# FootPlate_v1.net
KiCad netlist of a schematic drawn in EAGLE
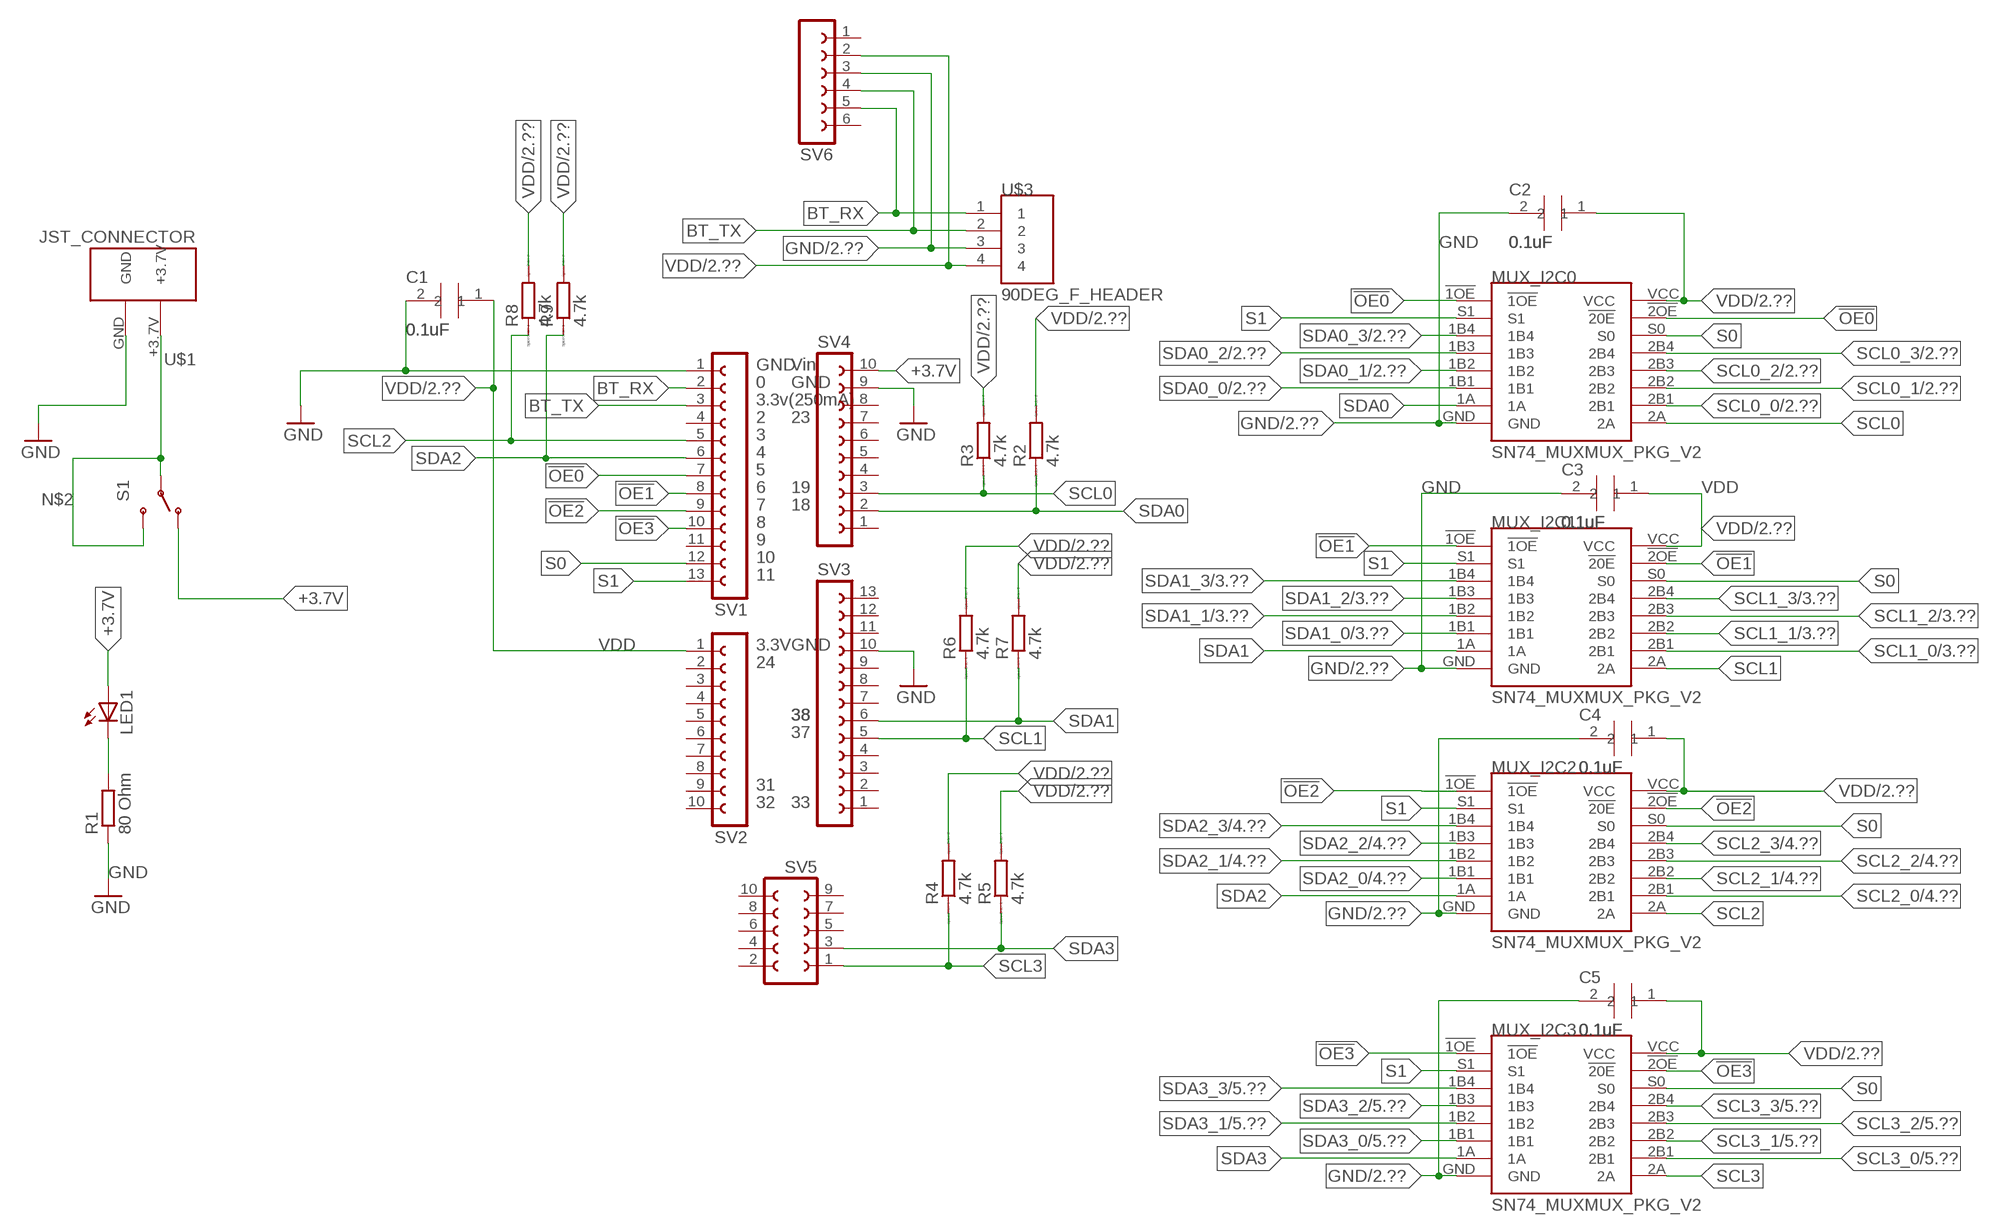
[diagram p0: schematic, sheet 1]
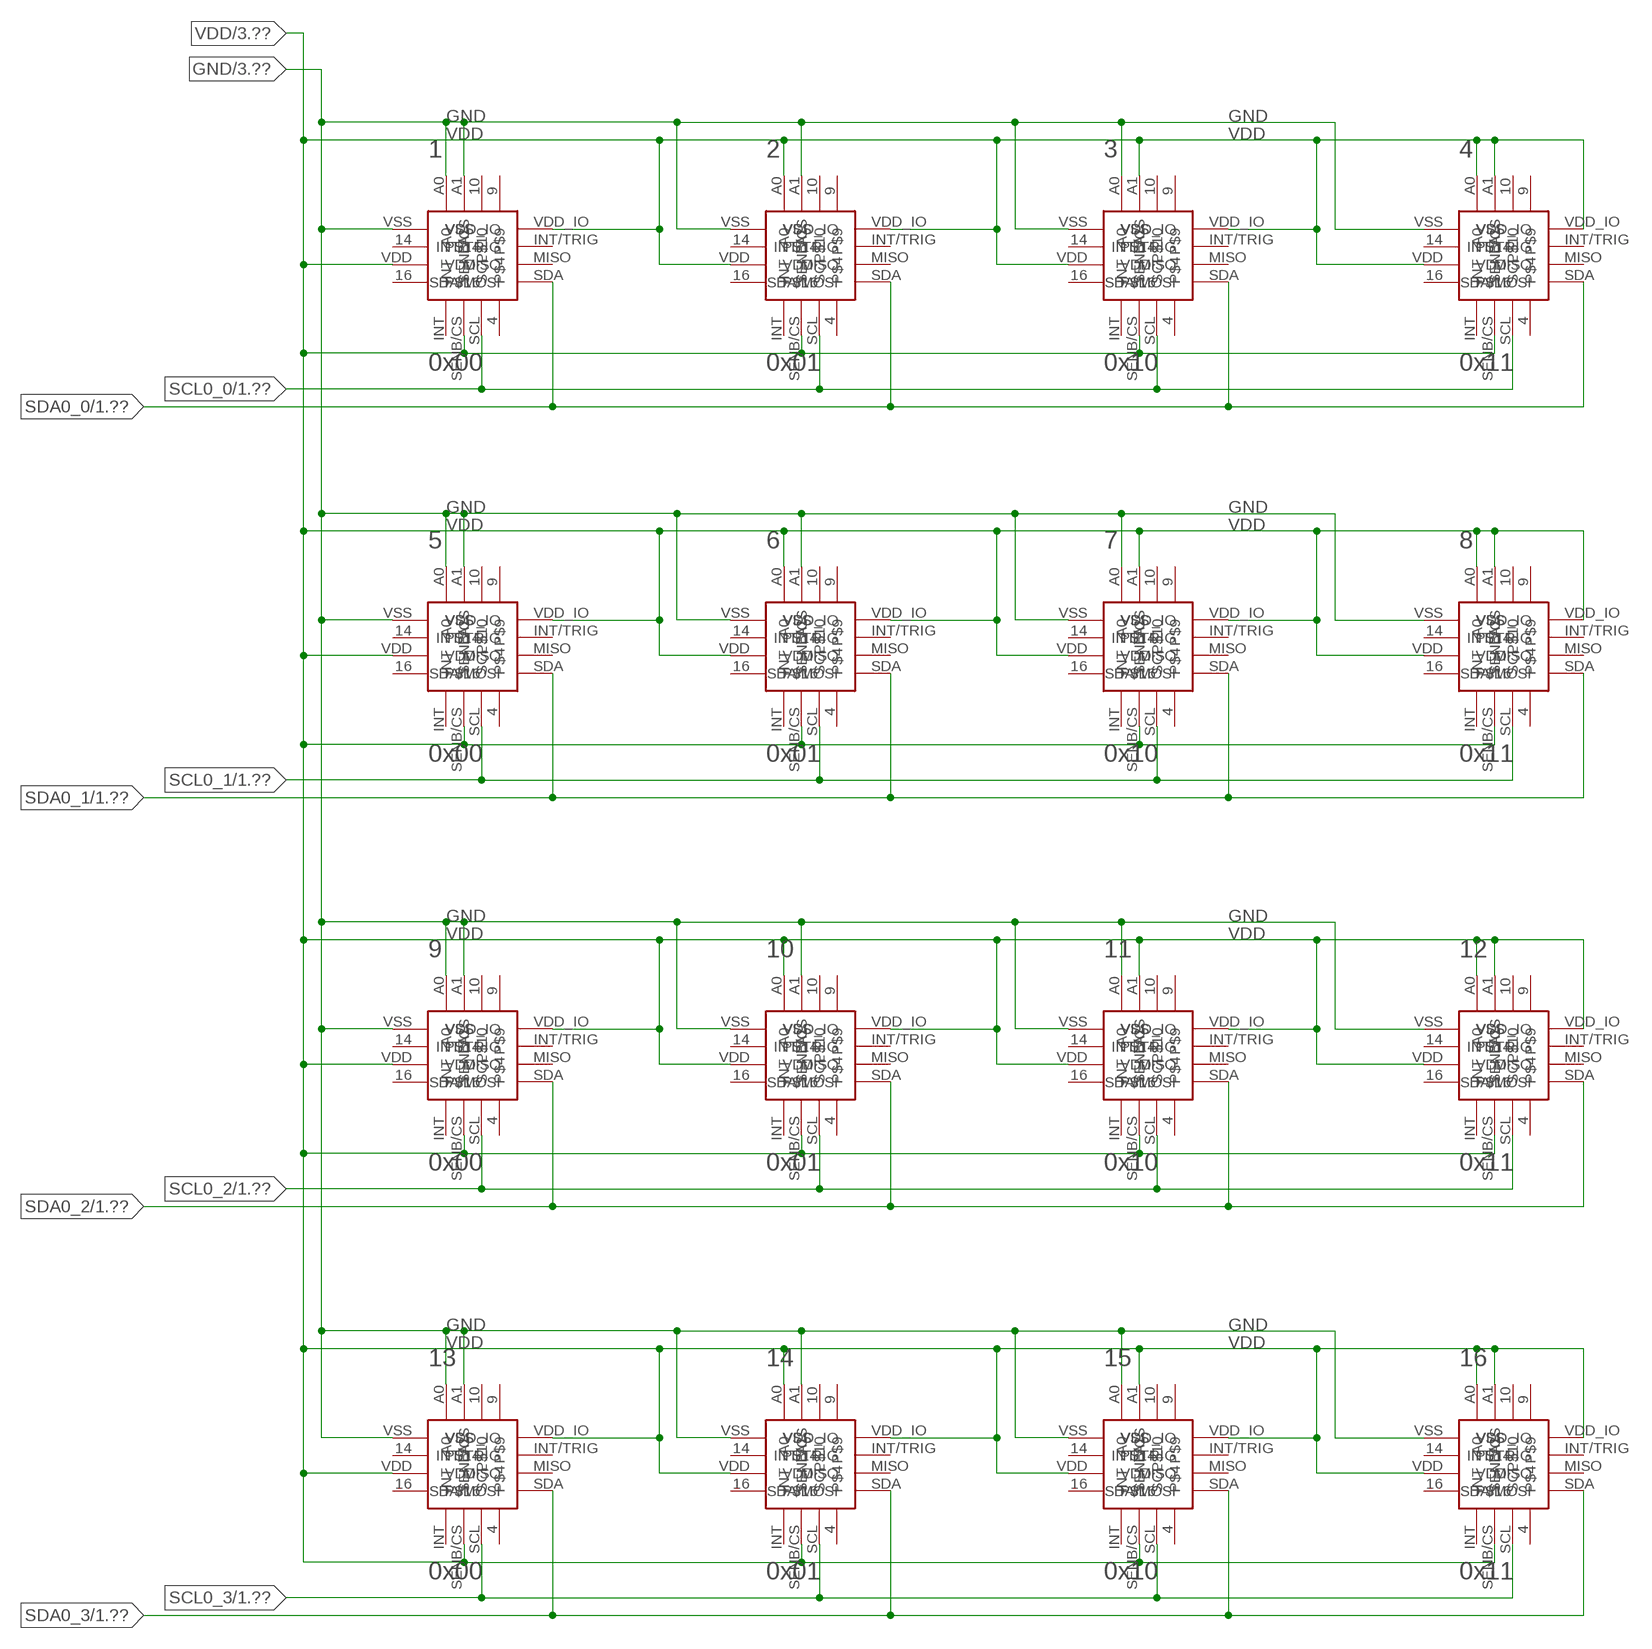
[diagram p1: schematic, sheet 2]
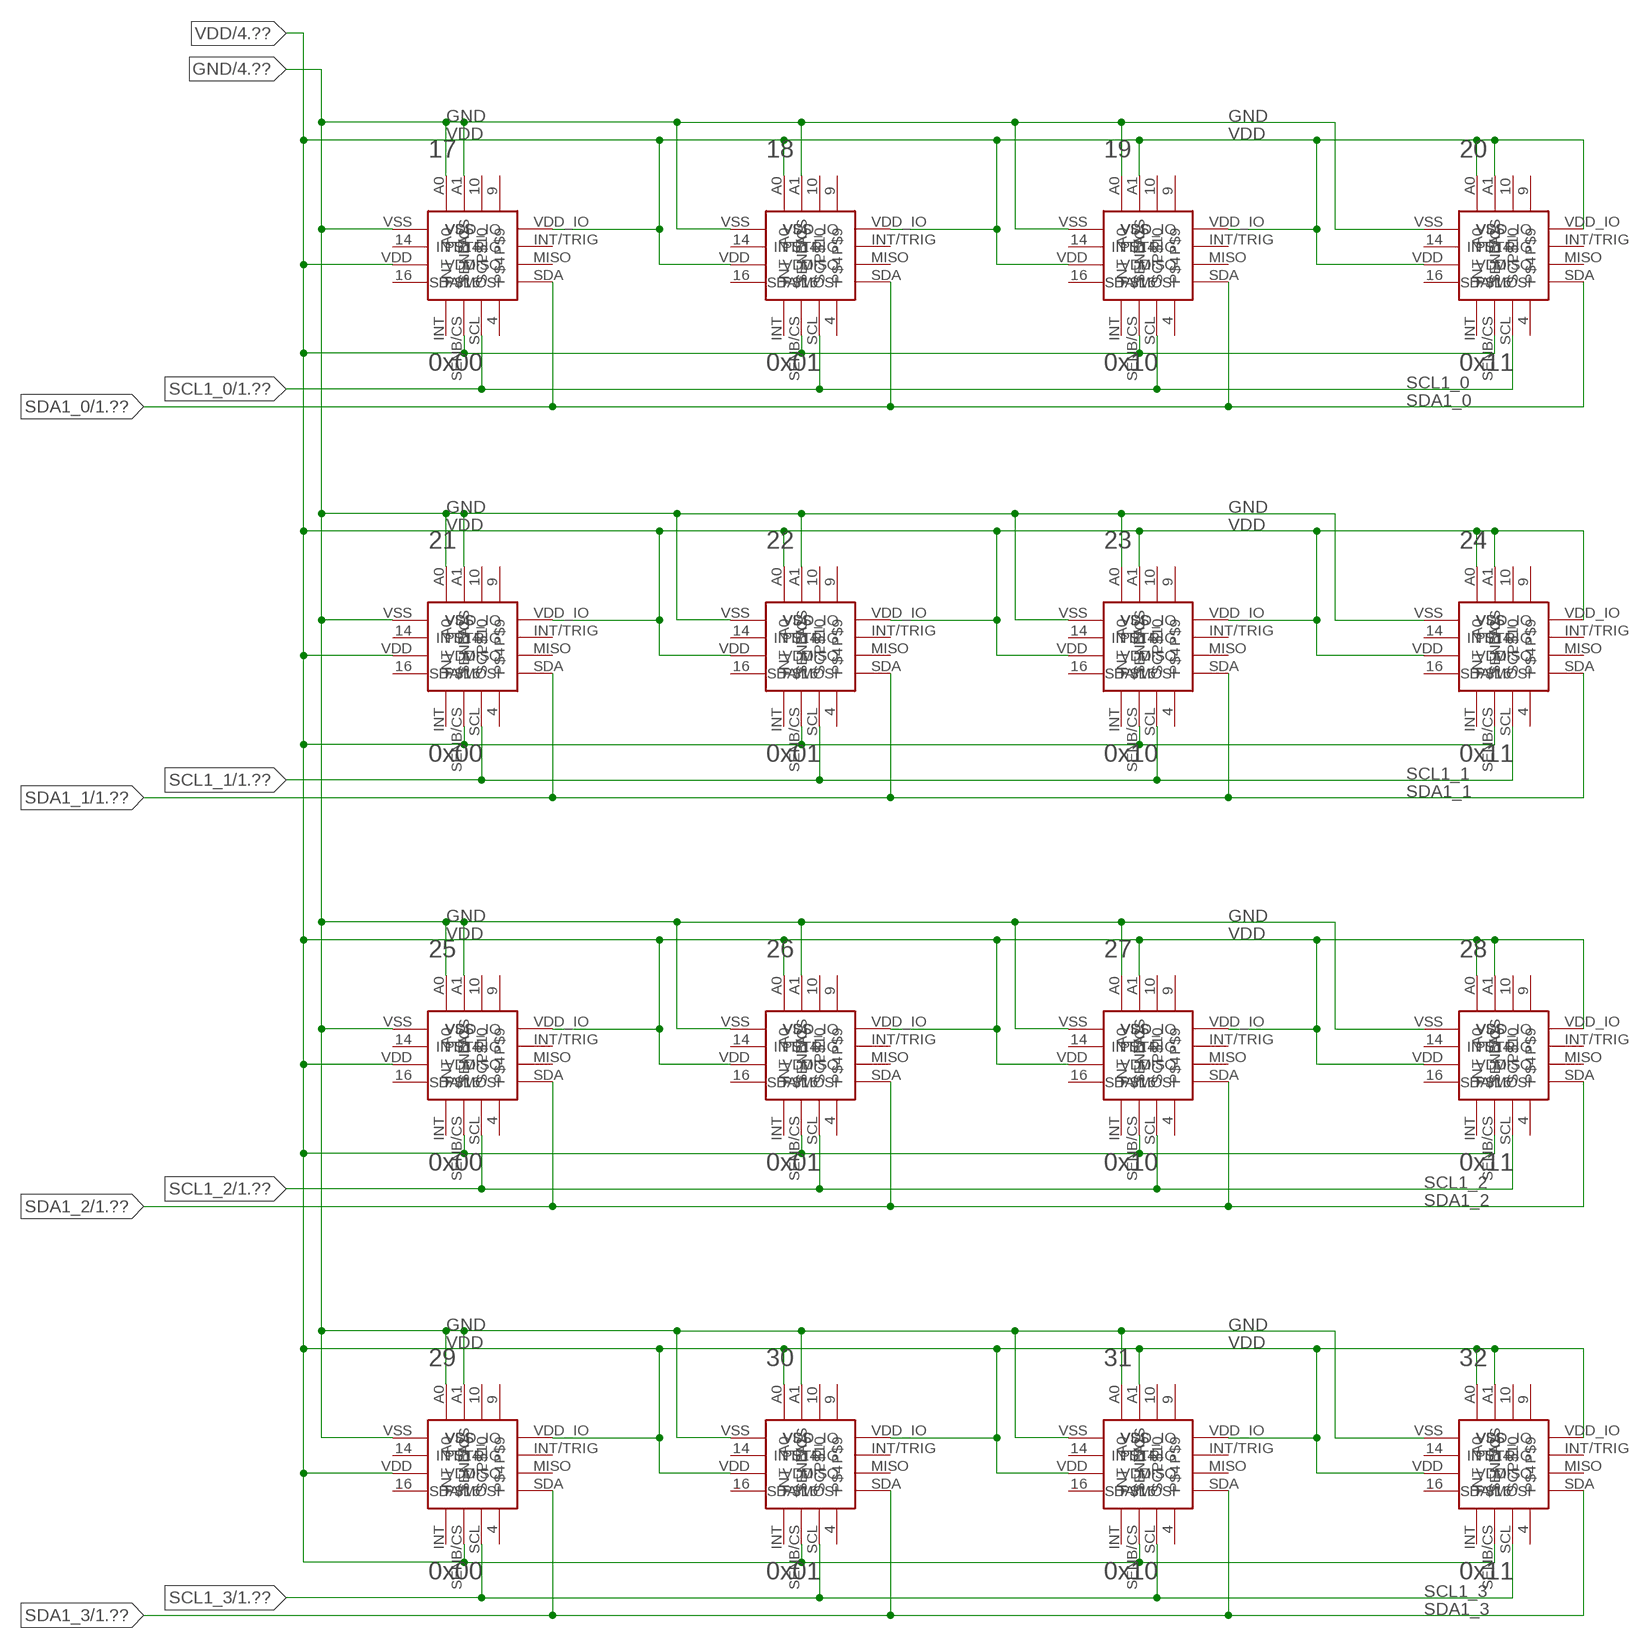
[diagram p2: schematic, sheet 3]
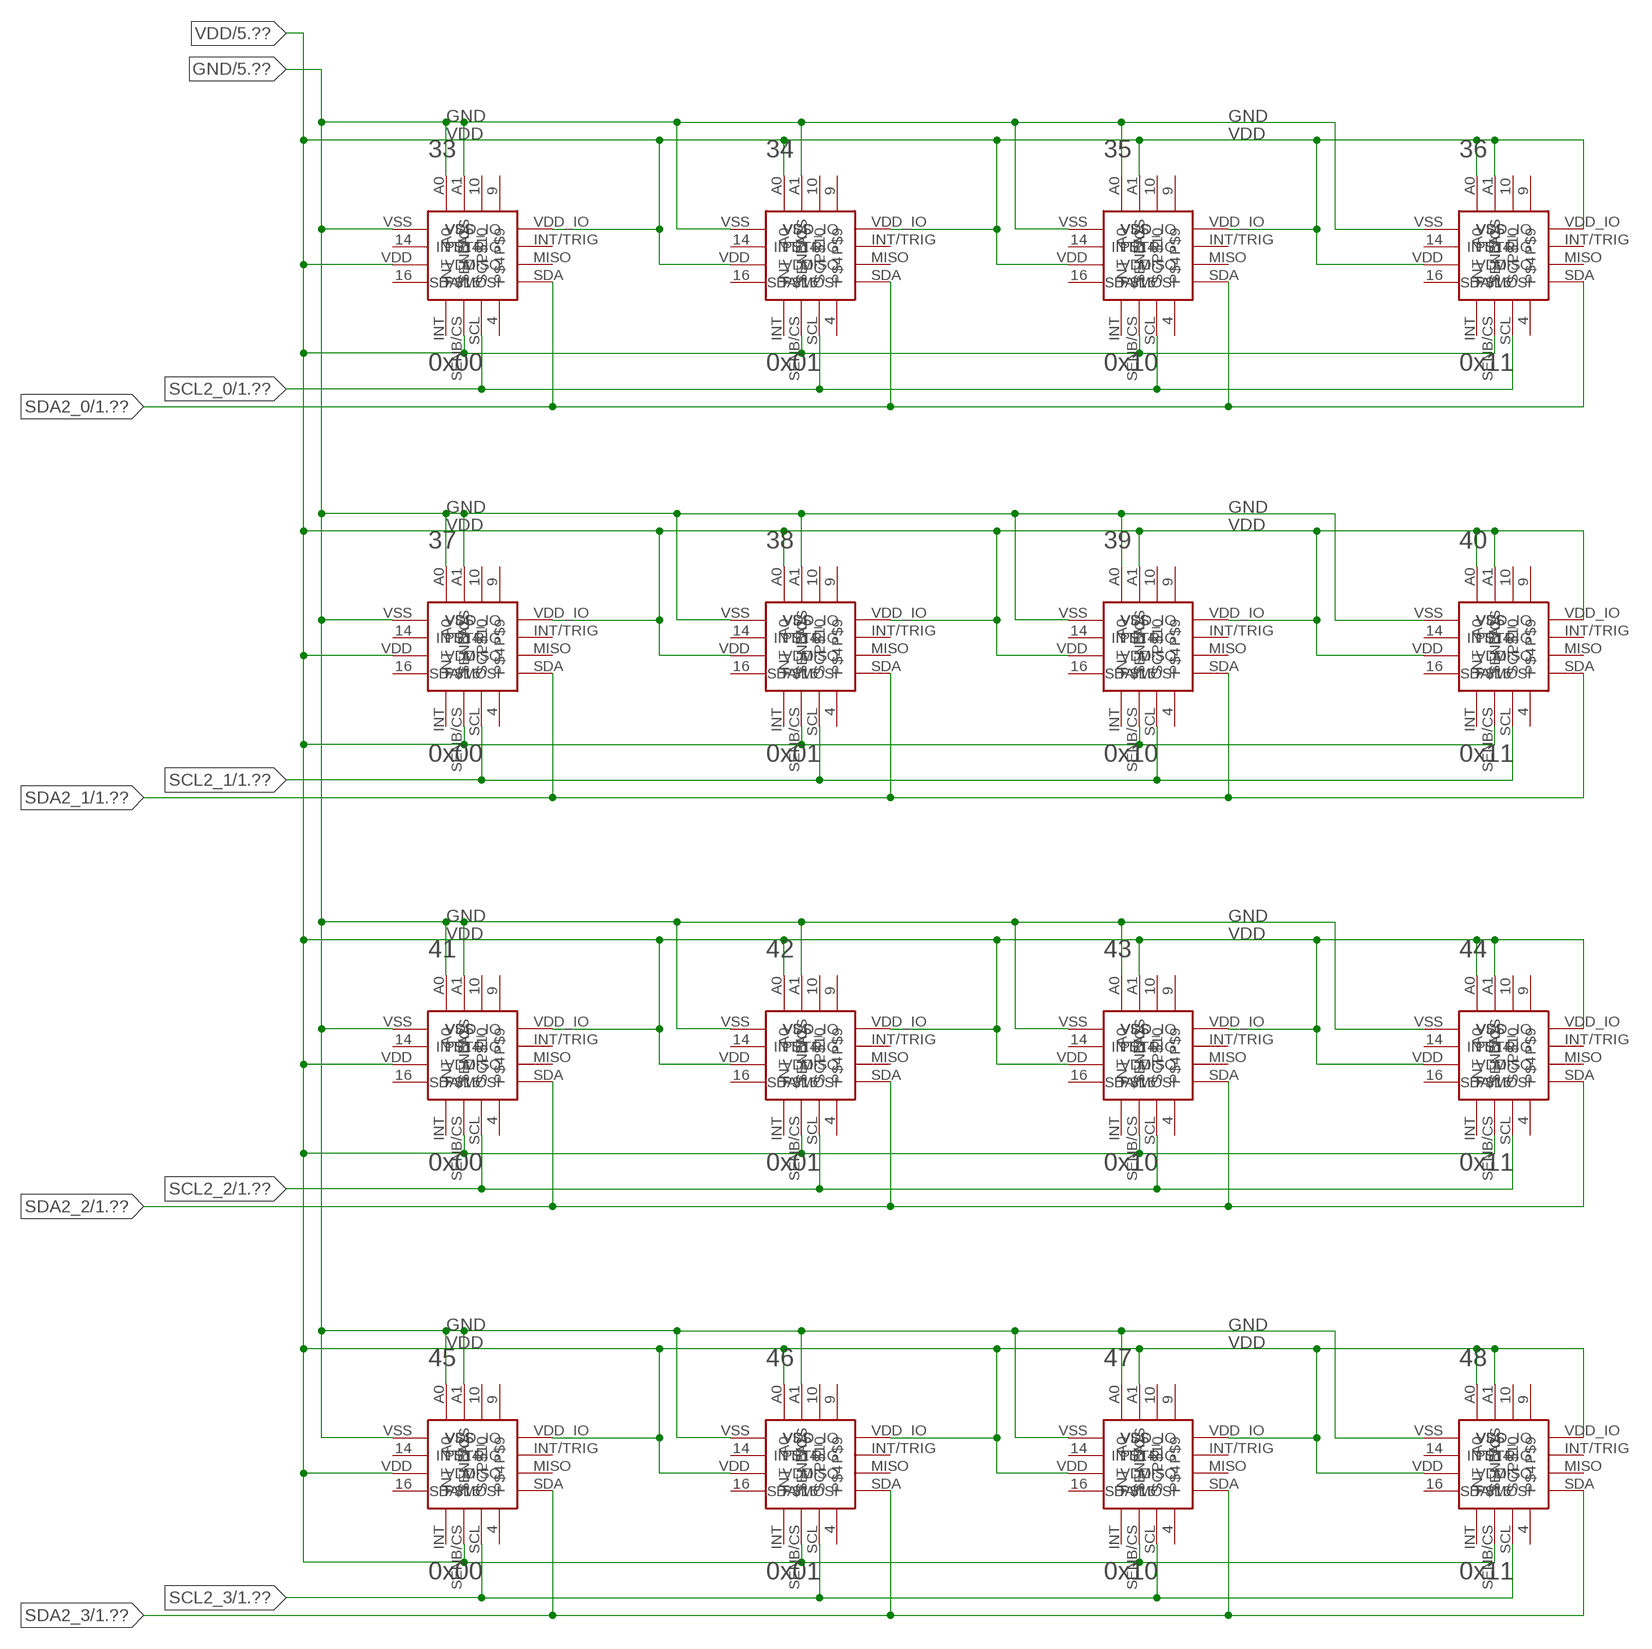
[diagram p3: schematic, sheet 4]
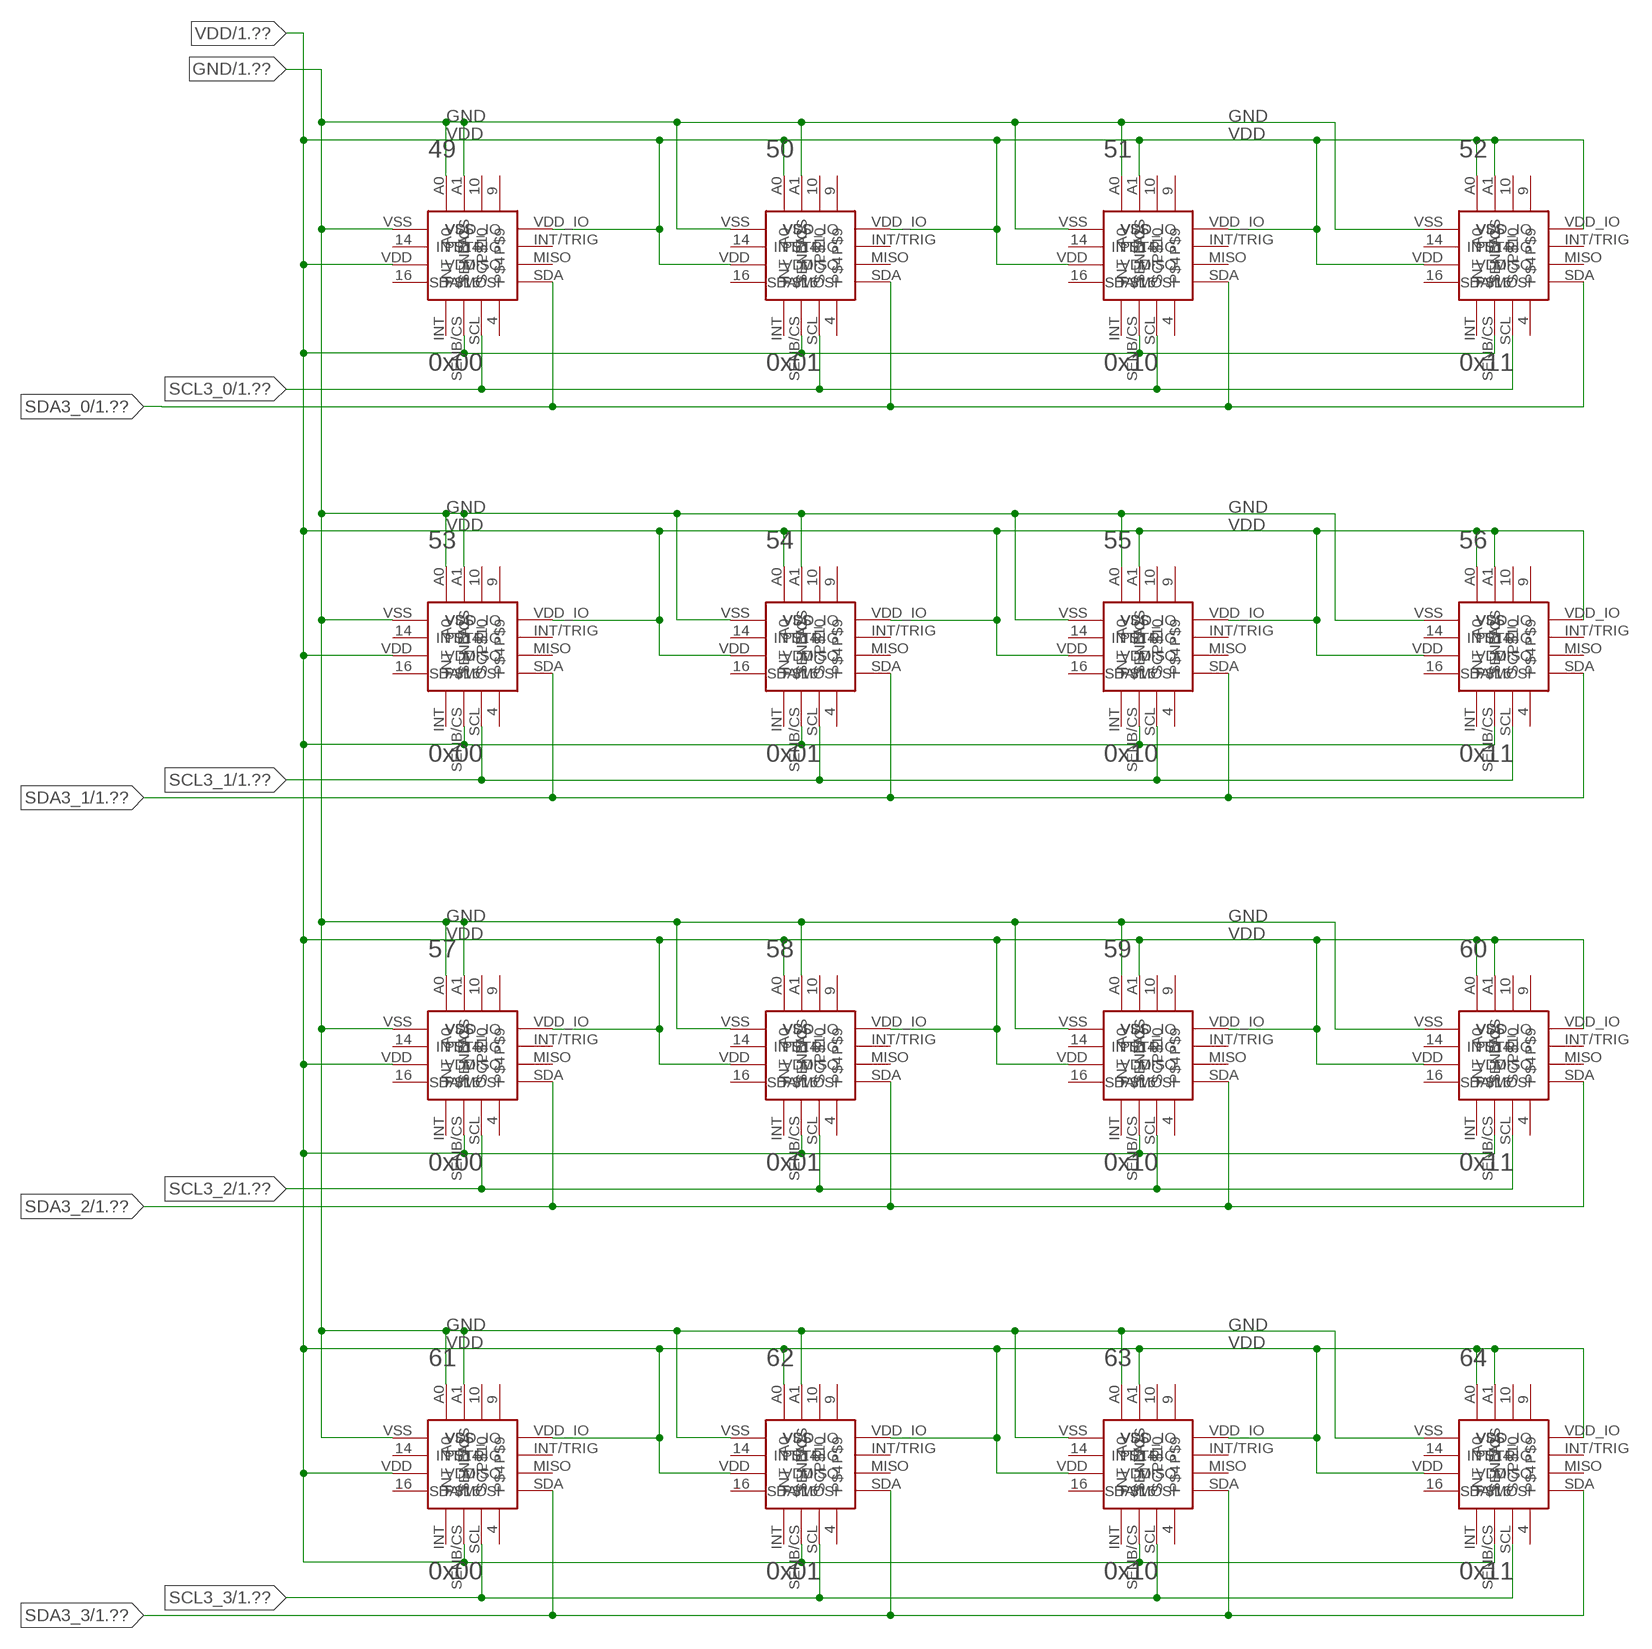
[diagram p4: schematic, sheet 5]

(export (version "E")
  (design (tool "Eeschema 10.0.6"))
  (components
    (comp (ref "C1")
      (value "0.1uF")
      (footprint "eagle-import:CAPC1608X75")
      (libsource (lib "eagle-import") (part "CAP"))
    )
    (comp (ref "C2")
      (value "0.1uF")
      (footprint "eagle-import:CAPC1608X75")
      (libsource (lib "eagle-import") (part "CAP"))
    )
    (comp (ref "C3")
      (value "0.1uF")
      (footprint "eagle-import:CAPC1608X75")
      (libsource (lib "eagle-import") (part "CAP"))
    )
    (comp (ref "C4")
      (value "0.1uF")
      (footprint "eagle-import:CAPC1608X75")
      (libsource (lib "eagle-import") (part "CAP"))
    )
    (comp (ref "C5")
      (value "0.1uF")
      (footprint "eagle-import:CAPC1608X75")
      (libsource (lib "eagle-import") (part "CAP"))
    )
    (comp (ref "LED1")
      (value "LEDSMT1206")
      (footprint "eagle-import:1206")
      (libsource (lib "eagle-import") (part "LEDSMT1206"))
    )
    (comp (ref "MUX_I2C0")
      (value "SN74_MUXMUX_PKG_V2")
      (footprint "eagle-import:SOP65P640X120-16")
      (libsource (lib "eagle-import") (part "SN74_MUXMUX_PKG_V2"))
    )
    (comp (ref "MUX_I2C1")
      (value "SN74_MUXMUX_PKG_V2")
      (footprint "eagle-import:SOP65P640X120-16")
      (libsource (lib "eagle-import") (part "SN74_MUXMUX_PKG_V2"))
    )
    (comp (ref "MUX_I2C2")
      (value "SN74_MUXMUX_PKG_V2")
      (footprint "eagle-import:SOP65P640X120-16")
      (libsource (lib "eagle-import") (part "SN74_MUXMUX_PKG_V2"))
    )
    (comp (ref "MUX_I2C3")
      (value "SN74_MUXMUX_PKG_V2")
      (footprint "eagle-import:SOP65P640X120-16")
      (libsource (lib "eagle-import") (part "SN74_MUXMUX_PKG_V2"))
    )
    (comp (ref "R1")
      (value "80 Ohm")
      (footprint "eagle-import:M1206")
      (libsource (lib "eagle-import") (part "R-EU_M1206"))
    )
    (comp (ref "R2")
      (value "4.7k")
      (footprint "eagle-import:R1206")
      (libsource (lib "eagle-import") (part "RR1206"))
    )
    (comp (ref "R3")
      (value "4.7k")
      (footprint "eagle-import:R1206")
      (libsource (lib "eagle-import") (part "RR1206"))
    )
    (comp (ref "R4")
      (value "4.7k")
      (footprint "eagle-import:R1206")
      (libsource (lib "eagle-import") (part "RR1206"))
    )
    (comp (ref "R5")
      (value "4.7k")
      (footprint "eagle-import:R1206")
      (libsource (lib "eagle-import") (part "RR1206"))
    )
    (comp (ref "R6")
      (value "4.7k")
      (footprint "eagle-import:R1206")
      (libsource (lib "eagle-import") (part "RR1206"))
    )
    (comp (ref "R7")
      (value "4.7k")
      (footprint "eagle-import:R1206")
      (libsource (lib "eagle-import") (part "RR1206"))
    )
    (comp (ref "R8")
      (value "4.7k")
      (footprint "eagle-import:R1206")
      (libsource (lib "eagle-import") (part "RR1206"))
    )
    (comp (ref "R9")
      (value "4.7k")
      (footprint "eagle-import:R1206")
      (libsource (lib "eagle-import") (part "RR1206"))
    )
    (comp (ref "S1")
      (value "SWITCH_SPDT")
      (footprint "eagle-import:SWITCH")
      (libsource (lib "eagle-import") (part "SWITCH_SPDT"))
    )
    (comp (ref "SV1")
      (value "FE13-1")
      (footprint "eagle-import:FE13")
      (libsource (lib "eagle-import") (part "FE13-1"))
    )
    (comp (ref "SV2")
      (value "FE10-1")
      (footprint "eagle-import:FE10")
      (libsource (lib "eagle-import") (part "FE10-1"))
    )
    (comp (ref "SV3")
      (value "FE13-1")
      (footprint "eagle-import:FE13")
      (libsource (lib "eagle-import") (part "FE13-1"))
    )
    (comp (ref "SV4")
      (value "FE10-1")
      (footprint "eagle-import:FE10")
      (libsource (lib "eagle-import") (part "FE10-1"))
    )
    (comp (ref "SV5")
      (value "FE05-2")
      (footprint "eagle-import:FE05-2")
      (libsource (lib "eagle-import") (part "FE05-2"))
    )
    (comp (ref "SV6")
      (value "FE06-1")
      (footprint "eagle-import:FE06")
      (libsource (lib "eagle-import") (part "FE06-1"))
    )
    (comp (ref "U$1")
      (value "JST_CONNECTOR")
      (footprint "eagle-import:JST_PKG")
      (libsource (lib "eagle-import") (part "JST_CONNECTOR"))
    )
    (comp (ref "U$3")
      (value "90DEG_F_HEADER")
      (footprint "eagle-import:90DEG_F_HEADER_PKG")
      (libsource (lib "eagle-import") (part "90DEG_F_HEADER"))
    )
    (comp (ref "17")
      (value "0x00")
      (footprint "eagle-import:MLX90393_PKG")
      (libsource (lib "eagle-import") (part "ML90393_V2"))
    )
    (comp (ref "18")
      (value "0x01")
      (footprint "eagle-import:MLX90393_PKG")
      (libsource (lib "eagle-import") (part "ML90393_V2"))
    )
    (comp (ref "19")
      (value "0x10")
      (footprint "eagle-import:MLX90393_PKG")
      (libsource (lib "eagle-import") (part "ML90393_V2"))
    )
    (comp (ref "20")
      (value "0x11")
      (footprint "eagle-import:MLX90393_PKG")
      (libsource (lib "eagle-import") (part "ML90393_V2"))
    )
    (comp (ref "21")
      (value "0x00")
      (footprint "eagle-import:MLX90393_PKG")
      (libsource (lib "eagle-import") (part "ML90393_V2"))
    )
    (comp (ref "22")
      (value "0x01")
      (footprint "eagle-import:MLX90393_PKG")
      (libsource (lib "eagle-import") (part "ML90393_V2"))
    )
    (comp (ref "23")
      (value "0x10")
      (footprint "eagle-import:MLX90393_PKG")
      (libsource (lib "eagle-import") (part "ML90393_V2"))
    )
    (comp (ref "24")
      (value "0x11")
      (footprint "eagle-import:MLX90393_PKG")
      (libsource (lib "eagle-import") (part "ML90393_V2"))
    )
    (comp (ref "25")
      (value "0x00")
      (footprint "eagle-import:MLX90393_PKG")
      (libsource (lib "eagle-import") (part "ML90393_V2"))
    )
    (comp (ref "26")
      (value "0x01")
      (footprint "eagle-import:MLX90393_PKG")
      (libsource (lib "eagle-import") (part "ML90393_V2"))
    )
    (comp (ref "27")
      (value "0x10")
      (footprint "eagle-import:MLX90393_PKG")
      (libsource (lib "eagle-import") (part "ML90393_V2"))
    )
    (comp (ref "28")
      (value "0x11")
      (footprint "eagle-import:MLX90393_PKG")
      (libsource (lib "eagle-import") (part "ML90393_V2"))
    )
    (comp (ref "29")
      (value "0x00")
      (footprint "eagle-import:MLX90393_PKG")
      (libsource (lib "eagle-import") (part "ML90393_V2"))
    )
    (comp (ref "30")
      (value "0x01")
      (footprint "eagle-import:MLX90393_PKG")
      (libsource (lib "eagle-import") (part "ML90393_V2"))
    )
    (comp (ref "31")
      (value "0x10")
      (footprint "eagle-import:MLX90393_PKG")
      (libsource (lib "eagle-import") (part "ML90393_V2"))
    )
    (comp (ref "32")
      (value "0x11")
      (footprint "eagle-import:MLX90393_PKG")
      (libsource (lib "eagle-import") (part "ML90393_V2"))
    )
    (comp (ref "33")
      (value "0x00")
      (footprint "eagle-import:MLX90393_PKG")
      (libsource (lib "eagle-import") (part "ML90393_V2"))
    )
    (comp (ref "34")
      (value "0x01")
      (footprint "eagle-import:MLX90393_PKG")
      (libsource (lib "eagle-import") (part "ML90393_V2"))
    )
    (comp (ref "35")
      (value "0x10")
      (footprint "eagle-import:MLX90393_PKG")
      (libsource (lib "eagle-import") (part "ML90393_V2"))
    )
    (comp (ref "36")
      (value "0x11")
      (footprint "eagle-import:MLX90393_PKG")
      (libsource (lib "eagle-import") (part "ML90393_V2"))
    )
    (comp (ref "37")
      (value "0x00")
      (footprint "eagle-import:MLX90393_PKG")
      (libsource (lib "eagle-import") (part "ML90393_V2"))
    )
    (comp (ref "38")
      (value "0x01")
      (footprint "eagle-import:MLX90393_PKG")
      (libsource (lib "eagle-import") (part "ML90393_V2"))
    )
    (comp (ref "39")
      (value "0x10")
      (footprint "eagle-import:MLX90393_PKG")
      (libsource (lib "eagle-import") (part "ML90393_V2"))
    )
    (comp (ref "40")
      (value "0x11")
      (footprint "eagle-import:MLX90393_PKG")
      (libsource (lib "eagle-import") (part "ML90393_V2"))
    )
    (comp (ref "41")
      (value "0x00")
      (footprint "eagle-import:MLX90393_PKG")
      (libsource (lib "eagle-import") (part "ML90393_V2"))
    )
    (comp (ref "42")
      (value "0x01")
      (footprint "eagle-import:MLX90393_PKG")
      (libsource (lib "eagle-import") (part "ML90393_V2"))
    )
    (comp (ref "43")
      (value "0x10")
      (footprint "eagle-import:MLX90393_PKG")
      (libsource (lib "eagle-import") (part "ML90393_V2"))
    )
    (comp (ref "44")
      (value "0x11")
      (footprint "eagle-import:MLX90393_PKG")
      (libsource (lib "eagle-import") (part "ML90393_V2"))
    )
    (comp (ref "45")
      (value "0x00")
      (footprint "eagle-import:MLX90393_PKG")
      (libsource (lib "eagle-import") (part "ML90393_V2"))
    )
    (comp (ref "46")
      (value "0x01")
      (footprint "eagle-import:MLX90393_PKG")
      (libsource (lib "eagle-import") (part "ML90393_V2"))
    )
    (comp (ref "47")
      (value "0x10")
      (footprint "eagle-import:MLX90393_PKG")
      (libsource (lib "eagle-import") (part "ML90393_V2"))
    )
    (comp (ref "48")
      (value "0x11")
      (footprint "eagle-import:MLX90393_PKG")
      (libsource (lib "eagle-import") (part "ML90393_V2"))
    )
    (comp (ref "49")
      (value "0x00")
      (footprint "eagle-import:MLX90393_PKG")
      (libsource (lib "eagle-import") (part "ML90393_V2"))
    )
    (comp (ref "50")
      (value "0x01")
      (footprint "eagle-import:MLX90393_PKG")
      (libsource (lib "eagle-import") (part "ML90393_V2"))
    )
    (comp (ref "51")
      (value "0x10")
      (footprint "eagle-import:MLX90393_PKG")
      (libsource (lib "eagle-import") (part "ML90393_V2"))
    )
    (comp (ref "52")
      (value "0x11")
      (footprint "eagle-import:MLX90393_PKG")
      (libsource (lib "eagle-import") (part "ML90393_V2"))
    )
    (comp (ref "53")
      (value "0x00")
      (footprint "eagle-import:MLX90393_PKG")
      (libsource (lib "eagle-import") (part "ML90393_V2"))
    )
    (comp (ref "54")
      (value "0x01")
      (footprint "eagle-import:MLX90393_PKG")
      (libsource (lib "eagle-import") (part "ML90393_V2"))
    )
    (comp (ref "55")
      (value "0x10")
      (footprint "eagle-import:MLX90393_PKG")
      (libsource (lib "eagle-import") (part "ML90393_V2"))
    )
    (comp (ref "56")
      (value "0x11")
      (footprint "eagle-import:MLX90393_PKG")
      (libsource (lib "eagle-import") (part "ML90393_V2"))
    )
    (comp (ref "57")
      (value "0x00")
      (footprint "eagle-import:MLX90393_PKG")
      (libsource (lib "eagle-import") (part "ML90393_V2"))
    )
    (comp (ref "58")
      (value "0x01")
      (footprint "eagle-import:MLX90393_PKG")
      (libsource (lib "eagle-import") (part "ML90393_V2"))
    )
    (comp (ref "59")
      (value "0x10")
      (footprint "eagle-import:MLX90393_PKG")
      (libsource (lib "eagle-import") (part "ML90393_V2"))
    )
    (comp (ref "60")
      (value "0x11")
      (footprint "eagle-import:MLX90393_PKG")
      (libsource (lib "eagle-import") (part "ML90393_V2"))
    )
    (comp (ref "61")
      (value "0x00")
      (footprint "eagle-import:MLX90393_PKG")
      (libsource (lib "eagle-import") (part "ML90393_V2"))
    )
    (comp (ref "62")
      (value "0x01")
      (footprint "eagle-import:MLX90393_PKG")
      (libsource (lib "eagle-import") (part "ML90393_V2"))
    )
    (comp (ref "63")
      (value "0x10")
      (footprint "eagle-import:MLX90393_PKG")
      (libsource (lib "eagle-import") (part "ML90393_V2"))
    )
    (comp (ref "64")
      (value "0x11")
      (footprint "eagle-import:MLX90393_PKG")
      (libsource (lib "eagle-import") (part "ML90393_V2"))
    )
    (comp (ref "1")
      (value "0x00")
      (footprint "eagle-import:MLX90393_PKG")
      (libsource (lib "eagle-import") (part "ML90393_V2"))
    )
    (comp (ref "2")
      (value "0x01")
      (footprint "eagle-import:MLX90393_PKG")
      (libsource (lib "eagle-import") (part "ML90393_V2"))
    )
    (comp (ref "3")
      (value "0x10")
      (footprint "eagle-import:MLX90393_PKG")
      (libsource (lib "eagle-import") (part "ML90393_V2"))
    )
    (comp (ref "4")
      (value "0x11")
      (footprint "eagle-import:MLX90393_PKG")
      (libsource (lib "eagle-import") (part "ML90393_V2"))
    )
    (comp (ref "5")
      (value "0x00")
      (footprint "eagle-import:MLX90393_PKG")
      (libsource (lib "eagle-import") (part "ML90393_V2"))
    )
    (comp (ref "6")
      (value "0x01")
      (footprint "eagle-import:MLX90393_PKG")
      (libsource (lib "eagle-import") (part "ML90393_V2"))
    )
    (comp (ref "7")
      (value "0x10")
      (footprint "eagle-import:MLX90393_PKG")
      (libsource (lib "eagle-import") (part "ML90393_V2"))
    )
    (comp (ref "8")
      (value "0x11")
      (footprint "eagle-import:MLX90393_PKG")
      (libsource (lib "eagle-import") (part "ML90393_V2"))
    )
    (comp (ref "9")
      (value "0x00")
      (footprint "eagle-import:MLX90393_PKG")
      (libsource (lib "eagle-import") (part "ML90393_V2"))
    )
    (comp (ref "10")
      (value "0x01")
      (footprint "eagle-import:MLX90393_PKG")
      (libsource (lib "eagle-import") (part "ML90393_V2"))
    )
    (comp (ref "11")
      (value "0x10")
      (footprint "eagle-import:MLX90393_PKG")
      (libsource (lib "eagle-import") (part "ML90393_V2"))
    )
    (comp (ref "12")
      (value "0x11")
      (footprint "eagle-import:MLX90393_PKG")
      (libsource (lib "eagle-import") (part "ML90393_V2"))
    )
    (comp (ref "13")
      (value "0x00")
      (footprint "eagle-import:MLX90393_PKG")
      (libsource (lib "eagle-import") (part "ML90393_V2"))
    )
    (comp (ref "14")
      (value "0x01")
      (footprint "eagle-import:MLX90393_PKG")
      (libsource (lib "eagle-import") (part "ML90393_V2"))
    )
    (comp (ref "15")
      (value "0x10")
      (footprint "eagle-import:MLX90393_PKG")
      (libsource (lib "eagle-import") (part "ML90393_V2"))
    )
    (comp (ref "16")
      (value "0x11")
      (footprint "eagle-import:MLX90393_PKG")
      (libsource (lib "eagle-import") (part "ML90393_V2"))
    )
  )
  (nets
    (net (code "1") (name "+3.7V") (class "Default")
      (node (ref "LED1") (pin "A") (pinfunction "A_A") (pintype "passive"))
      (node (ref "S1") (pin "1") (pinfunction "O_1") (pintype "passive"))
      (node (ref "SV4") (pin "10") (pinfunction "10_10") (pintype "passive"))
    )
    (net (code "2") (name "BT_RX") (class "Default")
      (node (ref "SV1") (pin "2") (pinfunction "2_2") (pintype "passive"))
      (node (ref "SV6") (pin "5") (pinfunction "5_5") (pintype "passive"))
      (node (ref "U$3") (pin "1") (pinfunction "1_1") (pintype "bidirectional"))
    )
    (net (code "3") (name "BT_TX") (class "Default")
      (node (ref "SV1") (pin "3") (pinfunction "3_3") (pintype "passive"))
      (node (ref "SV6") (pin "4") (pinfunction "4_4") (pintype "passive"))
      (node (ref "U$3") (pin "2") (pinfunction "2_2") (pintype "bidirectional"))
    )
    (net (code "4") (name "GND") (class "Default")
      (node (ref "1") (pin "A0") (pinfunction "A0_A0") (pintype "bidirectional"))
      (node (ref "1") (pin "A1") (pinfunction "A1_A1") (pintype "bidirectional"))
      (node (ref "1") (pin "VSS") (pinfunction "VSS_VSS") (pintype "bidirectional"))
      (node (ref "10") (pin "A1") (pinfunction "A1_A1") (pintype "bidirectional"))
      (node (ref "10") (pin "VSS") (pinfunction "VSS_VSS") (pintype "bidirectional"))
      (node (ref "11") (pin "A0") (pinfunction "A0_A0") (pintype "bidirectional"))
      (node (ref "11") (pin "VSS") (pinfunction "VSS_VSS") (pintype "bidirectional"))
      (node (ref "12") (pin "VSS") (pinfunction "VSS_VSS") (pintype "bidirectional"))
      (node (ref "13") (pin "A0") (pinfunction "A0_A0") (pintype "bidirectional"))
      (node (ref "13") (pin "A1") (pinfunction "A1_A1") (pintype "bidirectional"))
      (node (ref "13") (pin "VSS") (pinfunction "VSS_VSS") (pintype "bidirectional"))
      (node (ref "14") (pin "A1") (pinfunction "A1_A1") (pintype "bidirectional"))
      (node (ref "14") (pin "VSS") (pinfunction "VSS_VSS") (pintype "bidirectional"))
      (node (ref "15") (pin "A0") (pinfunction "A0_A0") (pintype "bidirectional"))
      (node (ref "15") (pin "VSS") (pinfunction "VSS_VSS") (pintype "bidirectional"))
      (node (ref "16") (pin "VSS") (pinfunction "VSS_VSS") (pintype "bidirectional"))
      (node (ref "17") (pin "A0") (pinfunction "A0_A0") (pintype "bidirectional"))
      (node (ref "17") (pin "A1") (pinfunction "A1_A1") (pintype "bidirectional"))
      (node (ref "17") (pin "VSS") (pinfunction "VSS_VSS") (pintype "bidirectional"))
      (node (ref "18") (pin "A1") (pinfunction "A1_A1") (pintype "bidirectional"))
      (node (ref "18") (pin "VSS") (pinfunction "VSS_VSS") (pintype "bidirectional"))
      (node (ref "19") (pin "A0") (pinfunction "A0_A0") (pintype "bidirectional"))
      (node (ref "19") (pin "VSS") (pinfunction "VSS_VSS") (pintype "bidirectional"))
      (node (ref "2") (pin "A1") (pinfunction "A1_A1") (pintype "bidirectional"))
      (node (ref "2") (pin "VSS") (pinfunction "VSS_VSS") (pintype "bidirectional"))
      (node (ref "20") (pin "VSS") (pinfunction "VSS_VSS") (pintype "bidirectional"))
      (node (ref "21") (pin "A0") (pinfunction "A0_A0") (pintype "bidirectional"))
      (node (ref "21") (pin "A1") (pinfunction "A1_A1") (pintype "bidirectional"))
      (node (ref "21") (pin "VSS") (pinfunction "VSS_VSS") (pintype "bidirectional"))
      (node (ref "22") (pin "A1") (pinfunction "A1_A1") (pintype "bidirectional"))
      (node (ref "22") (pin "VSS") (pinfunction "VSS_VSS") (pintype "bidirectional"))
      (node (ref "23") (pin "A0") (pinfunction "A0_A0") (pintype "bidirectional"))
      (node (ref "23") (pin "VSS") (pinfunction "VSS_VSS") (pintype "bidirectional"))
      (node (ref "24") (pin "VSS") (pinfunction "VSS_VSS") (pintype "bidirectional"))
      (node (ref "25") (pin "A0") (pinfunction "A0_A0") (pintype "bidirectional"))
      (node (ref "25") (pin "A1") (pinfunction "A1_A1") (pintype "bidirectional"))
      (node (ref "25") (pin "VSS") (pinfunction "VSS_VSS") (pintype "bidirectional"))
      (node (ref "26") (pin "A1") (pinfunction "A1_A1") (pintype "bidirectional"))
      (node (ref "26") (pin "VSS") (pinfunction "VSS_VSS") (pintype "bidirectional"))
      (node (ref "27") (pin "A0") (pinfunction "A0_A0") (pintype "bidirectional"))
      (node (ref "27") (pin "VSS") (pinfunction "VSS_VSS") (pintype "bidirectional"))
      (node (ref "28") (pin "VSS") (pinfunction "VSS_VSS") (pintype "bidirectional"))
      (node (ref "29") (pin "A0") (pinfunction "A0_A0") (pintype "bidirectional"))
      (node (ref "29") (pin "A1") (pinfunction "A1_A1") (pintype "bidirectional"))
      (node (ref "29") (pin "VSS") (pinfunction "VSS_VSS") (pintype "bidirectional"))
      (node (ref "3") (pin "A0") (pinfunction "A0_A0") (pintype "bidirectional"))
      (node (ref "3") (pin "VSS") (pinfunction "VSS_VSS") (pintype "bidirectional"))
      (node (ref "30") (pin "A1") (pinfunction "A1_A1") (pintype "bidirectional"))
      (node (ref "30") (pin "VSS") (pinfunction "VSS_VSS") (pintype "bidirectional"))
      (node (ref "31") (pin "A0") (pinfunction "A0_A0") (pintype "bidirectional"))
      (node (ref "31") (pin "VSS") (pinfunction "VSS_VSS") (pintype "bidirectional"))
      (node (ref "32") (pin "VSS") (pinfunction "VSS_VSS") (pintype "bidirectional"))
      (node (ref "33") (pin "A0") (pinfunction "A0_A0") (pintype "bidirectional"))
      (node (ref "33") (pin "A1") (pinfunction "A1_A1") (pintype "bidirectional"))
      (node (ref "33") (pin "VSS") (pinfunction "VSS_VSS") (pintype "bidirectional"))
      (node (ref "34") (pin "A1") (pinfunction "A1_A1") (pintype "bidirectional"))
      (node (ref "34") (pin "VSS") (pinfunction "VSS_VSS") (pintype "bidirectional"))
      (node (ref "35") (pin "A0") (pinfunction "A0_A0") (pintype "bidirectional"))
      (node (ref "35") (pin "VSS") (pinfunction "VSS_VSS") (pintype "bidirectional"))
      (node (ref "36") (pin "VSS") (pinfunction "VSS_VSS") (pintype "bidirectional"))
      (node (ref "37") (pin "A0") (pinfunction "A0_A0") (pintype "bidirectional"))
      (node (ref "37") (pin "A1") (pinfunction "A1_A1") (pintype "bidirectional"))
      (node (ref "37") (pin "VSS") (pinfunction "VSS_VSS") (pintype "bidirectional"))
      (node (ref "38") (pin "A1") (pinfunction "A1_A1") (pintype "bidirectional"))
      (node (ref "38") (pin "VSS") (pinfunction "VSS_VSS") (pintype "bidirectional"))
      (node (ref "39") (pin "A0") (pinfunction "A0_A0") (pintype "bidirectional"))
      (node (ref "39") (pin "VSS") (pinfunction "VSS_VSS") (pintype "bidirectional"))
      (node (ref "4") (pin "VSS") (pinfunction "VSS_VSS") (pintype "bidirectional"))
      (node (ref "40") (pin "VSS") (pinfunction "VSS_VSS") (pintype "bidirectional"))
      (node (ref "41") (pin "A0") (pinfunction "A0_A0") (pintype "bidirectional"))
      (node (ref "41") (pin "A1") (pinfunction "A1_A1") (pintype "bidirectional"))
      (node (ref "41") (pin "VSS") (pinfunction "VSS_VSS") (pintype "bidirectional"))
      (node (ref "42") (pin "A1") (pinfunction "A1_A1") (pintype "bidirectional"))
      (node (ref "42") (pin "VSS") (pinfunction "VSS_VSS") (pintype "bidirectional"))
      (node (ref "43") (pin "A0") (pinfunction "A0_A0") (pintype "bidirectional"))
      (node (ref "43") (pin "VSS") (pinfunction "VSS_VSS") (pintype "bidirectional"))
      (node (ref "44") (pin "VSS") (pinfunction "VSS_VSS") (pintype "bidirectional"))
      (node (ref "45") (pin "A0") (pinfunction "A0_A0") (pintype "bidirectional"))
      (node (ref "45") (pin "A1") (pinfunction "A1_A1") (pintype "bidirectional"))
      (node (ref "45") (pin "VSS") (pinfunction "VSS_VSS") (pintype "bidirectional"))
      (node (ref "46") (pin "A1") (pinfunction "A1_A1") (pintype "bidirectional"))
      (node (ref "46") (pin "VSS") (pinfunction "VSS_VSS") (pintype "bidirectional"))
      (node (ref "47") (pin "A0") (pinfunction "A0_A0") (pintype "bidirectional"))
      (node (ref "47") (pin "VSS") (pinfunction "VSS_VSS") (pintype "bidirectional"))
      (node (ref "48") (pin "VSS") (pinfunction "VSS_VSS") (pintype "bidirectional"))
      (node (ref "49") (pin "A0") (pinfunction "A0_A0") (pintype "bidirectional"))
      (node (ref "49") (pin "A1") (pinfunction "A1_A1") (pintype "bidirectional"))
      (node (ref "49") (pin "VSS") (pinfunction "VSS_VSS") (pintype "bidirectional"))
      (node (ref "5") (pin "A0") (pinfunction "A0_A0") (pintype "bidirectional"))
      (node (ref "5") (pin "A1") (pinfunction "A1_A1") (pintype "bidirectional"))
      (node (ref "5") (pin "VSS") (pinfunction "VSS_VSS") (pintype "bidirectional"))
      (node (ref "50") (pin "A1") (pinfunction "A1_A1") (pintype "bidirectional"))
      (node (ref "50") (pin "VSS") (pinfunction "VSS_VSS") (pintype "bidirectional"))
      (node (ref "51") (pin "A0") (pinfunction "A0_A0") (pintype "bidirectional"))
      (node (ref "51") (pin "VSS") (pinfunction "VSS_VSS") (pintype "bidirectional"))
      (node (ref "52") (pin "VSS") (pinfunction "VSS_VSS") (pintype "bidirectional"))
      (node (ref "53") (pin "A0") (pinfunction "A0_A0") (pintype "bidirectional"))
      (node (ref "53") (pin "A1") (pinfunction "A1_A1") (pintype "bidirectional"))
      (node (ref "53") (pin "VSS") (pinfunction "VSS_VSS") (pintype "bidirectional"))
      (node (ref "54") (pin "A1") (pinfunction "A1_A1") (pintype "bidirectional"))
      (node (ref "54") (pin "VSS") (pinfunction "VSS_VSS") (pintype "bidirectional"))
      (node (ref "55") (pin "A0") (pinfunction "A0_A0") (pintype "bidirectional"))
      (node (ref "55") (pin "VSS") (pinfunction "VSS_VSS") (pintype "bidirectional"))
      (node (ref "56") (pin "VSS") (pinfunction "VSS_VSS") (pintype "bidirectional"))
      (node (ref "57") (pin "A0") (pinfunction "A0_A0") (pintype "bidirectional"))
      (node (ref "57") (pin "A1") (pinfunction "A1_A1") (pintype "bidirectional"))
      (node (ref "57") (pin "VSS") (pinfunction "VSS_VSS") (pintype "bidirectional"))
      (node (ref "58") (pin "A1") (pinfunction "A1_A1") (pintype "bidirectional"))
      (node (ref "58") (pin "VSS") (pinfunction "VSS_VSS") (pintype "bidirectional"))
      (node (ref "59") (pin "A0") (pinfunction "A0_A0") (pintype "bidirectional"))
      (node (ref "59") (pin "VSS") (pinfunction "VSS_VSS") (pintype "bidirectional"))
      (node (ref "6") (pin "A1") (pinfunction "A1_A1") (pintype "bidirectional"))
      (node (ref "6") (pin "VSS") (pinfunction "VSS_VSS") (pintype "bidirectional"))
      (node (ref "60") (pin "VSS") (pinfunction "VSS_VSS") (pintype "bidirectional"))
      (node (ref "61") (pin "A0") (pinfunction "A0_A0") (pintype "bidirectional"))
      (node (ref "61") (pin "A1") (pinfunction "A1_A1") (pintype "bidirectional"))
      (node (ref "61") (pin "VSS") (pinfunction "VSS_VSS") (pintype "bidirectional"))
      (node (ref "62") (pin "A1") (pinfunction "A1_A1") (pintype "bidirectional"))
      (node (ref "62") (pin "VSS") (pinfunction "VSS_VSS") (pintype "bidirectional"))
      (node (ref "63") (pin "A0") (pinfunction "A0_A0") (pintype "bidirectional"))
      (node (ref "63") (pin "VSS") (pinfunction "VSS_VSS") (pintype "bidirectional"))
      (node (ref "64") (pin "VSS") (pinfunction "VSS_VSS") (pintype "bidirectional"))
      (node (ref "7") (pin "A0") (pinfunction "A0_A0") (pintype "bidirectional"))
      (node (ref "7") (pin "VSS") (pinfunction "VSS_VSS") (pintype "bidirectional"))
      (node (ref "8") (pin "VSS") (pinfunction "VSS_VSS") (pintype "bidirectional"))
      (node (ref "9") (pin "A0") (pinfunction "A0_A0") (pintype "bidirectional"))
      (node (ref "9") (pin "A1") (pinfunction "A1_A1") (pintype "bidirectional"))
      (node (ref "9") (pin "VSS") (pinfunction "VSS_VSS") (pintype "bidirectional"))
      (node (ref "C1") (pin "2") (pinfunction "1_2") (pintype "bidirectional"))
      (node (ref "C2") (pin "2") (pinfunction "1_2") (pintype "bidirectional"))
      (node (ref "C3") (pin "2") (pinfunction "1_2") (pintype "bidirectional"))
      (node (ref "C4") (pin "2") (pinfunction "1_2") (pintype "bidirectional"))
      (node (ref "C5") (pin "2") (pinfunction "1_2") (pintype "bidirectional"))
      (node (ref "MUX_I2C0") (pin "GND") (pinfunction "GND_GND") (pintype "bidirectional"))
      (node (ref "MUX_I2C1") (pin "GND") (pinfunction "GND_GND") (pintype "bidirectional"))
      (node (ref "MUX_I2C2") (pin "GND") (pinfunction "GND_GND") (pintype "bidirectional"))
      (node (ref "MUX_I2C3") (pin "GND") (pinfunction "GND_GND") (pintype "bidirectional"))
      (node (ref "R1") (pin "1") (pinfunction "1_1") (pintype "passive"))
      (node (ref "SV1") (pin "1") (pinfunction "1_1") (pintype "passive"))
      (node (ref "SV3") (pin "10") (pinfunction "10_10") (pintype "passive"))
      (node (ref "SV4") (pin "9") (pinfunction "9_9") (pintype "passive"))
      (node (ref "SV6") (pin "3") (pinfunction "3_3") (pintype "passive"))
      (node (ref "U$1") (pin "GND") (pinfunction "GND_GND") (pintype "bidirectional"))
      (node (ref "U$3") (pin "3") (pinfunction "3_3") (pintype "bidirectional"))
    )
    (net (code "5") (name "N$2") (class "Default")
      (node (ref "S1") (pin "2") (pinfunction "P_2") (pintype "passive"))
      (node (ref "S1") (pin "3") (pinfunction "S_3") (pintype "passive"))
      (node (ref "U$1") (pin "+3.7V") (pinfunction "+3.7V_+3.7V") (pintype "bidirectional"))
    )
    (net (code "6") (name "Net-(LED1-PadC)") (class "Default")
      (node (ref "LED1") (pin "C") (pinfunction "C_C") (pintype "passive"))
      (node (ref "R1") (pin "2") (pinfunction "2_2") (pintype "passive"))
    )
    (net (code "7") (name "S0") (class "Default")
      (node (ref "MUX_I2C0") (pin "S0") (pinfunction "S0_S0") (pintype "bidirectional"))
      (node (ref "MUX_I2C1") (pin "S0") (pinfunction "S0_S0") (pintype "bidirectional"))
      (node (ref "MUX_I2C2") (pin "S0") (pinfunction "S0_S0") (pintype "bidirectional"))
      (node (ref "MUX_I2C3") (pin "S0") (pinfunction "S0_S0") (pintype "bidirectional"))
      (node (ref "SV1") (pin "12") (pinfunction "12_12") (pintype "passive"))
    )
    (net (code "8") (name "S1") (class "Default")
      (node (ref "MUX_I2C0") (pin "S1") (pinfunction "S1_S1") (pintype "bidirectional"))
      (node (ref "MUX_I2C1") (pin "S1") (pinfunction "S1_S1") (pintype "bidirectional"))
      (node (ref "MUX_I2C2") (pin "S1") (pinfunction "S1_S1") (pintype "bidirectional"))
      (node (ref "MUX_I2C3") (pin "S1") (pinfunction "S1_S1") (pintype "bidirectional"))
      (node (ref "SV1") (pin "13") (pinfunction "13_13") (pintype "passive"))
    )
    (net (code "9") (name "SCL0") (class "Default")
      (node (ref "MUX_I2C0") (pin "2A") (pinfunction "2A_2A") (pintype "bidirectional"))
      (node (ref "R3") (pin "1") (pinfunction "1_1") (pintype "passive"))
      (node (ref "SV4") (pin "3") (pinfunction "3_3") (pintype "passive"))
    )
    (net (code "10") (name "SCL0_0") (class "Default")
      (node (ref "1") (pin "SCL") (pinfunction "SCL_SCL") (pintype "bidirectional"))
      (node (ref "2") (pin "SCL") (pinfunction "SCL_SCL") (pintype "bidirectional"))
      (node (ref "3") (pin "SCL") (pinfunction "SCL_SCL") (pintype "bidirectional"))
      (node (ref "4") (pin "SCL") (pinfunction "SCL_SCL") (pintype "bidirectional"))
      (node (ref "MUX_I2C0") (pin "2B1") (pinfunction "2B1_2B1") (pintype "bidirectional"))
    )
    (net (code "11") (name "SCL0_1") (class "Default")
      (node (ref "5") (pin "SCL") (pinfunction "SCL_SCL") (pintype "bidirectional"))
      (node (ref "6") (pin "SCL") (pinfunction "SCL_SCL") (pintype "bidirectional"))
      (node (ref "7") (pin "SCL") (pinfunction "SCL_SCL") (pintype "bidirectional"))
      (node (ref "8") (pin "SCL") (pinfunction "SCL_SCL") (pintype "bidirectional"))
      (node (ref "MUX_I2C0") (pin "2B2") (pinfunction "2B2_2B2") (pintype "bidirectional"))
    )
    (net (code "12") (name "SCL0_2") (class "Default")
      (node (ref "10") (pin "SCL") (pinfunction "SCL_SCL") (pintype "bidirectional"))
      (node (ref "11") (pin "SCL") (pinfunction "SCL_SCL") (pintype "bidirectional"))
      (node (ref "12") (pin "SCL") (pinfunction "SCL_SCL") (pintype "bidirectional"))
      (node (ref "9") (pin "SCL") (pinfunction "SCL_SCL") (pintype "bidirectional"))
      (node (ref "MUX_I2C0") (pin "2B3") (pinfunction "2B3_2B3") (pintype "bidirectional"))
    )
    (net (code "13") (name "SCL0_3") (class "Default")
      (node (ref "13") (pin "SCL") (pinfunction "SCL_SCL") (pintype "bidirectional"))
      (node (ref "14") (pin "SCL") (pinfunction "SCL_SCL") (pintype "bidirectional"))
      (node (ref "15") (pin "SCL") (pinfunction "SCL_SCL") (pintype "bidirectional"))
      (node (ref "16") (pin "SCL") (pinfunction "SCL_SCL") (pintype "bidirectional"))
      (node (ref "MUX_I2C0") (pin "2B4") (pinfunction "2B4_2B4") (pintype "bidirectional"))
    )
    (net (code "14") (name "SCL1") (class "Default")
      (node (ref "MUX_I2C1") (pin "2A") (pinfunction "2A_2A") (pintype "bidirectional"))
      (node (ref "R6") (pin "1") (pinfunction "1_1") (pintype "passive"))
      (node (ref "SV3") (pin "5") (pinfunction "5_5") (pintype "passive"))
    )
    (net (code "15") (name "SCL1_0") (class "Default")
      (node (ref "17") (pin "SCL") (pinfunction "SCL_SCL") (pintype "bidirectional"))
      (node (ref "18") (pin "SCL") (pinfunction "SCL_SCL") (pintype "bidirectional"))
      (node (ref "19") (pin "SCL") (pinfunction "SCL_SCL") (pintype "bidirectional"))
      (node (ref "20") (pin "SCL") (pinfunction "SCL_SCL") (pintype "bidirectional"))
      (node (ref "MUX_I2C1") (pin "2B1") (pinfunction "2B1_2B1") (pintype "bidirectional"))
    )
    (net (code "16") (name "SCL1_1") (class "Default")
      (node (ref "21") (pin "SCL") (pinfunction "SCL_SCL") (pintype "bidirectional"))
      (node (ref "22") (pin "SCL") (pinfunction "SCL_SCL") (pintype "bidirectional"))
      (node (ref "23") (pin "SCL") (pinfunction "SCL_SCL") (pintype "bidirectional"))
      (node (ref "24") (pin "SCL") (pinfunction "SCL_SCL") (pintype "bidirectional"))
      (node (ref "MUX_I2C1") (pin "2B2") (pinfunction "2B2_2B2") (pintype "bidirectional"))
    )
    (net (code "17") (name "SCL1_2") (class "Default")
      (node (ref "25") (pin "SCL") (pinfunction "SCL_SCL") (pintype "bidirectional"))
      (node (ref "26") (pin "SCL") (pinfunction "SCL_SCL") (pintype "bidirectional"))
      (node (ref "27") (pin "SCL") (pinfunction "SCL_SCL") (pintype "bidirectional"))
      (node (ref "28") (pin "SCL") (pinfunction "SCL_SCL") (pintype "bidirectional"))
      (node (ref "MUX_I2C1") (pin "2B3") (pinfunction "2B3_2B3") (pintype "bidirectional"))
    )
    (net (code "18") (name "SCL1_3") (class "Default")
      (node (ref "29") (pin "SCL") (pinfunction "SCL_SCL") (pintype "bidirectional"))
      (node (ref "30") (pin "SCL") (pinfunction "SCL_SCL") (pintype "bidirectional"))
      (node (ref "31") (pin "SCL") (pinfunction "SCL_SCL") (pintype "bidirectional"))
      (node (ref "32") (pin "SCL") (pinfunction "SCL_SCL") (pintype "bidirectional"))
      (node (ref "MUX_I2C1") (pin "2B4") (pinfunction "2B4_2B4") (pintype "bidirectional"))
    )
    (net (code "19") (name "SCL2") (class "Default")
      (node (ref "MUX_I2C2") (pin "2A") (pinfunction "2A_2A") (pintype "bidirectional"))
      (node (ref "R8") (pin "1") (pinfunction "1_1") (pintype "passive"))
      (node (ref "SV1") (pin "5") (pinfunction "5_5") (pintype "passive"))
    )
    (net (code "20") (name "SCL2_0") (class "Default")
      (node (ref "33") (pin "SCL") (pinfunction "SCL_SCL") (pintype "bidirectional"))
      (node (ref "34") (pin "SCL") (pinfunction "SCL_SCL") (pintype "bidirectional"))
      (node (ref "35") (pin "SCL") (pinfunction "SCL_SCL") (pintype "bidirectional"))
      (node (ref "36") (pin "SCL") (pinfunction "SCL_SCL") (pintype "bidirectional"))
      (node (ref "MUX_I2C2") (pin "2B1") (pinfunction "2B1_2B1") (pintype "bidirectional"))
    )
    (net (code "21") (name "SCL2_1") (class "Default")
      (node (ref "37") (pin "SCL") (pinfunction "SCL_SCL") (pintype "bidirectional"))
      (node (ref "38") (pin "SCL") (pinfunction "SCL_SCL") (pintype "bidirectional"))
      (node (ref "39") (pin "SCL") (pinfunction "SCL_SCL") (pintype "bidirectional"))
      (node (ref "40") (pin "SCL") (pinfunction "SCL_SCL") (pintype "bidirectional"))
      (node (ref "MUX_I2C2") (pin "2B2") (pinfunction "2B2_2B2") (pintype "bidirectional"))
    )
    (net (code "22") (name "SCL2_2") (class "Default")
      (node (ref "41") (pin "SCL") (pinfunction "SCL_SCL") (pintype "bidirectional"))
      (node (ref "42") (pin "SCL") (pinfunction "SCL_SCL") (pintype "bidirectional"))
      (node (ref "43") (pin "SCL") (pinfunction "SCL_SCL") (pintype "bidirectional"))
      (node (ref "44") (pin "SCL") (pinfunction "SCL_SCL") (pintype "bidirectional"))
      (node (ref "MUX_I2C2") (pin "2B3") (pinfunction "2B3_2B3") (pintype "bidirectional"))
    )
    (net (code "23") (name "SCL2_3") (class "Default")
      (node (ref "45") (pin "SCL") (pinfunction "SCL_SCL") (pintype "bidirectional"))
      (node (ref "46") (pin "SCL") (pinfunction "SCL_SCL") (pintype "bidirectional"))
      (node (ref "47") (pin "SCL") (pinfunction "SCL_SCL") (pintype "bidirectional"))
      (node (ref "48") (pin "SCL") (pinfunction "SCL_SCL") (pintype "bidirectional"))
      (node (ref "MUX_I2C2") (pin "2B4") (pinfunction "2B4_2B4") (pintype "bidirectional"))
    )
    (net (code "24") (name "SCL3") (class "Default")
      (node (ref "MUX_I2C3") (pin "2A") (pinfunction "2A_2A") (pintype "bidirectional"))
      (node (ref "R4") (pin "1") (pinfunction "1_1") (pintype "passive"))
      (node (ref "SV5") (pin "1") (pinfunction "1_1") (pintype "passive"))
    )
    (net (code "25") (name "SCL3_0") (class "Default")
      (node (ref "49") (pin "SCL") (pinfunction "SCL_SCL") (pintype "bidirectional"))
      (node (ref "50") (pin "SCL") (pinfunction "SCL_SCL") (pintype "bidirectional"))
      (node (ref "51") (pin "SCL") (pinfunction "SCL_SCL") (pintype "bidirectional"))
      (node (ref "52") (pin "SCL") (pinfunction "SCL_SCL") (pintype "bidirectional"))
      (node (ref "MUX_I2C3") (pin "2B1") (pinfunction "2B1_2B1") (pintype "bidirectional"))
    )
    (net (code "26") (name "SCL3_1") (class "Default")
      (node (ref "53") (pin "SCL") (pinfunction "SCL_SCL") (pintype "bidirectional"))
      (node (ref "54") (pin "SCL") (pinfunction "SCL_SCL") (pintype "bidirectional"))
      (node (ref "55") (pin "SCL") (pinfunction "SCL_SCL") (pintype "bidirectional"))
      (node (ref "56") (pin "SCL") (pinfunction "SCL_SCL") (pintype "bidirectional"))
      (node (ref "MUX_I2C3") (pin "2B2") (pinfunction "2B2_2B2") (pintype "bidirectional"))
    )
    (net (code "27") (name "SCL3_2") (class "Default")
      (node (ref "57") (pin "SCL") (pinfunction "SCL_SCL") (pintype "bidirectional"))
      (node (ref "58") (pin "SCL") (pinfunction "SCL_SCL") (pintype "bidirectional"))
      (node (ref "59") (pin "SCL") (pinfunction "SCL_SCL") (pintype "bidirectional"))
      (node (ref "60") (pin "SCL") (pinfunction "SCL_SCL") (pintype "bidirectional"))
      (node (ref "MUX_I2C3") (pin "2B3") (pinfunction "2B3_2B3") (pintype "bidirectional"))
    )
    (net (code "28") (name "SCL3_3") (class "Default")
      (node (ref "61") (pin "SCL") (pinfunction "SCL_SCL") (pintype "bidirectional"))
      (node (ref "62") (pin "SCL") (pinfunction "SCL_SCL") (pintype "bidirectional"))
      (node (ref "63") (pin "SCL") (pinfunction "SCL_SCL") (pintype "bidirectional"))
      (node (ref "64") (pin "SCL") (pinfunction "SCL_SCL") (pintype "bidirectional"))
      (node (ref "MUX_I2C3") (pin "2B4") (pinfunction "2B4_2B4") (pintype "bidirectional"))
    )
    (net (code "29") (name "SDA0") (class "Default")
      (node (ref "MUX_I2C0") (pin "1A") (pinfunction "1A_1A") (pintype "bidirectional"))
      (node (ref "R2") (pin "1") (pinfunction "1_1") (pintype "passive"))
      (node (ref "SV4") (pin "2") (pinfunction "2_2") (pintype "passive"))
    )
    (net (code "30") (name "SDA0_0") (class "Default")
      (node (ref "1") (pin "SDA") (pinfunction "SDA/MOSI_SDA") (pintype "bidirectional"))
      (node (ref "2") (pin "SDA") (pinfunction "SDA/MOSI_SDA") (pintype "bidirectional"))
      (node (ref "3") (pin "SDA") (pinfunction "SDA/MOSI_SDA") (pintype "bidirectional"))
      (node (ref "4") (pin "SDA") (pinfunction "SDA/MOSI_SDA") (pintype "bidirectional"))
      (node (ref "MUX_I2C0") (pin "1B1") (pinfunction "1B1_1B1") (pintype "bidirectional"))
    )
    (net (code "31") (name "SDA0_1") (class "Default")
      (node (ref "5") (pin "SDA") (pinfunction "SDA/MOSI_SDA") (pintype "bidirectional"))
      (node (ref "6") (pin "SDA") (pinfunction "SDA/MOSI_SDA") (pintype "bidirectional"))
      (node (ref "7") (pin "SDA") (pinfunction "SDA/MOSI_SDA") (pintype "bidirectional"))
      (node (ref "8") (pin "SDA") (pinfunction "SDA/MOSI_SDA") (pintype "bidirectional"))
      (node (ref "MUX_I2C0") (pin "1B2") (pinfunction "1B2_1B2") (pintype "bidirectional"))
    )
    (net (code "32") (name "SDA0_2") (class "Default")
      (node (ref "10") (pin "SDA") (pinfunction "SDA/MOSI_SDA") (pintype "bidirectional"))
      (node (ref "11") (pin "SDA") (pinfunction "SDA/MOSI_SDA") (pintype "bidirectional"))
      (node (ref "12") (pin "SDA") (pinfunction "SDA/MOSI_SDA") (pintype "bidirectional"))
      (node (ref "9") (pin "SDA") (pinfunction "SDA/MOSI_SDA") (pintype "bidirectional"))
      (node (ref "MUX_I2C0") (pin "1B3") (pinfunction "1B3_1B3") (pintype "bidirectional"))
    )
    (net (code "33") (name "SDA0_3") (class "Default")
      (node (ref "13") (pin "SDA") (pinfunction "SDA/MOSI_SDA") (pintype "bidirectional"))
      (node (ref "14") (pin "SDA") (pinfunction "SDA/MOSI_SDA") (pintype "bidirectional"))
      (node (ref "15") (pin "SDA") (pinfunction "SDA/MOSI_SDA") (pintype "bidirectional"))
      (node (ref "16") (pin "SDA") (pinfunction "SDA/MOSI_SDA") (pintype "bidirectional"))
      (node (ref "MUX_I2C0") (pin "1B4") (pinfunction "1B4_1B4") (pintype "bidirectional"))
    )
    (net (code "34") (name "SDA1") (class "Default")
      (node (ref "MUX_I2C1") (pin "1A") (pinfunction "1A_1A") (pintype "bidirectional"))
      (node (ref "R7") (pin "1") (pinfunction "1_1") (pintype "passive"))
      (node (ref "SV3") (pin "6") (pinfunction "6_6") (pintype "passive"))
    )
    (net (code "35") (name "SDA1_0") (class "Default")
      (node (ref "17") (pin "SDA") (pinfunction "SDA/MOSI_SDA") (pintype "bidirectional"))
      (node (ref "18") (pin "SDA") (pinfunction "SDA/MOSI_SDA") (pintype "bidirectional"))
      (node (ref "19") (pin "SDA") (pinfunction "SDA/MOSI_SDA") (pintype "bidirectional"))
      (node (ref "20") (pin "SDA") (pinfunction "SDA/MOSI_SDA") (pintype "bidirectional"))
      (node (ref "MUX_I2C1") (pin "1B1") (pinfunction "1B1_1B1") (pintype "bidirectional"))
    )
    (net (code "36") (name "SDA1_1") (class "Default")
      (node (ref "21") (pin "SDA") (pinfunction "SDA/MOSI_SDA") (pintype "bidirectional"))
      (node (ref "22") (pin "SDA") (pinfunction "SDA/MOSI_SDA") (pintype "bidirectional"))
      (node (ref "23") (pin "SDA") (pinfunction "SDA/MOSI_SDA") (pintype "bidirectional"))
      (node (ref "24") (pin "SDA") (pinfunction "SDA/MOSI_SDA") (pintype "bidirectional"))
      (node (ref "MUX_I2C1") (pin "1B2") (pinfunction "1B2_1B2") (pintype "bidirectional"))
    )
    (net (code "37") (name "SDA1_2") (class "Default")
      (node (ref "25") (pin "SDA") (pinfunction "SDA/MOSI_SDA") (pintype "bidirectional"))
      (node (ref "26") (pin "SDA") (pinfunction "SDA/MOSI_SDA") (pintype "bidirectional"))
      (node (ref "27") (pin "SDA") (pinfunction "SDA/MOSI_SDA") (pintype "bidirectional"))
      (node (ref "28") (pin "SDA") (pinfunction "SDA/MOSI_SDA") (pintype "bidirectional"))
      (node (ref "MUX_I2C1") (pin "1B3") (pinfunction "1B3_1B3") (pintype "bidirectional"))
    )
    (net (code "38") (name "SDA1_3") (class "Default")
      (node (ref "29") (pin "SDA") (pinfunction "SDA/MOSI_SDA") (pintype "bidirectional"))
      (node (ref "30") (pin "SDA") (pinfunction "SDA/MOSI_SDA") (pintype "bidirectional"))
      (node (ref "31") (pin "SDA") (pinfunction "SDA/MOSI_SDA") (pintype "bidirectional"))
      (node (ref "32") (pin "SDA") (pinfunction "SDA/MOSI_SDA") (pintype "bidirectional"))
      (node (ref "MUX_I2C1") (pin "1B4") (pinfunction "1B4_1B4") (pintype "bidirectional"))
    )
    (net (code "39") (name "SDA2") (class "Default")
      (node (ref "MUX_I2C2") (pin "1A") (pinfunction "1A_1A") (pintype "bidirectional"))
      (node (ref "R9") (pin "1") (pinfunction "1_1") (pintype "passive"))
      (node (ref "SV1") (pin "6") (pinfunction "6_6") (pintype "passive"))
    )
    (net (code "40") (name "SDA2_0") (class "Default")
      (node (ref "33") (pin "SDA") (pinfunction "SDA/MOSI_SDA") (pintype "bidirectional"))
      (node (ref "34") (pin "SDA") (pinfunction "SDA/MOSI_SDA") (pintype "bidirectional"))
      (node (ref "35") (pin "SDA") (pinfunction "SDA/MOSI_SDA") (pintype "bidirectional"))
      (node (ref "36") (pin "SDA") (pinfunction "SDA/MOSI_SDA") (pintype "bidirectional"))
      (node (ref "MUX_I2C2") (pin "1B1") (pinfunction "1B1_1B1") (pintype "bidirectional"))
    )
    (net (code "41") (name "SDA2_1") (class "Default")
      (node (ref "37") (pin "SDA") (pinfunction "SDA/MOSI_SDA") (pintype "bidirectional"))
      (node (ref "38") (pin "SDA") (pinfunction "SDA/MOSI_SDA") (pintype "bidirectional"))
      (node (ref "39") (pin "SDA") (pinfunction "SDA/MOSI_SDA") (pintype "bidirectional"))
      (node (ref "40") (pin "SDA") (pinfunction "SDA/MOSI_SDA") (pintype "bidirectional"))
      (node (ref "MUX_I2C2") (pin "1B2") (pinfunction "1B2_1B2") (pintype "bidirectional"))
    )
    (net (code "42") (name "SDA2_2") (class "Default")
      (node (ref "41") (pin "SDA") (pinfunction "SDA/MOSI_SDA") (pintype "bidirectional"))
      (node (ref "42") (pin "SDA") (pinfunction "SDA/MOSI_SDA") (pintype "bidirectional"))
      (node (ref "43") (pin "SDA") (pinfunction "SDA/MOSI_SDA") (pintype "bidirectional"))
      (node (ref "44") (pin "SDA") (pinfunction "SDA/MOSI_SDA") (pintype "bidirectional"))
      (node (ref "MUX_I2C2") (pin "1B3") (pinfunction "1B3_1B3") (pintype "bidirectional"))
    )
    (net (code "43") (name "SDA2_3") (class "Default")
      (node (ref "45") (pin "SDA") (pinfunction "SDA/MOSI_SDA") (pintype "bidirectional"))
      (node (ref "46") (pin "SDA") (pinfunction "SDA/MOSI_SDA") (pintype "bidirectional"))
      (node (ref "47") (pin "SDA") (pinfunction "SDA/MOSI_SDA") (pintype "bidirectional"))
      (node (ref "48") (pin "SDA") (pinfunction "SDA/MOSI_SDA") (pintype "bidirectional"))
      (node (ref "MUX_I2C2") (pin "1B4") (pinfunction "1B4_1B4") (pintype "bidirectional"))
    )
    (net (code "44") (name "SDA3") (class "Default")
      (node (ref "MUX_I2C3") (pin "1A") (pinfunction "1A_1A") (pintype "bidirectional"))
      (node (ref "R5") (pin "1") (pinfunction "1_1") (pintype "passive"))
      (node (ref "SV5") (pin "3") (pinfunction "3_3") (pintype "passive"))
    )
    (net (code "45") (name "SDA3_0") (class "Default")
      (node (ref "49") (pin "SDA") (pinfunction "SDA/MOSI_SDA") (pintype "bidirectional"))
      (node (ref "50") (pin "SDA") (pinfunction "SDA/MOSI_SDA") (pintype "bidirectional"))
      (node (ref "51") (pin "SDA") (pinfunction "SDA/MOSI_SDA") (pintype "bidirectional"))
      (node (ref "52") (pin "SDA") (pinfunction "SDA/MOSI_SDA") (pintype "bidirectional"))
      (node (ref "MUX_I2C3") (pin "1B1") (pinfunction "1B1_1B1") (pintype "bidirectional"))
    )
    (net (code "46") (name "SDA3_1") (class "Default")
      (node (ref "53") (pin "SDA") (pinfunction "SDA/MOSI_SDA") (pintype "bidirectional"))
      (node (ref "54") (pin "SDA") (pinfunction "SDA/MOSI_SDA") (pintype "bidirectional"))
      (node (ref "55") (pin "SDA") (pinfunction "SDA/MOSI_SDA") (pintype "bidirectional"))
      (node (ref "56") (pin "SDA") (pinfunction "SDA/MOSI_SDA") (pintype "bidirectional"))
      (node (ref "MUX_I2C3") (pin "1B2") (pinfunction "1B2_1B2") (pintype "bidirectional"))
    )
    (net (code "47") (name "SDA3_2") (class "Default")
      (node (ref "57") (pin "SDA") (pinfunction "SDA/MOSI_SDA") (pintype "bidirectional"))
      (node (ref "58") (pin "SDA") (pinfunction "SDA/MOSI_SDA") (pintype "bidirectional"))
      (node (ref "59") (pin "SDA") (pinfunction "SDA/MOSI_SDA") (pintype "bidirectional"))
      (node (ref "60") (pin "SDA") (pinfunction "SDA/MOSI_SDA") (pintype "bidirectional"))
      (node (ref "MUX_I2C3") (pin "1B3") (pinfunction "1B3_1B3") (pintype "bidirectional"))
    )
    (net (code "48") (name "SDA3_3") (class "Default")
      (node (ref "61") (pin "SDA") (pinfunction "SDA/MOSI_SDA") (pintype "bidirectional"))
      (node (ref "62") (pin "SDA") (pinfunction "SDA/MOSI_SDA") (pintype "bidirectional"))
      (node (ref "63") (pin "SDA") (pinfunction "SDA/MOSI_SDA") (pintype "bidirectional"))
      (node (ref "64") (pin "SDA") (pinfunction "SDA/MOSI_SDA") (pintype "bidirectional"))
      (node (ref "MUX_I2C3") (pin "1B4") (pinfunction "1B4_1B4") (pintype "bidirectional"))
    )
    (net (code "49") (name "VDD") (class "Default")
      (node (ref "1") (pin "SENB/CS") (pinfunction "SENB/CS_SENB/CS") (pintype "bidirectional"))
      (node (ref "1") (pin "VDD") (pinfunction "VDD_VDD") (pintype "bidirectional"))
      (node (ref "1") (pin "VDD_IO") (pinfunction "VDD_IO_VDD_IO") (pintype "bidirectional"))
      (node (ref "10") (pin "A0") (pinfunction "A0_A0") (pintype "bidirectional"))
      (node (ref "10") (pin "SENB/CS") (pinfunction "SENB/CS_SENB/CS") (pintype "bidirectional"))
      (node (ref "10") (pin "VDD") (pinfunction "VDD_VDD") (pintype "bidirectional"))
      (node (ref "10") (pin "VDD_IO") (pinfunction "VDD_IO_VDD_IO") (pintype "bidirectional"))
      (node (ref "11") (pin "A1") (pinfunction "A1_A1") (pintype "bidirectional"))
      (node (ref "11") (pin "SENB/CS") (pinfunction "SENB/CS_SENB/CS") (pintype "bidirectional"))
      (node (ref "11") (pin "VDD") (pinfunction "VDD_VDD") (pintype "bidirectional"))
      (node (ref "11") (pin "VDD_IO") (pinfunction "VDD_IO_VDD_IO") (pintype "bidirectional"))
      (node (ref "12") (pin "A0") (pinfunction "A0_A0") (pintype "bidirectional"))
      (node (ref "12") (pin "A1") (pinfunction "A1_A1") (pintype "bidirectional"))
      (node (ref "12") (pin "SENB/CS") (pinfunction "SENB/CS_SENB/CS") (pintype "bidirectional"))
      (node (ref "12") (pin "VDD") (pinfunction "VDD_VDD") (pintype "bidirectional"))
      (node (ref "12") (pin "VDD_IO") (pinfunction "VDD_IO_VDD_IO") (pintype "bidirectional"))
      (node (ref "13") (pin "SENB/CS") (pinfunction "SENB/CS_SENB/CS") (pintype "bidirectional"))
      (node (ref "13") (pin "VDD") (pinfunction "VDD_VDD") (pintype "bidirectional"))
      (node (ref "13") (pin "VDD_IO") (pinfunction "VDD_IO_VDD_IO") (pintype "bidirectional"))
      (node (ref "14") (pin "A0") (pinfunction "A0_A0") (pintype "bidirectional"))
      (node (ref "14") (pin "SENB/CS") (pinfunction "SENB/CS_SENB/CS") (pintype "bidirectional"))
      (node (ref "14") (pin "VDD") (pinfunction "VDD_VDD") (pintype "bidirectional"))
      (node (ref "14") (pin "VDD_IO") (pinfunction "VDD_IO_VDD_IO") (pintype "bidirectional"))
      (node (ref "15") (pin "A1") (pinfunction "A1_A1") (pintype "bidirectional"))
      (node (ref "15") (pin "SENB/CS") (pinfunction "SENB/CS_SENB/CS") (pintype "bidirectional"))
      (node (ref "15") (pin "VDD") (pinfunction "VDD_VDD") (pintype "bidirectional"))
      (node (ref "15") (pin "VDD_IO") (pinfunction "VDD_IO_VDD_IO") (pintype "bidirectional"))
      (node (ref "16") (pin "A0") (pinfunction "A0_A0") (pintype "bidirectional"))
      (node (ref "16") (pin "A1") (pinfunction "A1_A1") (pintype "bidirectional"))
      (node (ref "16") (pin "SENB/CS") (pinfunction "SENB/CS_SENB/CS") (pintype "bidirectional"))
      (node (ref "16") (pin "VDD") (pinfunction "VDD_VDD") (pintype "bidirectional"))
      (node (ref "16") (pin "VDD_IO") (pinfunction "VDD_IO_VDD_IO") (pintype "bidirectional"))
      (node (ref "17") (pin "SENB/CS") (pinfunction "SENB/CS_SENB/CS") (pintype "bidirectional"))
      (node (ref "17") (pin "VDD") (pinfunction "VDD_VDD") (pintype "bidirectional"))
      (node (ref "17") (pin "VDD_IO") (pinfunction "VDD_IO_VDD_IO") (pintype "bidirectional"))
      (node (ref "18") (pin "A0") (pinfunction "A0_A0") (pintype "bidirectional"))
      (node (ref "18") (pin "SENB/CS") (pinfunction "SENB/CS_SENB/CS") (pintype "bidirectional"))
      (node (ref "18") (pin "VDD") (pinfunction "VDD_VDD") (pintype "bidirectional"))
      (node (ref "18") (pin "VDD_IO") (pinfunction "VDD_IO_VDD_IO") (pintype "bidirectional"))
      (node (ref "19") (pin "A1") (pinfunction "A1_A1") (pintype "bidirectional"))
      (node (ref "19") (pin "SENB/CS") (pinfunction "SENB/CS_SENB/CS") (pintype "bidirectional"))
      (node (ref "19") (pin "VDD") (pinfunction "VDD_VDD") (pintype "bidirectional"))
      (node (ref "19") (pin "VDD_IO") (pinfunction "VDD_IO_VDD_IO") (pintype "bidirectional"))
      (node (ref "2") (pin "A0") (pinfunction "A0_A0") (pintype "bidirectional"))
      (node (ref "2") (pin "SENB/CS") (pinfunction "SENB/CS_SENB/CS") (pintype "bidirectional"))
      (node (ref "2") (pin "VDD") (pinfunction "VDD_VDD") (pintype "bidirectional"))
      (node (ref "2") (pin "VDD_IO") (pinfunction "VDD_IO_VDD_IO") (pintype "bidirectional"))
      (node (ref "20") (pin "A0") (pinfunction "A0_A0") (pintype "bidirectional"))
      (node (ref "20") (pin "A1") (pinfunction "A1_A1") (pintype "bidirectional"))
      (node (ref "20") (pin "SENB/CS") (pinfunction "SENB/CS_SENB/CS") (pintype "bidirectional"))
      (node (ref "20") (pin "VDD") (pinfunction "VDD_VDD") (pintype "bidirectional"))
      (node (ref "20") (pin "VDD_IO") (pinfunction "VDD_IO_VDD_IO") (pintype "bidirectional"))
      (node (ref "21") (pin "SENB/CS") (pinfunction "SENB/CS_SENB/CS") (pintype "bidirectional"))
      (node (ref "21") (pin "VDD") (pinfunction "VDD_VDD") (pintype "bidirectional"))
      (node (ref "21") (pin "VDD_IO") (pinfunction "VDD_IO_VDD_IO") (pintype "bidirectional"))
      (node (ref "22") (pin "A0") (pinfunction "A0_A0") (pintype "bidirectional"))
      (node (ref "22") (pin "SENB/CS") (pinfunction "SENB/CS_SENB/CS") (pintype "bidirectional"))
      (node (ref "22") (pin "VDD") (pinfunction "VDD_VDD") (pintype "bidirectional"))
      (node (ref "22") (pin "VDD_IO") (pinfunction "VDD_IO_VDD_IO") (pintype "bidirectional"))
      (node (ref "23") (pin "A1") (pinfunction "A1_A1") (pintype "bidirectional"))
      (node (ref "23") (pin "SENB/CS") (pinfunction "SENB/CS_SENB/CS") (pintype "bidirectional"))
      (node (ref "23") (pin "VDD") (pinfunction "VDD_VDD") (pintype "bidirectional"))
      (node (ref "23") (pin "VDD_IO") (pinfunction "VDD_IO_VDD_IO") (pintype "bidirectional"))
      (node (ref "24") (pin "A0") (pinfunction "A0_A0") (pintype "bidirectional"))
      (node (ref "24") (pin "A1") (pinfunction "A1_A1") (pintype "bidirectional"))
      (node (ref "24") (pin "SENB/CS") (pinfunction "SENB/CS_SENB/CS") (pintype "bidirectional"))
      (node (ref "24") (pin "VDD") (pinfunction "VDD_VDD") (pintype "bidirectional"))
      (node (ref "24") (pin "VDD_IO") (pinfunction "VDD_IO_VDD_IO") (pintype "bidirectional"))
      (node (ref "25") (pin "SENB/CS") (pinfunction "SENB/CS_SENB/CS") (pintype "bidirectional"))
      (node (ref "25") (pin "VDD") (pinfunction "VDD_VDD") (pintype "bidirectional"))
      (node (ref "25") (pin "VDD_IO") (pinfunction "VDD_IO_VDD_IO") (pintype "bidirectional"))
      (node (ref "26") (pin "A0") (pinfunction "A0_A0") (pintype "bidirectional"))
      (node (ref "26") (pin "SENB/CS") (pinfunction "SENB/CS_SENB/CS") (pintype "bidirectional"))
      (node (ref "26") (pin "VDD") (pinfunction "VDD_VDD") (pintype "bidirectional"))
      (node (ref "26") (pin "VDD_IO") (pinfunction "VDD_IO_VDD_IO") (pintype "bidirectional"))
      (node (ref "27") (pin "A1") (pinfunction "A1_A1") (pintype "bidirectional"))
      (node (ref "27") (pin "SENB/CS") (pinfunction "SENB/CS_SENB/CS") (pintype "bidirectional"))
      (node (ref "27") (pin "VDD") (pinfunction "VDD_VDD") (pintype "bidirectional"))
      (node (ref "27") (pin "VDD_IO") (pinfunction "VDD_IO_VDD_IO") (pintype "bidirectional"))
      (node (ref "28") (pin "A0") (pinfunction "A0_A0") (pintype "bidirectional"))
      (node (ref "28") (pin "A1") (pinfunction "A1_A1") (pintype "bidirectional"))
      (node (ref "28") (pin "SENB/CS") (pinfunction "SENB/CS_SENB/CS") (pintype "bidirectional"))
      (node (ref "28") (pin "VDD") (pinfunction "VDD_VDD") (pintype "bidirectional"))
      (node (ref "28") (pin "VDD_IO") (pinfunction "VDD_IO_VDD_IO") (pintype "bidirectional"))
      (node (ref "29") (pin "SENB/CS") (pinfunction "SENB/CS_SENB/CS") (pintype "bidirectional"))
      (node (ref "29") (pin "VDD") (pinfunction "VDD_VDD") (pintype "bidirectional"))
      (node (ref "29") (pin "VDD_IO") (pinfunction "VDD_IO_VDD_IO") (pintype "bidirectional"))
      (node (ref "3") (pin "A1") (pinfunction "A1_A1") (pintype "bidirectional"))
      (node (ref "3") (pin "SENB/CS") (pinfunction "SENB/CS_SENB/CS") (pintype "bidirectional"))
      (node (ref "3") (pin "VDD") (pinfunction "VDD_VDD") (pintype "bidirectional"))
      (node (ref "3") (pin "VDD_IO") (pinfunction "VDD_IO_VDD_IO") (pintype "bidirectional"))
      (node (ref "30") (pin "A0") (pinfunction "A0_A0") (pintype "bidirectional"))
      (node (ref "30") (pin "SENB/CS") (pinfunction "SENB/CS_SENB/CS") (pintype "bidirectional"))
      (node (ref "30") (pin "VDD") (pinfunction "VDD_VDD") (pintype "bidirectional"))
      (node (ref "30") (pin "VDD_IO") (pinfunction "VDD_IO_VDD_IO") (pintype "bidirectional"))
      (node (ref "31") (pin "A1") (pinfunction "A1_A1") (pintype "bidirectional"))
      (node (ref "31") (pin "SENB/CS") (pinfunction "SENB/CS_SENB/CS") (pintype "bidirectional"))
      (node (ref "31") (pin "VDD") (pinfunction "VDD_VDD") (pintype "bidirectional"))
      (node (ref "31") (pin "VDD_IO") (pinfunction "VDD_IO_VDD_IO") (pintype "bidirectional"))
      (node (ref "32") (pin "A0") (pinfunction "A0_A0") (pintype "bidirectional"))
      (node (ref "32") (pin "A1") (pinfunction "A1_A1") (pintype "bidirectional"))
      (node (ref "32") (pin "SENB/CS") (pinfunction "SENB/CS_SENB/CS") (pintype "bidirectional"))
      (node (ref "32") (pin "VDD") (pinfunction "VDD_VDD") (pintype "bidirectional"))
      (node (ref "32") (pin "VDD_IO") (pinfunction "VDD_IO_VDD_IO") (pintype "bidirectional"))
      (node (ref "33") (pin "SENB/CS") (pinfunction "SENB/CS_SENB/CS") (pintype "bidirectional"))
      (node (ref "33") (pin "VDD") (pinfunction "VDD_VDD") (pintype "bidirectional"))
      (node (ref "33") (pin "VDD_IO") (pinfunction "VDD_IO_VDD_IO") (pintype "bidirectional"))
      (node (ref "34") (pin "A0") (pinfunction "A0_A0") (pintype "bidirectional"))
      (node (ref "34") (pin "SENB/CS") (pinfunction "SENB/CS_SENB/CS") (pintype "bidirectional"))
      (node (ref "34") (pin "VDD") (pinfunction "VDD_VDD") (pintype "bidirectional"))
      (node (ref "34") (pin "VDD_IO") (pinfunction "VDD_IO_VDD_IO") (pintype "bidirectional"))
      (node (ref "35") (pin "A1") (pinfunction "A1_A1") (pintype "bidirectional"))
      (node (ref "35") (pin "SENB/CS") (pinfunction "SENB/CS_SENB/CS") (pintype "bidirectional"))
      (node (ref "35") (pin "VDD") (pinfunction "VDD_VDD") (pintype "bidirectional"))
      (node (ref "35") (pin "VDD_IO") (pinfunction "VDD_IO_VDD_IO") (pintype "bidirectional"))
      (node (ref "36") (pin "A0") (pinfunction "A0_A0") (pintype "bidirectional"))
      (node (ref "36") (pin "A1") (pinfunction "A1_A1") (pintype "bidirectional"))
      (node (ref "36") (pin "SENB/CS") (pinfunction "SENB/CS_SENB/CS") (pintype "bidirectional"))
      (node (ref "36") (pin "VDD") (pinfunction "VDD_VDD") (pintype "bidirectional"))
      (node (ref "36") (pin "VDD_IO") (pinfunction "VDD_IO_VDD_IO") (pintype "bidirectional"))
      (node (ref "37") (pin "SENB/CS") (pinfunction "SENB/CS_SENB/CS") (pintype "bidirectional"))
      (node (ref "37") (pin "VDD") (pinfunction "VDD_VDD") (pintype "bidirectional"))
      (node (ref "37") (pin "VDD_IO") (pinfunction "VDD_IO_VDD_IO") (pintype "bidirectional"))
      (node (ref "38") (pin "A0") (pinfunction "A0_A0") (pintype "bidirectional"))
      (node (ref "38") (pin "SENB/CS") (pinfunction "SENB/CS_SENB/CS") (pintype "bidirectional"))
      (node (ref "38") (pin "VDD") (pinfunction "VDD_VDD") (pintype "bidirectional"))
      (node (ref "38") (pin "VDD_IO") (pinfunction "VDD_IO_VDD_IO") (pintype "bidirectional"))
      (node (ref "39") (pin "A1") (pinfunction "A1_A1") (pintype "bidirectional"))
      (node (ref "39") (pin "SENB/CS") (pinfunction "SENB/CS_SENB/CS") (pintype "bidirectional"))
      (node (ref "39") (pin "VDD") (pinfunction "VDD_VDD") (pintype "bidirectional"))
      (node (ref "39") (pin "VDD_IO") (pinfunction "VDD_IO_VDD_IO") (pintype "bidirectional"))
      (node (ref "4") (pin "A0") (pinfunction "A0_A0") (pintype "bidirectional"))
      (node (ref "4") (pin "A1") (pinfunction "A1_A1") (pintype "bidirectional"))
      (node (ref "4") (pin "SENB/CS") (pinfunction "SENB/CS_SENB/CS") (pintype "bidirectional"))
      (node (ref "4") (pin "VDD") (pinfunction "VDD_VDD") (pintype "bidirectional"))
      (node (ref "4") (pin "VDD_IO") (pinfunction "VDD_IO_VDD_IO") (pintype "bidirectional"))
      (node (ref "40") (pin "A0") (pinfunction "A0_A0") (pintype "bidirectional"))
      (node (ref "40") (pin "A1") (pinfunction "A1_A1") (pintype "bidirectional"))
      (node (ref "40") (pin "SENB/CS") (pinfunction "SENB/CS_SENB/CS") (pintype "bidirectional"))
      (node (ref "40") (pin "VDD") (pinfunction "VDD_VDD") (pintype "bidirectional"))
      (node (ref "40") (pin "VDD_IO") (pinfunction "VDD_IO_VDD_IO") (pintype "bidirectional"))
      (node (ref "41") (pin "SENB/CS") (pinfunction "SENB/CS_SENB/CS") (pintype "bidirectional"))
      (node (ref "41") (pin "VDD") (pinfunction "VDD_VDD") (pintype "bidirectional"))
      (node (ref "41") (pin "VDD_IO") (pinfunction "VDD_IO_VDD_IO") (pintype "bidirectional"))
      (node (ref "42") (pin "A0") (pinfunction "A0_A0") (pintype "bidirectional"))
      (node (ref "42") (pin "SENB/CS") (pinfunction "SENB/CS_SENB/CS") (pintype "bidirectional"))
      (node (ref "42") (pin "VDD") (pinfunction "VDD_VDD") (pintype "bidirectional"))
      (node (ref "42") (pin "VDD_IO") (pinfunction "VDD_IO_VDD_IO") (pintype "bidirectional"))
      (node (ref "43") (pin "A1") (pinfunction "A1_A1") (pintype "bidirectional"))
      (node (ref "43") (pin "SENB/CS") (pinfunction "SENB/CS_SENB/CS") (pintype "bidirectional"))
      (node (ref "43") (pin "VDD") (pinfunction "VDD_VDD") (pintype "bidirectional"))
      (node (ref "43") (pin "VDD_IO") (pinfunction "VDD_IO_VDD_IO") (pintype "bidirectional"))
      (node (ref "44") (pin "A0") (pinfunction "A0_A0") (pintype "bidirectional"))
      (node (ref "44") (pin "A1") (pinfunction "A1_A1") (pintype "bidirectional"))
      (node (ref "44") (pin "SENB/CS") (pinfunction "SENB/CS_SENB/CS") (pintype "bidirectional"))
      (node (ref "44") (pin "VDD") (pinfunction "VDD_VDD") (pintype "bidirectional"))
      (node (ref "44") (pin "VDD_IO") (pinfunction "VDD_IO_VDD_IO") (pintype "bidirectional"))
      (node (ref "45") (pin "SENB/CS") (pinfunction "SENB/CS_SENB/CS") (pintype "bidirectional"))
      (node (ref "45") (pin "VDD") (pinfunction "VDD_VDD") (pintype "bidirectional"))
      (node (ref "45") (pin "VDD_IO") (pinfunction "VDD_IO_VDD_IO") (pintype "bidirectional"))
      (node (ref "46") (pin "A0") (pinfunction "A0_A0") (pintype "bidirectional"))
      (node (ref "46") (pin "SENB/CS") (pinfunction "SENB/CS_SENB/CS") (pintype "bidirectional"))
      (node (ref "46") (pin "VDD") (pinfunction "VDD_VDD") (pintype "bidirectional"))
      (node (ref "46") (pin "VDD_IO") (pinfunction "VDD_IO_VDD_IO") (pintype "bidirectional"))
      (node (ref "47") (pin "A1") (pinfunction "A1_A1") (pintype "bidirectional"))
      (node (ref "47") (pin "SENB/CS") (pinfunction "SENB/CS_SENB/CS") (pintype "bidirectional"))
      (node (ref "47") (pin "VDD") (pinfunction "VDD_VDD") (pintype "bidirectional"))
      (node (ref "47") (pin "VDD_IO") (pinfunction "VDD_IO_VDD_IO") (pintype "bidirectional"))
      (node (ref "48") (pin "A0") (pinfunction "A0_A0") (pintype "bidirectional"))
      (node (ref "48") (pin "A1") (pinfunction "A1_A1") (pintype "bidirectional"))
      (node (ref "48") (pin "SENB/CS") (pinfunction "SENB/CS_SENB/CS") (pintype "bidirectional"))
      (node (ref "48") (pin "VDD") (pinfunction "VDD_VDD") (pintype "bidirectional"))
      (node (ref "48") (pin "VDD_IO") (pinfunction "VDD_IO_VDD_IO") (pintype "bidirectional"))
      (node (ref "49") (pin "SENB/CS") (pinfunction "SENB/CS_SENB/CS") (pintype "bidirectional"))
      (node (ref "49") (pin "VDD") (pinfunction "VDD_VDD") (pintype "bidirectional"))
      (node (ref "49") (pin "VDD_IO") (pinfunction "VDD_IO_VDD_IO") (pintype "bidirectional"))
      (node (ref "5") (pin "SENB/CS") (pinfunction "SENB/CS_SENB/CS") (pintype "bidirectional"))
      (node (ref "5") (pin "VDD") (pinfunction "VDD_VDD") (pintype "bidirectional"))
      (node (ref "5") (pin "VDD_IO") (pinfunction "VDD_IO_VDD_IO") (pintype "bidirectional"))
      (node (ref "50") (pin "A0") (pinfunction "A0_A0") (pintype "bidirectional"))
      (node (ref "50") (pin "SENB/CS") (pinfunction "SENB/CS_SENB/CS") (pintype "bidirectional"))
      (node (ref "50") (pin "VDD") (pinfunction "VDD_VDD") (pintype "bidirectional"))
      (node (ref "50") (pin "VDD_IO") (pinfunction "VDD_IO_VDD_IO") (pintype "bidirectional"))
      (node (ref "51") (pin "A1") (pinfunction "A1_A1") (pintype "bidirectional"))
      (node (ref "51") (pin "SENB/CS") (pinfunction "SENB/CS_SENB/CS") (pintype "bidirectional"))
      (node (ref "51") (pin "VDD") (pinfunction "VDD_VDD") (pintype "bidirectional"))
      (node (ref "51") (pin "VDD_IO") (pinfunction "VDD_IO_VDD_IO") (pintype "bidirectional"))
      (node (ref "52") (pin "A0") (pinfunction "A0_A0") (pintype "bidirectional"))
      (node (ref "52") (pin "A1") (pinfunction "A1_A1") (pintype "bidirectional"))
      (node (ref "52") (pin "SENB/CS") (pinfunction "SENB/CS_SENB/CS") (pintype "bidirectional"))
      (node (ref "52") (pin "VDD") (pinfunction "VDD_VDD") (pintype "bidirectional"))
      (node (ref "52") (pin "VDD_IO") (pinfunction "VDD_IO_VDD_IO") (pintype "bidirectional"))
      (node (ref "53") (pin "SENB/CS") (pinfunction "SENB/CS_SENB/CS") (pintype "bidirectional"))
      (node (ref "53") (pin "VDD") (pinfunction "VDD_VDD") (pintype "bidirectional"))
      (node (ref "53") (pin "VDD_IO") (pinfunction "VDD_IO_VDD_IO") (pintype "bidirectional"))
      (node (ref "54") (pin "A0") (pinfunction "A0_A0") (pintype "bidirectional"))
      (node (ref "54") (pin "SENB/CS") (pinfunction "SENB/CS_SENB/CS") (pintype "bidirectional"))
      (node (ref "54") (pin "VDD") (pinfunction "VDD_VDD") (pintype "bidirectional"))
      (node (ref "54") (pin "VDD_IO") (pinfunction "VDD_IO_VDD_IO") (pintype "bidirectional"))
      (node (ref "55") (pin "A1") (pinfunction "A1_A1") (pintype "bidirectional"))
      (node (ref "55") (pin "SENB/CS") (pinfunction "SENB/CS_SENB/CS") (pintype "bidirectional"))
      (node (ref "55") (pin "VDD") (pinfunction "VDD_VDD") (pintype "bidirectional"))
      (node (ref "55") (pin "VDD_IO") (pinfunction "VDD_IO_VDD_IO") (pintype "bidirectional"))
      (node (ref "56") (pin "A0") (pinfunction "A0_A0") (pintype "bidirectional"))
      (node (ref "56") (pin "A1") (pinfunction "A1_A1") (pintype "bidirectional"))
      (node (ref "56") (pin "SENB/CS") (pinfunction "SENB/CS_SENB/CS") (pintype "bidirectional"))
      (node (ref "56") (pin "VDD") (pinfunction "VDD_VDD") (pintype "bidirectional"))
      (node (ref "56") (pin "VDD_IO") (pinfunction "VDD_IO_VDD_IO") (pintype "bidirectional"))
      (node (ref "57") (pin "SENB/CS") (pinfunction "SENB/CS_SENB/CS") (pintype "bidirectional"))
      (node (ref "57") (pin "VDD") (pinfunction "VDD_VDD") (pintype "bidirectional"))
      (node (ref "57") (pin "VDD_IO") (pinfunction "VDD_IO_VDD_IO") (pintype "bidirectional"))
      (node (ref "58") (pin "A0") (pinfunction "A0_A0") (pintype "bidirectional"))
      (node (ref "58") (pin "SENB/CS") (pinfunction "SENB/CS_SENB/CS") (pintype "bidirectional"))
      (node (ref "58") (pin "VDD") (pinfunction "VDD_VDD") (pintype "bidirectional"))
      (node (ref "58") (pin "VDD_IO") (pinfunction "VDD_IO_VDD_IO") (pintype "bidirectional"))
      (node (ref "59") (pin "A1") (pinfunction "A1_A1") (pintype "bidirectional"))
      (node (ref "59") (pin "SENB/CS") (pinfunction "SENB/CS_SENB/CS") (pintype "bidirectional"))
      (node (ref "59") (pin "VDD") (pinfunction "VDD_VDD") (pintype "bidirectional"))
      (node (ref "59") (pin "VDD_IO") (pinfunction "VDD_IO_VDD_IO") (pintype "bidirectional"))
      (node (ref "6") (pin "A0") (pinfunction "A0_A0") (pintype "bidirectional"))
      (node (ref "6") (pin "SENB/CS") (pinfunction "SENB/CS_SENB/CS") (pintype "bidirectional"))
      (node (ref "6") (pin "VDD") (pinfunction "VDD_VDD") (pintype "bidirectional"))
      (node (ref "6") (pin "VDD_IO") (pinfunction "VDD_IO_VDD_IO") (pintype "bidirectional"))
      (node (ref "60") (pin "A0") (pinfunction "A0_A0") (pintype "bidirectional"))
      (node (ref "60") (pin "A1") (pinfunction "A1_A1") (pintype "bidirectional"))
      (node (ref "60") (pin "SENB/CS") (pinfunction "SENB/CS_SENB/CS") (pintype "bidirectional"))
      (node (ref "60") (pin "VDD") (pinfunction "VDD_VDD") (pintype "bidirectional"))
      (node (ref "60") (pin "VDD_IO") (pinfunction "VDD_IO_VDD_IO") (pintype "bidirectional"))
      (node (ref "61") (pin "SENB/CS") (pinfunction "SENB/CS_SENB/CS") (pintype "bidirectional"))
      (node (ref "61") (pin "VDD") (pinfunction "VDD_VDD") (pintype "bidirectional"))
      (node (ref "61") (pin "VDD_IO") (pinfunction "VDD_IO_VDD_IO") (pintype "bidirectional"))
      (node (ref "62") (pin "A0") (pinfunction "A0_A0") (pintype "bidirectional"))
      (node (ref "62") (pin "SENB/CS") (pinfunction "SENB/CS_SENB/CS") (pintype "bidirectional"))
      (node (ref "62") (pin "VDD") (pinfunction "VDD_VDD") (pintype "bidirectional"))
      (node (ref "62") (pin "VDD_IO") (pinfunction "VDD_IO_VDD_IO") (pintype "bidirectional"))
      (node (ref "63") (pin "A1") (pinfunction "A1_A1") (pintype "bidirectional"))
      (node (ref "63") (pin "SENB/CS") (pinfunction "SENB/CS_SENB/CS") (pintype "bidirectional"))
      (node (ref "63") (pin "VDD") (pinfunction "VDD_VDD") (pintype "bidirectional"))
      (node (ref "63") (pin "VDD_IO") (pinfunction "VDD_IO_VDD_IO") (pintype "bidirectional"))
      (node (ref "64") (pin "A0") (pinfunction "A0_A0") (pintype "bidirectional"))
      (node (ref "64") (pin "A1") (pinfunction "A1_A1") (pintype "bidirectional"))
      (node (ref "64") (pin "SENB/CS") (pinfunction "SENB/CS_SENB/CS") (pintype "bidirectional"))
      (node (ref "64") (pin "VDD") (pinfunction "VDD_VDD") (pintype "bidirectional"))
      (node (ref "64") (pin "VDD_IO") (pinfunction "VDD_IO_VDD_IO") (pintype "bidirectional"))
      (node (ref "7") (pin "A1") (pinfunction "A1_A1") (pintype "bidirectional"))
      (node (ref "7") (pin "SENB/CS") (pinfunction "SENB/CS_SENB/CS") (pintype "bidirectional"))
      (node (ref "7") (pin "VDD") (pinfunction "VDD_VDD") (pintype "bidirectional"))
      (node (ref "7") (pin "VDD_IO") (pinfunction "VDD_IO_VDD_IO") (pintype "bidirectional"))
      (node (ref "8") (pin "A0") (pinfunction "A0_A0") (pintype "bidirectional"))
      (node (ref "8") (pin "A1") (pinfunction "A1_A1") (pintype "bidirectional"))
      (node (ref "8") (pin "SENB/CS") (pinfunction "SENB/CS_SENB/CS") (pintype "bidirectional"))
      (node (ref "8") (pin "VDD") (pinfunction "VDD_VDD") (pintype "bidirectional"))
      (node (ref "8") (pin "VDD_IO") (pinfunction "VDD_IO_VDD_IO") (pintype "bidirectional"))
      (node (ref "9") (pin "SENB/CS") (pinfunction "SENB/CS_SENB/CS") (pintype "bidirectional"))
      (node (ref "9") (pin "VDD") (pinfunction "VDD_VDD") (pintype "bidirectional"))
      (node (ref "9") (pin "VDD_IO") (pinfunction "VDD_IO_VDD_IO") (pintype "bidirectional"))
      (node (ref "C1") (pin "1") (pinfunction "2_1") (pintype "bidirectional"))
      (node (ref "C2") (pin "1") (pinfunction "2_1") (pintype "bidirectional"))
      (node (ref "C3") (pin "1") (pinfunction "2_1") (pintype "bidirectional"))
      (node (ref "C4") (pin "1") (pinfunction "2_1") (pintype "bidirectional"))
      (node (ref "C5") (pin "1") (pinfunction "2_1") (pintype "bidirectional"))
      (node (ref "MUX_I2C0") (pin "VCC") (pinfunction "VCC_VCC") (pintype "bidirectional"))
      (node (ref "MUX_I2C1") (pin "VCC") (pinfunction "VCC_VCC") (pintype "bidirectional"))
      (node (ref "MUX_I2C2") (pin "VCC") (pinfunction "VCC_VCC") (pintype "bidirectional"))
      (node (ref "MUX_I2C3") (pin "VCC") (pinfunction "VCC_VCC") (pintype "bidirectional"))
      (node (ref "R2") (pin "2") (pinfunction "2_2") (pintype "passive"))
      (node (ref "R3") (pin "2") (pinfunction "2_2") (pintype "passive"))
      (node (ref "R4") (pin "2") (pinfunction "2_2") (pintype "passive"))
      (node (ref "R5") (pin "2") (pinfunction "2_2") (pintype "passive"))
      (node (ref "R6") (pin "2") (pinfunction "2_2") (pintype "passive"))
      (node (ref "R7") (pin "2") (pinfunction "2_2") (pintype "passive"))
      (node (ref "R8") (pin "2") (pinfunction "2_2") (pintype "passive"))
      (node (ref "R9") (pin "2") (pinfunction "2_2") (pintype "passive"))
      (node (ref "SV2") (pin "1") (pinfunction "1_1") (pintype "passive"))
      (node (ref "SV6") (pin "2") (pinfunction "2_2") (pintype "passive"))
      (node (ref "U$3") (pin "4") (pinfunction "4_4") (pintype "bidirectional"))
    )
    (net (code "50") (name "unconnected-(1-P$4-Pad4)") (class "Default")
      (node (ref "1") (pin "4") (pinfunction "P$4_4") (pintype "no_connect"))
    )
    (net (code "51") (name "unconnected-(1-P$9-Pad9)") (class "Default")
      (node (ref "1") (pin "9") (pinfunction "P$9_9") (pintype "no_connect"))
    )
    (net (code "52") (name "unconnected-(1-P$10-Pad10)") (class "Default")
      (node (ref "1") (pin "10") (pinfunction "P$10_10") (pintype "no_connect"))
    )
    (net (code "53") (name "unconnected-(1-P$14-Pad14)") (class "Default")
      (node (ref "1") (pin "14") (pinfunction "P$14_14") (pintype "no_connect"))
    )
    (net (code "54") (name "unconnected-(1-P$16-Pad16)") (class "Default")
      (node (ref "1") (pin "16") (pinfunction "P$16_16") (pintype "no_connect"))
    )
    (net (code "55") (name "unconnected-(1-PadINT)") (class "Default")
      (node (ref "1") (pin "INT") (pinfunction "INT_INT") (pintype "bidirectional"))
    )
    (net (code "56") (name "unconnected-(1-PadINT{slash}TRIG)") (class "Default")
      (node (ref "1") (pin "INT/TRIG") (pinfunction "INT/TRIG_INT/TRIG") (pintype "bidirectional"))
    )
    (net (code "57") (name "unconnected-(1-PadMISO)") (class "Default")
      (node (ref "1") (pin "MISO") (pinfunction "MISO_MISO") (pintype "bidirectional"))
    )
    (net (code "58") (name "unconnected-(2-P$4-Pad4)") (class "Default")
      (node (ref "2") (pin "4") (pinfunction "P$4_4") (pintype "no_connect"))
    )
    (net (code "59") (name "unconnected-(2-P$9-Pad9)") (class "Default")
      (node (ref "2") (pin "9") (pinfunction "P$9_9") (pintype "no_connect"))
    )
    (net (code "60") (name "unconnected-(2-P$10-Pad10)") (class "Default")
      (node (ref "2") (pin "10") (pinfunction "P$10_10") (pintype "no_connect"))
    )
    (net (code "61") (name "unconnected-(2-P$14-Pad14)") (class "Default")
      (node (ref "2") (pin "14") (pinfunction "P$14_14") (pintype "no_connect"))
    )
    (net (code "62") (name "unconnected-(2-P$16-Pad16)") (class "Default")
      (node (ref "2") (pin "16") (pinfunction "P$16_16") (pintype "no_connect"))
    )
    (net (code "63") (name "unconnected-(2-PadINT)") (class "Default")
      (node (ref "2") (pin "INT") (pinfunction "INT_INT") (pintype "bidirectional"))
    )
    (net (code "64") (name "unconnected-(2-PadINT{slash}TRIG)") (class "Default")
      (node (ref "2") (pin "INT/TRIG") (pinfunction "INT/TRIG_INT/TRIG") (pintype "bidirectional"))
    )
    (net (code "65") (name "unconnected-(2-PadMISO)") (class "Default")
      (node (ref "2") (pin "MISO") (pinfunction "MISO_MISO") (pintype "bidirectional"))
    )
    (net (code "66") (name "unconnected-(3-P$4-Pad4)") (class "Default")
      (node (ref "3") (pin "4") (pinfunction "P$4_4") (pintype "no_connect"))
    )
    (net (code "67") (name "unconnected-(3-P$9-Pad9)") (class "Default")
      (node (ref "3") (pin "9") (pinfunction "P$9_9") (pintype "no_connect"))
    )
    (net (code "68") (name "unconnected-(3-P$10-Pad10)") (class "Default")
      (node (ref "3") (pin "10") (pinfunction "P$10_10") (pintype "no_connect"))
    )
    (net (code "69") (name "unconnected-(3-P$14-Pad14)") (class "Default")
      (node (ref "3") (pin "14") (pinfunction "P$14_14") (pintype "no_connect"))
    )
    (net (code "70") (name "unconnected-(3-P$16-Pad16)") (class "Default")
      (node (ref "3") (pin "16") (pinfunction "P$16_16") (pintype "no_connect"))
    )
    (net (code "71") (name "unconnected-(3-PadINT)") (class "Default")
      (node (ref "3") (pin "INT") (pinfunction "INT_INT") (pintype "bidirectional"))
    )
    (net (code "72") (name "unconnected-(3-PadINT{slash}TRIG)") (class "Default")
      (node (ref "3") (pin "INT/TRIG") (pinfunction "INT/TRIG_INT/TRIG") (pintype "bidirectional"))
    )
    (net (code "73") (name "unconnected-(3-PadMISO)") (class "Default")
      (node (ref "3") (pin "MISO") (pinfunction "MISO_MISO") (pintype "bidirectional"))
    )
    (net (code "74") (name "unconnected-(4-P$4-Pad4)") (class "Default")
      (node (ref "4") (pin "4") (pinfunction "P$4_4") (pintype "no_connect"))
    )
    (net (code "75") (name "unconnected-(4-P$9-Pad9)") (class "Default")
      (node (ref "4") (pin "9") (pinfunction "P$9_9") (pintype "no_connect"))
    )
    (net (code "76") (name "unconnected-(4-P$10-Pad10)") (class "Default")
      (node (ref "4") (pin "10") (pinfunction "P$10_10") (pintype "no_connect"))
    )
    (net (code "77") (name "unconnected-(4-P$14-Pad14)") (class "Default")
      (node (ref "4") (pin "14") (pinfunction "P$14_14") (pintype "no_connect"))
    )
    (net (code "78") (name "unconnected-(4-P$16-Pad16)") (class "Default")
      (node (ref "4") (pin "16") (pinfunction "P$16_16") (pintype "no_connect"))
    )
    (net (code "79") (name "unconnected-(4-PadINT)") (class "Default")
      (node (ref "4") (pin "INT") (pinfunction "INT_INT") (pintype "bidirectional"))
    )
    (net (code "80") (name "unconnected-(4-PadINT{slash}TRIG)") (class "Default")
      (node (ref "4") (pin "INT/TRIG") (pinfunction "INT/TRIG_INT/TRIG") (pintype "bidirectional"))
    )
    (net (code "81") (name "unconnected-(4-PadMISO)") (class "Default")
      (node (ref "4") (pin "MISO") (pinfunction "MISO_MISO") (pintype "bidirectional"))
    )
    (net (code "82") (name "unconnected-(5-P$4-Pad4)") (class "Default")
      (node (ref "5") (pin "4") (pinfunction "P$4_4") (pintype "no_connect"))
    )
    (net (code "83") (name "unconnected-(5-P$9-Pad9)") (class "Default")
      (node (ref "5") (pin "9") (pinfunction "P$9_9") (pintype "no_connect"))
    )
    (net (code "84") (name "unconnected-(5-P$10-Pad10)") (class "Default")
      (node (ref "5") (pin "10") (pinfunction "P$10_10") (pintype "no_connect"))
    )
    (net (code "85") (name "unconnected-(5-P$14-Pad14)") (class "Default")
      (node (ref "5") (pin "14") (pinfunction "P$14_14") (pintype "no_connect"))
    )
    (net (code "86") (name "unconnected-(5-P$16-Pad16)") (class "Default")
      (node (ref "5") (pin "16") (pinfunction "P$16_16") (pintype "no_connect"))
    )
    (net (code "87") (name "unconnected-(5-PadINT)") (class "Default")
      (node (ref "5") (pin "INT") (pinfunction "INT_INT") (pintype "bidirectional"))
    )
    (net (code "88") (name "unconnected-(5-PadINT{slash}TRIG)") (class "Default")
      (node (ref "5") (pin "INT/TRIG") (pinfunction "INT/TRIG_INT/TRIG") (pintype "bidirectional"))
    )
    (net (code "89") (name "unconnected-(5-PadMISO)") (class "Default")
      (node (ref "5") (pin "MISO") (pinfunction "MISO_MISO") (pintype "bidirectional"))
    )
    (net (code "90") (name "unconnected-(6-P$4-Pad4)") (class "Default")
      (node (ref "6") (pin "4") (pinfunction "P$4_4") (pintype "no_connect"))
    )
    (net (code "91") (name "unconnected-(6-P$9-Pad9)") (class "Default")
      (node (ref "6") (pin "9") (pinfunction "P$9_9") (pintype "no_connect"))
    )
    (net (code "92") (name "unconnected-(6-P$10-Pad10)") (class "Default")
      (node (ref "6") (pin "10") (pinfunction "P$10_10") (pintype "no_connect"))
    )
    (net (code "93") (name "unconnected-(6-P$14-Pad14)") (class "Default")
      (node (ref "6") (pin "14") (pinfunction "P$14_14") (pintype "no_connect"))
    )
    (net (code "94") (name "unconnected-(6-P$16-Pad16)") (class "Default")
      (node (ref "6") (pin "16") (pinfunction "P$16_16") (pintype "no_connect"))
    )
    (net (code "95") (name "unconnected-(6-PadINT)") (class "Default")
      (node (ref "6") (pin "INT") (pinfunction "INT_INT") (pintype "bidirectional"))
    )
    (net (code "96") (name "unconnected-(6-PadINT{slash}TRIG)") (class "Default")
      (node (ref "6") (pin "INT/TRIG") (pinfunction "INT/TRIG_INT/TRIG") (pintype "bidirectional"))
    )
    (net (code "97") (name "unconnected-(6-PadMISO)") (class "Default")
      (node (ref "6") (pin "MISO") (pinfunction "MISO_MISO") (pintype "bidirectional"))
    )
    (net (code "98") (name "unconnected-(7-P$4-Pad4)") (class "Default")
      (node (ref "7") (pin "4") (pinfunction "P$4_4") (pintype "no_connect"))
    )
    (net (code "99") (name "unconnected-(7-P$9-Pad9)") (class "Default")
      (node (ref "7") (pin "9") (pinfunction "P$9_9") (pintype "no_connect"))
    )
    (net (code "100") (name "unconnected-(7-P$10-Pad10)") (class "Default")
      (node (ref "7") (pin "10") (pinfunction "P$10_10") (pintype "no_connect"))
    )
    (net (code "101") (name "unconnected-(7-P$14-Pad14)") (class "Default")
      (node (ref "7") (pin "14") (pinfunction "P$14_14") (pintype "no_connect"))
    )
    (net (code "102") (name "unconnected-(7-P$16-Pad16)") (class "Default")
      (node (ref "7") (pin "16") (pinfunction "P$16_16") (pintype "no_connect"))
    )
    (net (code "103") (name "unconnected-(7-PadINT)") (class "Default")
      (node (ref "7") (pin "INT") (pinfunction "INT_INT") (pintype "bidirectional"))
    )
    (net (code "104") (name "unconnected-(7-PadINT{slash}TRIG)") (class "Default")
      (node (ref "7") (pin "INT/TRIG") (pinfunction "INT/TRIG_INT/TRIG") (pintype "bidirectional"))
    )
    (net (code "105") (name "unconnected-(7-PadMISO)") (class "Default")
      (node (ref "7") (pin "MISO") (pinfunction "MISO_MISO") (pintype "bidirectional"))
    )
    (net (code "106") (name "unconnected-(8-P$4-Pad4)") (class "Default")
      (node (ref "8") (pin "4") (pinfunction "P$4_4") (pintype "no_connect"))
    )
    (net (code "107") (name "unconnected-(8-P$9-Pad9)") (class "Default")
      (node (ref "8") (pin "9") (pinfunction "P$9_9") (pintype "no_connect"))
    )
    (net (code "108") (name "unconnected-(8-P$10-Pad10)") (class "Default")
      (node (ref "8") (pin "10") (pinfunction "P$10_10") (pintype "no_connect"))
    )
    (net (code "109") (name "unconnected-(8-P$14-Pad14)") (class "Default")
      (node (ref "8") (pin "14") (pinfunction "P$14_14") (pintype "no_connect"))
    )
    (net (code "110") (name "unconnected-(8-P$16-Pad16)") (class "Default")
      (node (ref "8") (pin "16") (pinfunction "P$16_16") (pintype "no_connect"))
    )
    (net (code "111") (name "unconnected-(8-PadINT)") (class "Default")
      (node (ref "8") (pin "INT") (pinfunction "INT_INT") (pintype "bidirectional"))
    )
    (net (code "112") (name "unconnected-(8-PadINT{slash}TRIG)") (class "Default")
      (node (ref "8") (pin "INT/TRIG") (pinfunction "INT/TRIG_INT/TRIG") (pintype "bidirectional"))
    )
    (net (code "113") (name "unconnected-(8-PadMISO)") (class "Default")
      (node (ref "8") (pin "MISO") (pinfunction "MISO_MISO") (pintype "bidirectional"))
    )
    (net (code "114") (name "unconnected-(9-P$4-Pad4)") (class "Default")
      (node (ref "9") (pin "4") (pinfunction "P$4_4") (pintype "no_connect"))
    )
    (net (code "115") (name "unconnected-(9-P$9-Pad9)") (class "Default")
      (node (ref "9") (pin "9") (pinfunction "P$9_9") (pintype "no_connect"))
    )
    (net (code "116") (name "unconnected-(9-P$10-Pad10)") (class "Default")
      (node (ref "9") (pin "10") (pinfunction "P$10_10") (pintype "no_connect"))
    )
    (net (code "117") (name "unconnected-(9-P$14-Pad14)") (class "Default")
      (node (ref "9") (pin "14") (pinfunction "P$14_14") (pintype "no_connect"))
    )
    (net (code "118") (name "unconnected-(9-P$16-Pad16)") (class "Default")
      (node (ref "9") (pin "16") (pinfunction "P$16_16") (pintype "no_connect"))
    )
    (net (code "119") (name "unconnected-(9-PadINT)") (class "Default")
      (node (ref "9") (pin "INT") (pinfunction "INT_INT") (pintype "bidirectional"))
    )
    (net (code "120") (name "unconnected-(9-PadINT{slash}TRIG)") (class "Default")
      (node (ref "9") (pin "INT/TRIG") (pinfunction "INT/TRIG_INT/TRIG") (pintype "bidirectional"))
    )
    (net (code "121") (name "unconnected-(9-PadMISO)") (class "Default")
      (node (ref "9") (pin "MISO") (pinfunction "MISO_MISO") (pintype "bidirectional"))
    )
    (net (code "122") (name "unconnected-(10-P$4-Pad4)") (class "Default")
      (node (ref "10") (pin "4") (pinfunction "P$4_4") (pintype "no_connect"))
    )
    (net (code "123") (name "unconnected-(10-P$9-Pad9)") (class "Default")
      (node (ref "10") (pin "9") (pinfunction "P$9_9") (pintype "no_connect"))
    )
    (net (code "124") (name "unconnected-(10-P$10-Pad10)") (class "Default")
      (node (ref "10") (pin "10") (pinfunction "P$10_10") (pintype "no_connect"))
    )
    (net (code "125") (name "unconnected-(10-P$14-Pad14)") (class "Default")
      (node (ref "10") (pin "14") (pinfunction "P$14_14") (pintype "no_connect"))
    )
    (net (code "126") (name "unconnected-(10-P$16-Pad16)") (class "Default")
      (node (ref "10") (pin "16") (pinfunction "P$16_16") (pintype "no_connect"))
    )
    (net (code "127") (name "unconnected-(10-PadINT)") (class "Default")
      (node (ref "10") (pin "INT") (pinfunction "INT_INT") (pintype "bidirectional"))
    )
    (net (code "128") (name "unconnected-(10-PadINT{slash}TRIG)") (class "Default")
      (node (ref "10") (pin "INT/TRIG") (pinfunction "INT/TRIG_INT/TRIG") (pintype "bidirectional"))
    )
    (net (code "129") (name "unconnected-(10-PadMISO)") (class "Default")
      (node (ref "10") (pin "MISO") (pinfunction "MISO_MISO") (pintype "bidirectional"))
    )
    (net (code "130") (name "unconnected-(11-P$4-Pad4)") (class "Default")
      (node (ref "11") (pin "4") (pinfunction "P$4_4") (pintype "no_connect"))
    )
    (net (code "131") (name "unconnected-(11-P$9-Pad9)") (class "Default")
      (node (ref "11") (pin "9") (pinfunction "P$9_9") (pintype "no_connect"))
    )
    (net (code "132") (name "unconnected-(11-P$10-Pad10)") (class "Default")
      (node (ref "11") (pin "10") (pinfunction "P$10_10") (pintype "no_connect"))
    )
    (net (code "133") (name "unconnected-(11-P$14-Pad14)") (class "Default")
      (node (ref "11") (pin "14") (pinfunction "P$14_14") (pintype "no_connect"))
    )
    (net (code "134") (name "unconnected-(11-P$16-Pad16)") (class "Default")
      (node (ref "11") (pin "16") (pinfunction "P$16_16") (pintype "no_connect"))
    )
    (net (code "135") (name "unconnected-(11-PadINT)") (class "Default")
      (node (ref "11") (pin "INT") (pinfunction "INT_INT") (pintype "bidirectional"))
    )
    (net (code "136") (name "unconnected-(11-PadINT{slash}TRIG)") (class "Default")
      (node (ref "11") (pin "INT/TRIG") (pinfunction "INT/TRIG_INT/TRIG") (pintype "bidirectional"))
    )
    (net (code "137") (name "unconnected-(11-PadMISO)") (class "Default")
      (node (ref "11") (pin "MISO") (pinfunction "MISO_MISO") (pintype "bidirectional"))
    )
    (net (code "138") (name "unconnected-(12-P$4-Pad4)") (class "Default")
      (node (ref "12") (pin "4") (pinfunction "P$4_4") (pintype "no_connect"))
    )
    (net (code "139") (name "unconnected-(12-P$9-Pad9)") (class "Default")
      (node (ref "12") (pin "9") (pinfunction "P$9_9") (pintype "no_connect"))
    )
    (net (code "140") (name "unconnected-(12-P$10-Pad10)") (class "Default")
      (node (ref "12") (pin "10") (pinfunction "P$10_10") (pintype "no_connect"))
    )
    (net (code "141") (name "unconnected-(12-P$14-Pad14)") (class "Default")
      (node (ref "12") (pin "14") (pinfunction "P$14_14") (pintype "no_connect"))
    )
    (net (code "142") (name "unconnected-(12-P$16-Pad16)") (class "Default")
      (node (ref "12") (pin "16") (pinfunction "P$16_16") (pintype "no_connect"))
    )
    (net (code "143") (name "unconnected-(12-PadINT)") (class "Default")
      (node (ref "12") (pin "INT") (pinfunction "INT_INT") (pintype "bidirectional"))
    )
    (net (code "144") (name "unconnected-(12-PadINT{slash}TRIG)") (class "Default")
      (node (ref "12") (pin "INT/TRIG") (pinfunction "INT/TRIG_INT/TRIG") (pintype "bidirectional"))
    )
    (net (code "145") (name "unconnected-(12-PadMISO)") (class "Default")
      (node (ref "12") (pin "MISO") (pinfunction "MISO_MISO") (pintype "bidirectional"))
    )
    (net (code "146") (name "unconnected-(13-P$4-Pad4)") (class "Default")
      (node (ref "13") (pin "4") (pinfunction "P$4_4") (pintype "no_connect"))
    )
    (net (code "147") (name "unconnected-(13-P$9-Pad9)") (class "Default")
      (node (ref "13") (pin "9") (pinfunction "P$9_9") (pintype "no_connect"))
    )
    (net (code "148") (name "unconnected-(13-P$10-Pad10)") (class "Default")
      (node (ref "13") (pin "10") (pinfunction "P$10_10") (pintype "no_connect"))
    )
    (net (code "149") (name "unconnected-(13-P$14-Pad14)") (class "Default")
      (node (ref "13") (pin "14") (pinfunction "P$14_14") (pintype "no_connect"))
    )
    (net (code "150") (name "unconnected-(13-P$16-Pad16)") (class "Default")
      (node (ref "13") (pin "16") (pinfunction "P$16_16") (pintype "no_connect"))
    )
    (net (code "151") (name "unconnected-(13-PadINT)") (class "Default")
      (node (ref "13") (pin "INT") (pinfunction "INT_INT") (pintype "bidirectional"))
    )
    (net (code "152") (name "unconnected-(13-PadINT{slash}TRIG)") (class "Default")
      (node (ref "13") (pin "INT/TRIG") (pinfunction "INT/TRIG_INT/TRIG") (pintype "bidirectional"))
    )
    (net (code "153") (name "unconnected-(13-PadMISO)") (class "Default")
      (node (ref "13") (pin "MISO") (pinfunction "MISO_MISO") (pintype "bidirectional"))
    )
    (net (code "154") (name "unconnected-(14-P$4-Pad4)") (class "Default")
      (node (ref "14") (pin "4") (pinfunction "P$4_4") (pintype "no_connect"))
    )
    (net (code "155") (name "unconnected-(14-P$9-Pad9)") (class "Default")
      (node (ref "14") (pin "9") (pinfunction "P$9_9") (pintype "no_connect"))
    )
    (net (code "156") (name "unconnected-(14-P$10-Pad10)") (class "Default")
      (node (ref "14") (pin "10") (pinfunction "P$10_10") (pintype "no_connect"))
    )
    (net (code "157") (name "unconnected-(14-P$14-Pad14)") (class "Default")
      (node (ref "14") (pin "14") (pinfunction "P$14_14") (pintype "no_connect"))
    )
    (net (code "158") (name "unconnected-(14-P$16-Pad16)") (class "Default")
      (node (ref "14") (pin "16") (pinfunction "P$16_16") (pintype "no_connect"))
    )
    (net (code "159") (name "unconnected-(14-PadINT)") (class "Default")
      (node (ref "14") (pin "INT") (pinfunction "INT_INT") (pintype "bidirectional"))
    )
    (net (code "160") (name "unconnected-(14-PadINT{slash}TRIG)") (class "Default")
      (node (ref "14") (pin "INT/TRIG") (pinfunction "INT/TRIG_INT/TRIG") (pintype "bidirectional"))
    )
    (net (code "161") (name "unconnected-(14-PadMISO)") (class "Default")
      (node (ref "14") (pin "MISO") (pinfunction "MISO_MISO") (pintype "bidirectional"))
    )
    (net (code "162") (name "unconnected-(15-P$4-Pad4)") (class "Default")
      (node (ref "15") (pin "4") (pinfunction "P$4_4") (pintype "no_connect"))
    )
    (net (code "163") (name "unconnected-(15-P$9-Pad9)") (class "Default")
      (node (ref "15") (pin "9") (pinfunction "P$9_9") (pintype "no_connect"))
    )
    (net (code "164") (name "unconnected-(15-P$10-Pad10)") (class "Default")
      (node (ref "15") (pin "10") (pinfunction "P$10_10") (pintype "no_connect"))
    )
    (net (code "165") (name "unconnected-(15-P$14-Pad14)") (class "Default")
      (node (ref "15") (pin "14") (pinfunction "P$14_14") (pintype "no_connect"))
    )
    (net (code "166") (name "unconnected-(15-P$16-Pad16)") (class "Default")
      (node (ref "15") (pin "16") (pinfunction "P$16_16") (pintype "no_connect"))
    )
    (net (code "167") (name "unconnected-(15-PadINT)") (class "Default")
      (node (ref "15") (pin "INT") (pinfunction "INT_INT") (pintype "bidirectional"))
    )
    (net (code "168") (name "unconnected-(15-PadINT{slash}TRIG)") (class "Default")
      (node (ref "15") (pin "INT/TRIG") (pinfunction "INT/TRIG_INT/TRIG") (pintype "bidirectional"))
    )
    (net (code "169") (name "unconnected-(15-PadMISO)") (class "Default")
      (node (ref "15") (pin "MISO") (pinfunction "MISO_MISO") (pintype "bidirectional"))
    )
    (net (code "170") (name "unconnected-(16-P$4-Pad4)") (class "Default")
      (node (ref "16") (pin "4") (pinfunction "P$4_4") (pintype "no_connect"))
    )
    (net (code "171") (name "unconnected-(16-P$9-Pad9)") (class "Default")
      (node (ref "16") (pin "9") (pinfunction "P$9_9") (pintype "no_connect"))
    )
    (net (code "172") (name "unconnected-(16-P$10-Pad10)") (class "Default")
      (node (ref "16") (pin "10") (pinfunction "P$10_10") (pintype "no_connect"))
    )
    (net (code "173") (name "unconnected-(16-P$14-Pad14)") (class "Default")
      (node (ref "16") (pin "14") (pinfunction "P$14_14") (pintype "no_connect"))
    )
    (net (code "174") (name "unconnected-(16-P$16-Pad16)") (class "Default")
      (node (ref "16") (pin "16") (pinfunction "P$16_16") (pintype "no_connect"))
    )
    (net (code "175") (name "unconnected-(16-PadINT)") (class "Default")
      (node (ref "16") (pin "INT") (pinfunction "INT_INT") (pintype "bidirectional"))
    )
    (net (code "176") (name "unconnected-(16-PadINT{slash}TRIG)") (class "Default")
      (node (ref "16") (pin "INT/TRIG") (pinfunction "INT/TRIG_INT/TRIG") (pintype "bidirectional"))
    )
    (net (code "177") (name "unconnected-(16-PadMISO)") (class "Default")
      (node (ref "16") (pin "MISO") (pinfunction "MISO_MISO") (pintype "bidirectional"))
    )
    (net (code "178") (name "unconnected-(17-P$4-Pad4)") (class "Default")
      (node (ref "17") (pin "4") (pinfunction "P$4_4") (pintype "no_connect"))
    )
    (net (code "179") (name "unconnected-(17-P$9-Pad9)") (class "Default")
      (node (ref "17") (pin "9") (pinfunction "P$9_9") (pintype "no_connect"))
    )
    (net (code "180") (name "unconnected-(17-P$10-Pad10)") (class "Default")
      (node (ref "17") (pin "10") (pinfunction "P$10_10") (pintype "no_connect"))
    )
    (net (code "181") (name "unconnected-(17-P$14-Pad14)") (class "Default")
      (node (ref "17") (pin "14") (pinfunction "P$14_14") (pintype "no_connect"))
    )
    (net (code "182") (name "unconnected-(17-P$16-Pad16)") (class "Default")
      (node (ref "17") (pin "16") (pinfunction "P$16_16") (pintype "no_connect"))
    )
    (net (code "183") (name "unconnected-(17-PadINT)") (class "Default")
      (node (ref "17") (pin "INT") (pinfunction "INT_INT") (pintype "bidirectional"))
    )
    (net (code "184") (name "unconnected-(17-PadINT{slash}TRIG)") (class "Default")
      (node (ref "17") (pin "INT/TRIG") (pinfunction "INT/TRIG_INT/TRIG") (pintype "bidirectional"))
    )
    (net (code "185") (name "unconnected-(17-PadMISO)") (class "Default")
      (node (ref "17") (pin "MISO") (pinfunction "MISO_MISO") (pintype "bidirectional"))
    )
    (net (code "186") (name "unconnected-(18-P$4-Pad4)") (class "Default")
      (node (ref "18") (pin "4") (pinfunction "P$4_4") (pintype "no_connect"))
    )
    (net (code "187") (name "unconnected-(18-P$9-Pad9)") (class "Default")
      (node (ref "18") (pin "9") (pinfunction "P$9_9") (pintype "no_connect"))
    )
    (net (code "188") (name "unconnected-(18-P$10-Pad10)") (class "Default")
      (node (ref "18") (pin "10") (pinfunction "P$10_10") (pintype "no_connect"))
    )
    (net (code "189") (name "unconnected-(18-P$14-Pad14)") (class "Default")
      (node (ref "18") (pin "14") (pinfunction "P$14_14") (pintype "no_connect"))
    )
    (net (code "190") (name "unconnected-(18-P$16-Pad16)") (class "Default")
      (node (ref "18") (pin "16") (pinfunction "P$16_16") (pintype "no_connect"))
    )
    (net (code "191") (name "unconnected-(18-PadINT)") (class "Default")
      (node (ref "18") (pin "INT") (pinfunction "INT_INT") (pintype "bidirectional"))
    )
    (net (code "192") (name "unconnected-(18-PadINT{slash}TRIG)") (class "Default")
      (node (ref "18") (pin "INT/TRIG") (pinfunction "INT/TRIG_INT/TRIG") (pintype "bidirectional"))
    )
    (net (code "193") (name "unconnected-(18-PadMISO)") (class "Default")
      (node (ref "18") (pin "MISO") (pinfunction "MISO_MISO") (pintype "bidirectional"))
    )
    (net (code "194") (name "unconnected-(19-P$4-Pad4)") (class "Default")
      (node (ref "19") (pin "4") (pinfunction "P$4_4") (pintype "no_connect"))
    )
    (net (code "195") (name "unconnected-(19-P$9-Pad9)") (class "Default")
      (node (ref "19") (pin "9") (pinfunction "P$9_9") (pintype "no_connect"))
    )
    (net (code "196") (name "unconnected-(19-P$10-Pad10)") (class "Default")
      (node (ref "19") (pin "10") (pinfunction "P$10_10") (pintype "no_connect"))
    )
    (net (code "197") (name "unconnected-(19-P$14-Pad14)") (class "Default")
      (node (ref "19") (pin "14") (pinfunction "P$14_14") (pintype "no_connect"))
    )
    (net (code "198") (name "unconnected-(19-P$16-Pad16)") (class "Default")
      (node (ref "19") (pin "16") (pinfunction "P$16_16") (pintype "no_connect"))
    )
    (net (code "199") (name "unconnected-(19-PadINT)") (class "Default")
      (node (ref "19") (pin "INT") (pinfunction "INT_INT") (pintype "bidirectional"))
    )
    (net (code "200") (name "unconnected-(19-PadINT{slash}TRIG)") (class "Default")
      (node (ref "19") (pin "INT/TRIG") (pinfunction "INT/TRIG_INT/TRIG") (pintype "bidirectional"))
    )
    (net (code "201") (name "unconnected-(19-PadMISO)") (class "Default")
      (node (ref "19") (pin "MISO") (pinfunction "MISO_MISO") (pintype "bidirectional"))
    )
    (net (code "202") (name "unconnected-(20-P$4-Pad4)") (class "Default")
      (node (ref "20") (pin "4") (pinfunction "P$4_4") (pintype "no_connect"))
    )
    (net (code "203") (name "unconnected-(20-P$9-Pad9)") (class "Default")
      (node (ref "20") (pin "9") (pinfunction "P$9_9") (pintype "no_connect"))
    )
    (net (code "204") (name "unconnected-(20-P$10-Pad10)") (class "Default")
      (node (ref "20") (pin "10") (pinfunction "P$10_10") (pintype "no_connect"))
    )
    (net (code "205") (name "unconnected-(20-P$14-Pad14)") (class "Default")
      (node (ref "20") (pin "14") (pinfunction "P$14_14") (pintype "no_connect"))
    )
    (net (code "206") (name "unconnected-(20-P$16-Pad16)") (class "Default")
      (node (ref "20") (pin "16") (pinfunction "P$16_16") (pintype "no_connect"))
    )
    (net (code "207") (name "unconnected-(20-PadINT)") (class "Default")
      (node (ref "20") (pin "INT") (pinfunction "INT_INT") (pintype "bidirectional"))
    )
    (net (code "208") (name "unconnected-(20-PadINT{slash}TRIG)") (class "Default")
      (node (ref "20") (pin "INT/TRIG") (pinfunction "INT/TRIG_INT/TRIG") (pintype "bidirectional"))
    )
    (net (code "209") (name "unconnected-(20-PadMISO)") (class "Default")
      (node (ref "20") (pin "MISO") (pinfunction "MISO_MISO") (pintype "bidirectional"))
    )
    (net (code "210") (name "unconnected-(21-P$4-Pad4)") (class "Default")
      (node (ref "21") (pin "4") (pinfunction "P$4_4") (pintype "no_connect"))
    )
    (net (code "211") (name "unconnected-(21-P$9-Pad9)") (class "Default")
      (node (ref "21") (pin "9") (pinfunction "P$9_9") (pintype "no_connect"))
    )
    (net (code "212") (name "unconnected-(21-P$10-Pad10)") (class "Default")
      (node (ref "21") (pin "10") (pinfunction "P$10_10") (pintype "no_connect"))
    )
    (net (code "213") (name "unconnected-(21-P$14-Pad14)") (class "Default")
      (node (ref "21") (pin "14") (pinfunction "P$14_14") (pintype "no_connect"))
    )
    (net (code "214") (name "unconnected-(21-P$16-Pad16)") (class "Default")
      (node (ref "21") (pin "16") (pinfunction "P$16_16") (pintype "no_connect"))
    )
    (net (code "215") (name "unconnected-(21-PadINT)") (class "Default")
      (node (ref "21") (pin "INT") (pinfunction "INT_INT") (pintype "bidirectional"))
    )
    (net (code "216") (name "unconnected-(21-PadINT{slash}TRIG)") (class "Default")
      (node (ref "21") (pin "INT/TRIG") (pinfunction "INT/TRIG_INT/TRIG") (pintype "bidirectional"))
    )
    (net (code "217") (name "unconnected-(21-PadMISO)") (class "Default")
      (node (ref "21") (pin "MISO") (pinfunction "MISO_MISO") (pintype "bidirectional"))
    )
    (net (code "218") (name "unconnected-(22-P$4-Pad4)") (class "Default")
      (node (ref "22") (pin "4") (pinfunction "P$4_4") (pintype "no_connect"))
    )
    (net (code "219") (name "unconnected-(22-P$9-Pad9)") (class "Default")
      (node (ref "22") (pin "9") (pinfunction "P$9_9") (pintype "no_connect"))
    )
    (net (code "220") (name "unconnected-(22-P$10-Pad10)") (class "Default")
      (node (ref "22") (pin "10") (pinfunction "P$10_10") (pintype "no_connect"))
    )
    (net (code "221") (name "unconnected-(22-P$14-Pad14)") (class "Default")
      (node (ref "22") (pin "14") (pinfunction "P$14_14") (pintype "no_connect"))
    )
    (net (code "222") (name "unconnected-(22-P$16-Pad16)") (class "Default")
      (node (ref "22") (pin "16") (pinfunction "P$16_16") (pintype "no_connect"))
    )
    (net (code "223") (name "unconnected-(22-PadINT)") (class "Default")
      (node (ref "22") (pin "INT") (pinfunction "INT_INT") (pintype "bidirectional"))
    )
    (net (code "224") (name "unconnected-(22-PadINT{slash}TRIG)") (class "Default")
      (node (ref "22") (pin "INT/TRIG") (pinfunction "INT/TRIG_INT/TRIG") (pintype "bidirectional"))
    )
    (net (code "225") (name "unconnected-(22-PadMISO)") (class "Default")
      (node (ref "22") (pin "MISO") (pinfunction "MISO_MISO") (pintype "bidirectional"))
    )
    (net (code "226") (name "unconnected-(23-P$4-Pad4)") (class "Default")
      (node (ref "23") (pin "4") (pinfunction "P$4_4") (pintype "no_connect"))
    )
    (net (code "227") (name "unconnected-(23-P$9-Pad9)") (class "Default")
      (node (ref "23") (pin "9") (pinfunction "P$9_9") (pintype "no_connect"))
    )
    (net (code "228") (name "unconnected-(23-P$10-Pad10)") (class "Default")
      (node (ref "23") (pin "10") (pinfunction "P$10_10") (pintype "no_connect"))
    )
    (net (code "229") (name "unconnected-(23-P$14-Pad14)") (class "Default")
      (node (ref "23") (pin "14") (pinfunction "P$14_14") (pintype "no_connect"))
    )
    (net (code "230") (name "unconnected-(23-P$16-Pad16)") (class "Default")
      (node (ref "23") (pin "16") (pinfunction "P$16_16") (pintype "no_connect"))
    )
    (net (code "231") (name "unconnected-(23-PadINT)") (class "Default")
      (node (ref "23") (pin "INT") (pinfunction "INT_INT") (pintype "bidirectional"))
    )
    (net (code "232") (name "unconnected-(23-PadINT{slash}TRIG)") (class "Default")
      (node (ref "23") (pin "INT/TRIG") (pinfunction "INT/TRIG_INT/TRIG") (pintype "bidirectional"))
    )
    (net (code "233") (name "unconnected-(23-PadMISO)") (class "Default")
      (node (ref "23") (pin "MISO") (pinfunction "MISO_MISO") (pintype "bidirectional"))
    )
    (net (code "234") (name "unconnected-(24-P$4-Pad4)") (class "Default")
      (node (ref "24") (pin "4") (pinfunction "P$4_4") (pintype "no_connect"))
    )
    (net (code "235") (name "unconnected-(24-P$9-Pad9)") (class "Default")
      (node (ref "24") (pin "9") (pinfunction "P$9_9") (pintype "no_connect"))
    )
    (net (code "236") (name "unconnected-(24-P$10-Pad10)") (class "Default")
      (node (ref "24") (pin "10") (pinfunction "P$10_10") (pintype "no_connect"))
    )
    (net (code "237") (name "unconnected-(24-P$14-Pad14)") (class "Default")
      (node (ref "24") (pin "14") (pinfunction "P$14_14") (pintype "no_connect"))
    )
    (net (code "238") (name "unconnected-(24-P$16-Pad16)") (class "Default")
      (node (ref "24") (pin "16") (pinfunction "P$16_16") (pintype "no_connect"))
    )
    (net (code "239") (name "unconnected-(24-PadINT)") (class "Default")
      (node (ref "24") (pin "INT") (pinfunction "INT_INT") (pintype "bidirectional"))
    )
    (net (code "240") (name "unconnected-(24-PadINT{slash}TRIG)") (class "Default")
      (node (ref "24") (pin "INT/TRIG") (pinfunction "INT/TRIG_INT/TRIG") (pintype "bidirectional"))
    )
    (net (code "241") (name "unconnected-(24-PadMISO)") (class "Default")
      (node (ref "24") (pin "MISO") (pinfunction "MISO_MISO") (pintype "bidirectional"))
    )
    (net (code "242") (name "unconnected-(25-P$4-Pad4)") (class "Default")
      (node (ref "25") (pin "4") (pinfunction "P$4_4") (pintype "no_connect"))
    )
    (net (code "243") (name "unconnected-(25-P$9-Pad9)") (class "Default")
      (node (ref "25") (pin "9") (pinfunction "P$9_9") (pintype "no_connect"))
    )
    (net (code "244") (name "unconnected-(25-P$10-Pad10)") (class "Default")
      (node (ref "25") (pin "10") (pinfunction "P$10_10") (pintype "no_connect"))
    )
    (net (code "245") (name "unconnected-(25-P$14-Pad14)") (class "Default")
      (node (ref "25") (pin "14") (pinfunction "P$14_14") (pintype "no_connect"))
    )
    (net (code "246") (name "unconnected-(25-P$16-Pad16)") (class "Default")
      (node (ref "25") (pin "16") (pinfunction "P$16_16") (pintype "no_connect"))
    )
    (net (code "247") (name "unconnected-(25-PadINT)") (class "Default")
      (node (ref "25") (pin "INT") (pinfunction "INT_INT") (pintype "bidirectional"))
    )
    (net (code "248") (name "unconnected-(25-PadINT{slash}TRIG)") (class "Default")
      (node (ref "25") (pin "INT/TRIG") (pinfunction "INT/TRIG_INT/TRIG") (pintype "bidirectional"))
    )
    (net (code "249") (name "unconnected-(25-PadMISO)") (class "Default")
      (node (ref "25") (pin "MISO") (pinfunction "MISO_MISO") (pintype "bidirectional"))
    )
    (net (code "250") (name "unconnected-(26-P$4-Pad4)") (class "Default")
      (node (ref "26") (pin "4") (pinfunction "P$4_4") (pintype "no_connect"))
    )
    (net (code "251") (name "unconnected-(26-P$9-Pad9)") (class "Default")
      (node (ref "26") (pin "9") (pinfunction "P$9_9") (pintype "no_connect"))
    )
    (net (code "252") (name "unconnected-(26-P$10-Pad10)") (class "Default")
      (node (ref "26") (pin "10") (pinfunction "P$10_10") (pintype "no_connect"))
    )
    (net (code "253") (name "unconnected-(26-P$14-Pad14)") (class "Default")
      (node (ref "26") (pin "14") (pinfunction "P$14_14") (pintype "no_connect"))
    )
    (net (code "254") (name "unconnected-(26-P$16-Pad16)") (class "Default")
      (node (ref "26") (pin "16") (pinfunction "P$16_16") (pintype "no_connect"))
    )
    (net (code "255") (name "unconnected-(26-PadINT)") (class "Default")
      (node (ref "26") (pin "INT") (pinfunction "INT_INT") (pintype "bidirectional"))
    )
    (net (code "256") (name "unconnected-(26-PadINT{slash}TRIG)") (class "Default")
      (node (ref "26") (pin "INT/TRIG") (pinfunction "INT/TRIG_INT/TRIG") (pintype "bidirectional"))
    )
    (net (code "257") (name "unconnected-(26-PadMISO)") (class "Default")
      (node (ref "26") (pin "MISO") (pinfunction "MISO_MISO") (pintype "bidirectional"))
    )
    (net (code "258") (name "unconnected-(27-P$4-Pad4)") (class "Default")
      (node (ref "27") (pin "4") (pinfunction "P$4_4") (pintype "no_connect"))
    )
    (net (code "259") (name "unconnected-(27-P$9-Pad9)") (class "Default")
      (node (ref "27") (pin "9") (pinfunction "P$9_9") (pintype "no_connect"))
    )
    (net (code "260") (name "unconnected-(27-P$10-Pad10)") (class "Default")
      (node (ref "27") (pin "10") (pinfunction "P$10_10") (pintype "no_connect"))
    )
    (net (code "261") (name "unconnected-(27-P$14-Pad14)") (class "Default")
      (node (ref "27") (pin "14") (pinfunction "P$14_14") (pintype "no_connect"))
    )
    (net (code "262") (name "unconnected-(27-P$16-Pad16)") (class "Default")
      (node (ref "27") (pin "16") (pinfunction "P$16_16") (pintype "no_connect"))
    )
    (net (code "263") (name "unconnected-(27-PadINT)") (class "Default")
      (node (ref "27") (pin "INT") (pinfunction "INT_INT") (pintype "bidirectional"))
    )
    (net (code "264") (name "unconnected-(27-PadINT{slash}TRIG)") (class "Default")
      (node (ref "27") (pin "INT/TRIG") (pinfunction "INT/TRIG_INT/TRIG") (pintype "bidirectional"))
    )
    (net (code "265") (name "unconnected-(27-PadMISO)") (class "Default")
      (node (ref "27") (pin "MISO") (pinfunction "MISO_MISO") (pintype "bidirectional"))
    )
    (net (code "266") (name "unconnected-(28-P$4-Pad4)") (class "Default")
      (node (ref "28") (pin "4") (pinfunction "P$4_4") (pintype "no_connect"))
    )
    (net (code "267") (name "unconnected-(28-P$9-Pad9)") (class "Default")
      (node (ref "28") (pin "9") (pinfunction "P$9_9") (pintype "no_connect"))
    )
    (net (code "268") (name "unconnected-(28-P$10-Pad10)") (class "Default")
      (node (ref "28") (pin "10") (pinfunction "P$10_10") (pintype "no_connect"))
    )
    (net (code "269") (name "unconnected-(28-P$14-Pad14)") (class "Default")
      (node (ref "28") (pin "14") (pinfunction "P$14_14") (pintype "no_connect"))
    )
    (net (code "270") (name "unconnected-(28-P$16-Pad16)") (class "Default")
      (node (ref "28") (pin "16") (pinfunction "P$16_16") (pintype "no_connect"))
    )
    (net (code "271") (name "unconnected-(28-PadINT)") (class "Default")
      (node (ref "28") (pin "INT") (pinfunction "INT_INT") (pintype "bidirectional"))
    )
    (net (code "272") (name "unconnected-(28-PadINT{slash}TRIG)") (class "Default")
      (node (ref "28") (pin "INT/TRIG") (pinfunction "INT/TRIG_INT/TRIG") (pintype "bidirectional"))
    )
    (net (code "273") (name "unconnected-(28-PadMISO)") (class "Default")
      (node (ref "28") (pin "MISO") (pinfunction "MISO_MISO") (pintype "bidirectional"))
    )
    (net (code "274") (name "unconnected-(29-P$4-Pad4)") (class "Default")
      (node (ref "29") (pin "4") (pinfunction "P$4_4") (pintype "no_connect"))
    )
    (net (code "275") (name "unconnected-(29-P$9-Pad9)") (class "Default")
      (node (ref "29") (pin "9") (pinfunction "P$9_9") (pintype "no_connect"))
    )
    (net (code "276") (name "unconnected-(29-P$10-Pad10)") (class "Default")
      (node (ref "29") (pin "10") (pinfunction "P$10_10") (pintype "no_connect"))
    )
    (net (code "277") (name "unconnected-(29-P$14-Pad14)") (class "Default")
      (node (ref "29") (pin "14") (pinfunction "P$14_14") (pintype "no_connect"))
    )
    (net (code "278") (name "unconnected-(29-P$16-Pad16)") (class "Default")
      (node (ref "29") (pin "16") (pinfunction "P$16_16") (pintype "no_connect"))
    )
    (net (code "279") (name "unconnected-(29-PadINT)") (class "Default")
      (node (ref "29") (pin "INT") (pinfunction "INT_INT") (pintype "bidirectional"))
    )
    (net (code "280") (name "unconnected-(29-PadINT{slash}TRIG)") (class "Default")
      (node (ref "29") (pin "INT/TRIG") (pinfunction "INT/TRIG_INT/TRIG") (pintype "bidirectional"))
    )
    (net (code "281") (name "unconnected-(29-PadMISO)") (class "Default")
      (node (ref "29") (pin "MISO") (pinfunction "MISO_MISO") (pintype "bidirectional"))
    )
    (net (code "282") (name "unconnected-(30-P$4-Pad4)") (class "Default")
      (node (ref "30") (pin "4") (pinfunction "P$4_4") (pintype "no_connect"))
    )
    (net (code "283") (name "unconnected-(30-P$9-Pad9)") (class "Default")
      (node (ref "30") (pin "9") (pinfunction "P$9_9") (pintype "no_connect"))
    )
    (net (code "284") (name "unconnected-(30-P$10-Pad10)") (class "Default")
      (node (ref "30") (pin "10") (pinfunction "P$10_10") (pintype "no_connect"))
    )
    (net (code "285") (name "unconnected-(30-P$14-Pad14)") (class "Default")
      (node (ref "30") (pin "14") (pinfunction "P$14_14") (pintype "no_connect"))
    )
    (net (code "286") (name "unconnected-(30-P$16-Pad16)") (class "Default")
      (node (ref "30") (pin "16") (pinfunction "P$16_16") (pintype "no_connect"))
    )
    (net (code "287") (name "unconnected-(30-PadINT)") (class "Default")
      (node (ref "30") (pin "INT") (pinfunction "INT_INT") (pintype "bidirectional"))
    )
    (net (code "288") (name "unconnected-(30-PadINT{slash}TRIG)") (class "Default")
      (node (ref "30") (pin "INT/TRIG") (pinfunction "INT/TRIG_INT/TRIG") (pintype "bidirectional"))
    )
    (net (code "289") (name "unconnected-(30-PadMISO)") (class "Default")
      (node (ref "30") (pin "MISO") (pinfunction "MISO_MISO") (pintype "bidirectional"))
    )
    (net (code "290") (name "unconnected-(31-P$4-Pad4)") (class "Default")
      (node (ref "31") (pin "4") (pinfunction "P$4_4") (pintype "no_connect"))
    )
    (net (code "291") (name "unconnected-(31-P$9-Pad9)") (class "Default")
      (node (ref "31") (pin "9") (pinfunction "P$9_9") (pintype "no_connect"))
    )
    (net (code "292") (name "unconnected-(31-P$10-Pad10)") (class "Default")
      (node (ref "31") (pin "10") (pinfunction "P$10_10") (pintype "no_connect"))
    )
    (net (code "293") (name "unconnected-(31-P$14-Pad14)") (class "Default")
      (node (ref "31") (pin "14") (pinfunction "P$14_14") (pintype "no_connect"))
    )
    (net (code "294") (name "unconnected-(31-P$16-Pad16)") (class "Default")
      (node (ref "31") (pin "16") (pinfunction "P$16_16") (pintype "no_connect"))
    )
    (net (code "295") (name "unconnected-(31-PadINT)") (class "Default")
      (node (ref "31") (pin "INT") (pinfunction "INT_INT") (pintype "bidirectional"))
    )
    (net (code "296") (name "unconnected-(31-PadINT{slash}TRIG)") (class "Default")
      (node (ref "31") (pin "INT/TRIG") (pinfunction "INT/TRIG_INT/TRIG") (pintype "bidirectional"))
    )
    (net (code "297") (name "unconnected-(31-PadMISO)") (class "Default")
      (node (ref "31") (pin "MISO") (pinfunction "MISO_MISO") (pintype "bidirectional"))
    )
    (net (code "298") (name "unconnected-(32-P$4-Pad4)") (class "Default")
      (node (ref "32") (pin "4") (pinfunction "P$4_4") (pintype "no_connect"))
    )
    (net (code "299") (name "unconnected-(32-P$9-Pad9)") (class "Default")
      (node (ref "32") (pin "9") (pinfunction "P$9_9") (pintype "no_connect"))
    )
    (net (code "300") (name "unconnected-(32-P$10-Pad10)") (class "Default")
      (node (ref "32") (pin "10") (pinfunction "P$10_10") (pintype "no_connect"))
    )
    (net (code "301") (name "unconnected-(32-P$14-Pad14)") (class "Default")
      (node (ref "32") (pin "14") (pinfunction "P$14_14") (pintype "no_connect"))
    )
    (net (code "302") (name "unconnected-(32-P$16-Pad16)") (class "Default")
      (node (ref "32") (pin "16") (pinfunction "P$16_16") (pintype "no_connect"))
    )
    (net (code "303") (name "unconnected-(32-PadINT)") (class "Default")
      (node (ref "32") (pin "INT") (pinfunction "INT_INT") (pintype "bidirectional"))
    )
    (net (code "304") (name "unconnected-(32-PadINT{slash}TRIG)") (class "Default")
      (node (ref "32") (pin "INT/TRIG") (pinfunction "INT/TRIG_INT/TRIG") (pintype "bidirectional"))
    )
    (net (code "305") (name "unconnected-(32-PadMISO)") (class "Default")
      (node (ref "32") (pin "MISO") (pinfunction "MISO_MISO") (pintype "bidirectional"))
    )
    (net (code "306") (name "unconnected-(33-P$4-Pad4)") (class "Default")
      (node (ref "33") (pin "4") (pinfunction "P$4_4") (pintype "no_connect"))
    )
    (net (code "307") (name "unconnected-(33-P$9-Pad9)") (class "Default")
      (node (ref "33") (pin "9") (pinfunction "P$9_9") (pintype "no_connect"))
    )
    (net (code "308") (name "unconnected-(33-P$10-Pad10)") (class "Default")
      (node (ref "33") (pin "10") (pinfunction "P$10_10") (pintype "no_connect"))
    )
    (net (code "309") (name "unconnected-(33-P$14-Pad14)") (class "Default")
      (node (ref "33") (pin "14") (pinfunction "P$14_14") (pintype "no_connect"))
    )
    (net (code "310") (name "unconnected-(33-P$16-Pad16)") (class "Default")
      (node (ref "33") (pin "16") (pinfunction "P$16_16") (pintype "no_connect"))
    )
    (net (code "311") (name "unconnected-(33-PadINT)") (class "Default")
      (node (ref "33") (pin "INT") (pinfunction "INT_INT") (pintype "bidirectional"))
    )
    (net (code "312") (name "unconnected-(33-PadINT{slash}TRIG)") (class "Default")
      (node (ref "33") (pin "INT/TRIG") (pinfunction "INT/TRIG_INT/TRIG") (pintype "bidirectional"))
    )
    (net (code "313") (name "unconnected-(33-PadMISO)") (class "Default")
      (node (ref "33") (pin "MISO") (pinfunction "MISO_MISO") (pintype "bidirectional"))
    )
    (net (code "314") (name "unconnected-(34-P$4-Pad4)") (class "Default")
      (node (ref "34") (pin "4") (pinfunction "P$4_4") (pintype "no_connect"))
    )
    (net (code "315") (name "unconnected-(34-P$9-Pad9)") (class "Default")
      (node (ref "34") (pin "9") (pinfunction "P$9_9") (pintype "no_connect"))
    )
    (net (code "316") (name "unconnected-(34-P$10-Pad10)") (class "Default")
      (node (ref "34") (pin "10") (pinfunction "P$10_10") (pintype "no_connect"))
    )
    (net (code "317") (name "unconnected-(34-P$14-Pad14)") (class "Default")
      (node (ref "34") (pin "14") (pinfunction "P$14_14") (pintype "no_connect"))
    )
    (net (code "318") (name "unconnected-(34-P$16-Pad16)") (class "Default")
      (node (ref "34") (pin "16") (pinfunction "P$16_16") (pintype "no_connect"))
    )
    (net (code "319") (name "unconnected-(34-PadINT)") (class "Default")
      (node (ref "34") (pin "INT") (pinfunction "INT_INT") (pintype "bidirectional"))
    )
    (net (code "320") (name "unconnected-(34-PadINT{slash}TRIG)") (class "Default")
      (node (ref "34") (pin "INT/TRIG") (pinfunction "INT/TRIG_INT/TRIG") (pintype "bidirectional"))
    )
    (net (code "321") (name "unconnected-(34-PadMISO)") (class "Default")
      (node (ref "34") (pin "MISO") (pinfunction "MISO_MISO") (pintype "bidirectional"))
    )
    (net (code "322") (name "unconnected-(35-P$4-Pad4)") (class "Default")
      (node (ref "35") (pin "4") (pinfunction "P$4_4") (pintype "no_connect"))
    )
    (net (code "323") (name "unconnected-(35-P$9-Pad9)") (class "Default")
      (node (ref "35") (pin "9") (pinfunction "P$9_9") (pintype "no_connect"))
    )
    (net (code "324") (name "unconnected-(35-P$10-Pad10)") (class "Default")
      (node (ref "35") (pin "10") (pinfunction "P$10_10") (pintype "no_connect"))
    )
    (net (code "325") (name "unconnected-(35-P$14-Pad14)") (class "Default")
      (node (ref "35") (pin "14") (pinfunction "P$14_14") (pintype "no_connect"))
    )
    (net (code "326") (name "unconnected-(35-P$16-Pad16)") (class "Default")
      (node (ref "35") (pin "16") (pinfunction "P$16_16") (pintype "no_connect"))
    )
    (net (code "327") (name "unconnected-(35-PadINT)") (class "Default")
      (node (ref "35") (pin "INT") (pinfunction "INT_INT") (pintype "bidirectional"))
    )
    (net (code "328") (name "unconnected-(35-PadINT{slash}TRIG)") (class "Default")
      (node (ref "35") (pin "INT/TRIG") (pinfunction "INT/TRIG_INT/TRIG") (pintype "bidirectional"))
    )
    (net (code "329") (name "unconnected-(35-PadMISO)") (class "Default")
      (node (ref "35") (pin "MISO") (pinfunction "MISO_MISO") (pintype "bidirectional"))
    )
    (net (code "330") (name "unconnected-(36-P$4-Pad4)") (class "Default")
      (node (ref "36") (pin "4") (pinfunction "P$4_4") (pintype "no_connect"))
    )
    (net (code "331") (name "unconnected-(36-P$9-Pad9)") (class "Default")
      (node (ref "36") (pin "9") (pinfunction "P$9_9") (pintype "no_connect"))
    )
    (net (code "332") (name "unconnected-(36-P$10-Pad10)") (class "Default")
      (node (ref "36") (pin "10") (pinfunction "P$10_10") (pintype "no_connect"))
    )
    (net (code "333") (name "unconnected-(36-P$14-Pad14)") (class "Default")
      (node (ref "36") (pin "14") (pinfunction "P$14_14") (pintype "no_connect"))
    )
    (net (code "334") (name "unconnected-(36-P$16-Pad16)") (class "Default")
      (node (ref "36") (pin "16") (pinfunction "P$16_16") (pintype "no_connect"))
    )
    (net (code "335") (name "unconnected-(36-PadINT)") (class "Default")
      (node (ref "36") (pin "INT") (pinfunction "INT_INT") (pintype "bidirectional"))
    )
    (net (code "336") (name "unconnected-(36-PadINT{slash}TRIG)") (class "Default")
      (node (ref "36") (pin "INT/TRIG") (pinfunction "INT/TRIG_INT/TRIG") (pintype "bidirectional"))
    )
    (net (code "337") (name "unconnected-(36-PadMISO)") (class "Default")
      (node (ref "36") (pin "MISO") (pinfunction "MISO_MISO") (pintype "bidirectional"))
    )
    (net (code "338") (name "unconnected-(37-P$4-Pad4)") (class "Default")
      (node (ref "37") (pin "4") (pinfunction "P$4_4") (pintype "no_connect"))
    )
    (net (code "339") (name "unconnected-(37-P$9-Pad9)") (class "Default")
      (node (ref "37") (pin "9") (pinfunction "P$9_9") (pintype "no_connect"))
    )
    (net (code "340") (name "unconnected-(37-P$10-Pad10)") (class "Default")
      (node (ref "37") (pin "10") (pinfunction "P$10_10") (pintype "no_connect"))
    )
    (net (code "341") (name "unconnected-(37-P$14-Pad14)") (class "Default")
      (node (ref "37") (pin "14") (pinfunction "P$14_14") (pintype "no_connect"))
    )
    (net (code "342") (name "unconnected-(37-P$16-Pad16)") (class "Default")
      (node (ref "37") (pin "16") (pinfunction "P$16_16") (pintype "no_connect"))
    )
    (net (code "343") (name "unconnected-(37-PadINT)") (class "Default")
      (node (ref "37") (pin "INT") (pinfunction "INT_INT") (pintype "bidirectional"))
    )
    (net (code "344") (name "unconnected-(37-PadINT{slash}TRIG)") (class "Default")
      (node (ref "37") (pin "INT/TRIG") (pinfunction "INT/TRIG_INT/TRIG") (pintype "bidirectional"))
    )
    (net (code "345") (name "unconnected-(37-PadMISO)") (class "Default")
      (node (ref "37") (pin "MISO") (pinfunction "MISO_MISO") (pintype "bidirectional"))
    )
    (net (code "346") (name "unconnected-(38-P$4-Pad4)") (class "Default")
      (node (ref "38") (pin "4") (pinfunction "P$4_4") (pintype "no_connect"))
    )
    (net (code "347") (name "unconnected-(38-P$9-Pad9)") (class "Default")
      (node (ref "38") (pin "9") (pinfunction "P$9_9") (pintype "no_connect"))
    )
    (net (code "348") (name "unconnected-(38-P$10-Pad10)") (class "Default")
      (node (ref "38") (pin "10") (pinfunction "P$10_10") (pintype "no_connect"))
    )
    (net (code "349") (name "unconnected-(38-P$14-Pad14)") (class "Default")
      (node (ref "38") (pin "14") (pinfunction "P$14_14") (pintype "no_connect"))
    )
    (net (code "350") (name "unconnected-(38-P$16-Pad16)") (class "Default")
      (node (ref "38") (pin "16") (pinfunction "P$16_16") (pintype "no_connect"))
    )
    (net (code "351") (name "unconnected-(38-PadINT)") (class "Default")
      (node (ref "38") (pin "INT") (pinfunction "INT_INT") (pintype "bidirectional"))
    )
    (net (code "352") (name "unconnected-(38-PadINT{slash}TRIG)") (class "Default")
      (node (ref "38") (pin "INT/TRIG") (pinfunction "INT/TRIG_INT/TRIG") (pintype "bidirectional"))
    )
    (net (code "353") (name "unconnected-(38-PadMISO)") (class "Default")
      (node (ref "38") (pin "MISO") (pinfunction "MISO_MISO") (pintype "bidirectional"))
    )
    (net (code "354") (name "unconnected-(39-P$4-Pad4)") (class "Default")
      (node (ref "39") (pin "4") (pinfunction "P$4_4") (pintype "no_connect"))
    )
    (net (code "355") (name "unconnected-(39-P$9-Pad9)") (class "Default")
      (node (ref "39") (pin "9") (pinfunction "P$9_9") (pintype "no_connect"))
    )
    (net (code "356") (name "unconnected-(39-P$10-Pad10)") (class "Default")
      (node (ref "39") (pin "10") (pinfunction "P$10_10") (pintype "no_connect"))
    )
    (net (code "357") (name "unconnected-(39-P$14-Pad14)") (class "Default")
      (node (ref "39") (pin "14") (pinfunction "P$14_14") (pintype "no_connect"))
    )
    (net (code "358") (name "unconnected-(39-P$16-Pad16)") (class "Default")
      (node (ref "39") (pin "16") (pinfunction "P$16_16") (pintype "no_connect"))
    )
    (net (code "359") (name "unconnected-(39-PadINT)") (class "Default")
      (node (ref "39") (pin "INT") (pinfunction "INT_INT") (pintype "bidirectional"))
    )
    (net (code "360") (name "unconnected-(39-PadINT{slash}TRIG)") (class "Default")
      (node (ref "39") (pin "INT/TRIG") (pinfunction "INT/TRIG_INT/TRIG") (pintype "bidirectional"))
    )
    (net (code "361") (name "unconnected-(39-PadMISO)") (class "Default")
      (node (ref "39") (pin "MISO") (pinfunction "MISO_MISO") (pintype "bidirectional"))
    )
    (net (code "362") (name "unconnected-(40-P$4-Pad4)") (class "Default")
      (node (ref "40") (pin "4") (pinfunction "P$4_4") (pintype "no_connect"))
    )
    (net (code "363") (name "unconnected-(40-P$9-Pad9)") (class "Default")
      (node (ref "40") (pin "9") (pinfunction "P$9_9") (pintype "no_connect"))
    )
    (net (code "364") (name "unconnected-(40-P$10-Pad10)") (class "Default")
      (node (ref "40") (pin "10") (pinfunction "P$10_10") (pintype "no_connect"))
    )
    (net (code "365") (name "unconnected-(40-P$14-Pad14)") (class "Default")
      (node (ref "40") (pin "14") (pinfunction "P$14_14") (pintype "no_connect"))
    )
    (net (code "366") (name "unconnected-(40-P$16-Pad16)") (class "Default")
      (node (ref "40") (pin "16") (pinfunction "P$16_16") (pintype "no_connect"))
    )
    (net (code "367") (name "unconnected-(40-PadINT)") (class "Default")
      (node (ref "40") (pin "INT") (pinfunction "INT_INT") (pintype "bidirectional"))
    )
    (net (code "368") (name "unconnected-(40-PadINT{slash}TRIG)") (class "Default")
      (node (ref "40") (pin "INT/TRIG") (pinfunction "INT/TRIG_INT/TRIG") (pintype "bidirectional"))
    )
    (net (code "369") (name "unconnected-(40-PadMISO)") (class "Default")
      (node (ref "40") (pin "MISO") (pinfunction "MISO_MISO") (pintype "bidirectional"))
    )
    (net (code "370") (name "unconnected-(41-P$4-Pad4)") (class "Default")
      (node (ref "41") (pin "4") (pinfunction "P$4_4") (pintype "no_connect"))
    )
    (net (code "371") (name "unconnected-(41-P$9-Pad9)") (class "Default")
      (node (ref "41") (pin "9") (pinfunction "P$9_9") (pintype "no_connect"))
    )
    (net (code "372") (name "unconnected-(41-P$10-Pad10)") (class "Default")
      (node (ref "41") (pin "10") (pinfunction "P$10_10") (pintype "no_connect"))
    )
    (net (code "373") (name "unconnected-(41-P$14-Pad14)") (class "Default")
      (node (ref "41") (pin "14") (pinfunction "P$14_14") (pintype "no_connect"))
    )
    (net (code "374") (name "unconnected-(41-P$16-Pad16)") (class "Default")
      (node (ref "41") (pin "16") (pinfunction "P$16_16") (pintype "no_connect"))
    )
    (net (code "375") (name "unconnected-(41-PadINT)") (class "Default")
      (node (ref "41") (pin "INT") (pinfunction "INT_INT") (pintype "bidirectional"))
    )
    (net (code "376") (name "unconnected-(41-PadINT{slash}TRIG)") (class "Default")
      (node (ref "41") (pin "INT/TRIG") (pinfunction "INT/TRIG_INT/TRIG") (pintype "bidirectional"))
    )
    (net (code "377") (name "unconnected-(41-PadMISO)") (class "Default")
      (node (ref "41") (pin "MISO") (pinfunction "MISO_MISO") (pintype "bidirectional"))
    )
    (net (code "378") (name "unconnected-(42-P$4-Pad4)") (class "Default")
      (node (ref "42") (pin "4") (pinfunction "P$4_4") (pintype "no_connect"))
    )
    (net (code "379") (name "unconnected-(42-P$9-Pad9)") (class "Default")
      (node (ref "42") (pin "9") (pinfunction "P$9_9") (pintype "no_connect"))
    )
    (net (code "380") (name "unconnected-(42-P$10-Pad10)") (class "Default")
      (node (ref "42") (pin "10") (pinfunction "P$10_10") (pintype "no_connect"))
    )
    (net (code "381") (name "unconnected-(42-P$14-Pad14)") (class "Default")
      (node (ref "42") (pin "14") (pinfunction "P$14_14") (pintype "no_connect"))
    )
    (net (code "382") (name "unconnected-(42-P$16-Pad16)") (class "Default")
      (node (ref "42") (pin "16") (pinfunction "P$16_16") (pintype "no_connect"))
    )
    (net (code "383") (name "unconnected-(42-PadINT)") (class "Default")
      (node (ref "42") (pin "INT") (pinfunction "INT_INT") (pintype "bidirectional"))
    )
    (net (code "384") (name "unconnected-(42-PadINT{slash}TRIG)") (class "Default")
      (node (ref "42") (pin "INT/TRIG") (pinfunction "INT/TRIG_INT/TRIG") (pintype "bidirectional"))
    )
    (net (code "385") (name "unconnected-(42-PadMISO)") (class "Default")
      (node (ref "42") (pin "MISO") (pinfunction "MISO_MISO") (pintype "bidirectional"))
    )
    (net (code "386") (name "unconnected-(43-P$4-Pad4)") (class "Default")
      (node (ref "43") (pin "4") (pinfunction "P$4_4") (pintype "no_connect"))
    )
    (net (code "387") (name "unconnected-(43-P$9-Pad9)") (class "Default")
      (node (ref "43") (pin "9") (pinfunction "P$9_9") (pintype "no_connect"))
    )
    (net (code "388") (name "unconnected-(43-P$10-Pad10)") (class "Default")
      (node (ref "43") (pin "10") (pinfunction "P$10_10") (pintype "no_connect"))
    )
    (net (code "389") (name "unconnected-(43-P$14-Pad14)") (class "Default")
      (node (ref "43") (pin "14") (pinfunction "P$14_14") (pintype "no_connect"))
    )
    (net (code "390") (name "unconnected-(43-P$16-Pad16)") (class "Default")
      (node (ref "43") (pin "16") (pinfunction "P$16_16") (pintype "no_connect"))
    )
    (net (code "391") (name "unconnected-(43-PadINT)") (class "Default")
      (node (ref "43") (pin "INT") (pinfunction "INT_INT") (pintype "bidirectional"))
    )
    (net (code "392") (name "unconnected-(43-PadINT{slash}TRIG)") (class "Default")
      (node (ref "43") (pin "INT/TRIG") (pinfunction "INT/TRIG_INT/TRIG") (pintype "bidirectional"))
    )
    (net (code "393") (name "unconnected-(43-PadMISO)") (class "Default")
      (node (ref "43") (pin "MISO") (pinfunction "MISO_MISO") (pintype "bidirectional"))
    )
    (net (code "394") (name "unconnected-(44-P$4-Pad4)") (class "Default")
      (node (ref "44") (pin "4") (pinfunction "P$4_4") (pintype "no_connect"))
    )
    (net (code "395") (name "unconnected-(44-P$9-Pad9)") (class "Default")
      (node (ref "44") (pin "9") (pinfunction "P$9_9") (pintype "no_connect"))
    )
    (net (code "396") (name "unconnected-(44-P$10-Pad10)") (class "Default")
      (node (ref "44") (pin "10") (pinfunction "P$10_10") (pintype "no_connect"))
    )
    (net (code "397") (name "unconnected-(44-P$14-Pad14)") (class "Default")
      (node (ref "44") (pin "14") (pinfunction "P$14_14") (pintype "no_connect"))
    )
    (net (code "398") (name "unconnected-(44-P$16-Pad16)") (class "Default")
      (node (ref "44") (pin "16") (pinfunction "P$16_16") (pintype "no_connect"))
    )
    (net (code "399") (name "unconnected-(44-PadINT)") (class "Default")
      (node (ref "44") (pin "INT") (pinfunction "INT_INT") (pintype "bidirectional"))
    )
    (net (code "400") (name "unconnected-(44-PadINT{slash}TRIG)") (class "Default")
      (node (ref "44") (pin "INT/TRIG") (pinfunction "INT/TRIG_INT/TRIG") (pintype "bidirectional"))
    )
    (net (code "401") (name "unconnected-(44-PadMISO)") (class "Default")
      (node (ref "44") (pin "MISO") (pinfunction "MISO_MISO") (pintype "bidirectional"))
    )
    (net (code "402") (name "unconnected-(45-P$4-Pad4)") (class "Default")
      (node (ref "45") (pin "4") (pinfunction "P$4_4") (pintype "no_connect"))
    )
    (net (code "403") (name "unconnected-(45-P$9-Pad9)") (class "Default")
      (node (ref "45") (pin "9") (pinfunction "P$9_9") (pintype "no_connect"))
    )
    (net (code "404") (name "unconnected-(45-P$10-Pad10)") (class "Default")
      (node (ref "45") (pin "10") (pinfunction "P$10_10") (pintype "no_connect"))
    )
    (net (code "405") (name "unconnected-(45-P$14-Pad14)") (class "Default")
      (node (ref "45") (pin "14") (pinfunction "P$14_14") (pintype "no_connect"))
    )
    (net (code "406") (name "unconnected-(45-P$16-Pad16)") (class "Default")
      (node (ref "45") (pin "16") (pinfunction "P$16_16") (pintype "no_connect"))
    )
    (net (code "407") (name "unconnected-(45-PadINT)") (class "Default")
      (node (ref "45") (pin "INT") (pinfunction "INT_INT") (pintype "bidirectional"))
    )
    (net (code "408") (name "unconnected-(45-PadINT{slash}TRIG)") (class "Default")
      (node (ref "45") (pin "INT/TRIG") (pinfunction "INT/TRIG_INT/TRIG") (pintype "bidirectional"))
    )
    (net (code "409") (name "unconnected-(45-PadMISO)") (class "Default")
      (node (ref "45") (pin "MISO") (pinfunction "MISO_MISO") (pintype "bidirectional"))
    )
    (net (code "410") (name "unconnected-(46-P$4-Pad4)") (class "Default")
      (node (ref "46") (pin "4") (pinfunction "P$4_4") (pintype "no_connect"))
    )
    (net (code "411") (name "unconnected-(46-P$9-Pad9)") (class "Default")
      (node (ref "46") (pin "9") (pinfunction "P$9_9") (pintype "no_connect"))
    )
    (net (code "412") (name "unconnected-(46-P$10-Pad10)") (class "Default")
      (node (ref "46") (pin "10") (pinfunction "P$10_10") (pintype "no_connect"))
    )
    (net (code "413") (name "unconnected-(46-P$14-Pad14)") (class "Default")
      (node (ref "46") (pin "14") (pinfunction "P$14_14") (pintype "no_connect"))
    )
    (net (code "414") (name "unconnected-(46-P$16-Pad16)") (class "Default")
      (node (ref "46") (pin "16") (pinfunction "P$16_16") (pintype "no_connect"))
    )
    (net (code "415") (name "unconnected-(46-PadINT)") (class "Default")
      (node (ref "46") (pin "INT") (pinfunction "INT_INT") (pintype "bidirectional"))
    )
    (net (code "416") (name "unconnected-(46-PadINT{slash}TRIG)") (class "Default")
      (node (ref "46") (pin "INT/TRIG") (pinfunction "INT/TRIG_INT/TRIG") (pintype "bidirectional"))
    )
    (net (code "417") (name "unconnected-(46-PadMISO)") (class "Default")
      (node (ref "46") (pin "MISO") (pinfunction "MISO_MISO") (pintype "bidirectional"))
    )
    (net (code "418") (name "unconnected-(47-P$4-Pad4)") (class "Default")
      (node (ref "47") (pin "4") (pinfunction "P$4_4") (pintype "no_connect"))
    )
    (net (code "419") (name "unconnected-(47-P$9-Pad9)") (class "Default")
      (node (ref "47") (pin "9") (pinfunction "P$9_9") (pintype "no_connect"))
    )
    (net (code "420") (name "unconnected-(47-P$10-Pad10)") (class "Default")
      (node (ref "47") (pin "10") (pinfunction "P$10_10") (pintype "no_connect"))
    )
    (net (code "421") (name "unconnected-(47-P$14-Pad14)") (class "Default")
      (node (ref "47") (pin "14") (pinfunction "P$14_14") (pintype "no_connect"))
    )
    (net (code "422") (name "unconnected-(47-P$16-Pad16)") (class "Default")
      (node (ref "47") (pin "16") (pinfunction "P$16_16") (pintype "no_connect"))
    )
    (net (code "423") (name "unconnected-(47-PadINT)") (class "Default")
      (node (ref "47") (pin "INT") (pinfunction "INT_INT") (pintype "bidirectional"))
    )
    (net (code "424") (name "unconnected-(47-PadINT{slash}TRIG)") (class "Default")
      (node (ref "47") (pin "INT/TRIG") (pinfunction "INT/TRIG_INT/TRIG") (pintype "bidirectional"))
    )
    (net (code "425") (name "unconnected-(47-PadMISO)") (class "Default")
      (node (ref "47") (pin "MISO") (pinfunction "MISO_MISO") (pintype "bidirectional"))
    )
    (net (code "426") (name "unconnected-(48-P$4-Pad4)") (class "Default")
      (node (ref "48") (pin "4") (pinfunction "P$4_4") (pintype "no_connect"))
    )
    (net (code "427") (name "unconnected-(48-P$9-Pad9)") (class "Default")
      (node (ref "48") (pin "9") (pinfunction "P$9_9") (pintype "no_connect"))
    )
    (net (code "428") (name "unconnected-(48-P$10-Pad10)") (class "Default")
      (node (ref "48") (pin "10") (pinfunction "P$10_10") (pintype "no_connect"))
    )
    (net (code "429") (name "unconnected-(48-P$14-Pad14)") (class "Default")
      (node (ref "48") (pin "14") (pinfunction "P$14_14") (pintype "no_connect"))
    )
    (net (code "430") (name "unconnected-(48-P$16-Pad16)") (class "Default")
      (node (ref "48") (pin "16") (pinfunction "P$16_16") (pintype "no_connect"))
    )
    (net (code "431") (name "unconnected-(48-PadINT)") (class "Default")
      (node (ref "48") (pin "INT") (pinfunction "INT_INT") (pintype "bidirectional"))
    )
    (net (code "432") (name "unconnected-(48-PadINT{slash}TRIG)") (class "Default")
      (node (ref "48") (pin "INT/TRIG") (pinfunction "INT/TRIG_INT/TRIG") (pintype "bidirectional"))
    )
    (net (code "433") (name "unconnected-(48-PadMISO)") (class "Default")
      (node (ref "48") (pin "MISO") (pinfunction "MISO_MISO") (pintype "bidirectional"))
    )
    (net (code "434") (name "unconnected-(49-P$4-Pad4)") (class "Default")
      (node (ref "49") (pin "4") (pinfunction "P$4_4") (pintype "no_connect"))
    )
    (net (code "435") (name "unconnected-(49-P$9-Pad9)") (class "Default")
      (node (ref "49") (pin "9") (pinfunction "P$9_9") (pintype "no_connect"))
    )
    (net (code "436") (name "unconnected-(49-P$10-Pad10)") (class "Default")
      (node (ref "49") (pin "10") (pinfunction "P$10_10") (pintype "no_connect"))
    )
    (net (code "437") (name "unconnected-(49-P$14-Pad14)") (class "Default")
      (node (ref "49") (pin "14") (pinfunction "P$14_14") (pintype "no_connect"))
    )
    (net (code "438") (name "unconnected-(49-P$16-Pad16)") (class "Default")
      (node (ref "49") (pin "16") (pinfunction "P$16_16") (pintype "no_connect"))
    )
    (net (code "439") (name "unconnected-(49-PadINT)") (class "Default")
      (node (ref "49") (pin "INT") (pinfunction "INT_INT") (pintype "bidirectional"))
    )
    (net (code "440") (name "unconnected-(49-PadINT{slash}TRIG)") (class "Default")
      (node (ref "49") (pin "INT/TRIG") (pinfunction "INT/TRIG_INT/TRIG") (pintype "bidirectional"))
    )
    (net (code "441") (name "unconnected-(49-PadMISO)") (class "Default")
      (node (ref "49") (pin "MISO") (pinfunction "MISO_MISO") (pintype "bidirectional"))
    )
    (net (code "442") (name "unconnected-(50-P$4-Pad4)") (class "Default")
      (node (ref "50") (pin "4") (pinfunction "P$4_4") (pintype "no_connect"))
    )
    (net (code "443") (name "unconnected-(50-P$9-Pad9)") (class "Default")
      (node (ref "50") (pin "9") (pinfunction "P$9_9") (pintype "no_connect"))
    )
    (net (code "444") (name "unconnected-(50-P$10-Pad10)") (class "Default")
      (node (ref "50") (pin "10") (pinfunction "P$10_10") (pintype "no_connect"))
    )
    (net (code "445") (name "unconnected-(50-P$14-Pad14)") (class "Default")
      (node (ref "50") (pin "14") (pinfunction "P$14_14") (pintype "no_connect"))
    )
    (net (code "446") (name "unconnected-(50-P$16-Pad16)") (class "Default")
      (node (ref "50") (pin "16") (pinfunction "P$16_16") (pintype "no_connect"))
    )
    (net (code "447") (name "unconnected-(50-PadINT)") (class "Default")
      (node (ref "50") (pin "INT") (pinfunction "INT_INT") (pintype "bidirectional"))
    )
    (net (code "448") (name "unconnected-(50-PadINT{slash}TRIG)") (class "Default")
      (node (ref "50") (pin "INT/TRIG") (pinfunction "INT/TRIG_INT/TRIG") (pintype "bidirectional"))
    )
    (net (code "449") (name "unconnected-(50-PadMISO)") (class "Default")
      (node (ref "50") (pin "MISO") (pinfunction "MISO_MISO") (pintype "bidirectional"))
    )
    (net (code "450") (name "unconnected-(51-P$4-Pad4)") (class "Default")
      (node (ref "51") (pin "4") (pinfunction "P$4_4") (pintype "no_connect"))
    )
    (net (code "451") (name "unconnected-(51-P$9-Pad9)") (class "Default")
      (node (ref "51") (pin "9") (pinfunction "P$9_9") (pintype "no_connect"))
    )
    (net (code "452") (name "unconnected-(51-P$10-Pad10)") (class "Default")
      (node (ref "51") (pin "10") (pinfunction "P$10_10") (pintype "no_connect"))
    )
    (net (code "453") (name "unconnected-(51-P$14-Pad14)") (class "Default")
      (node (ref "51") (pin "14") (pinfunction "P$14_14") (pintype "no_connect"))
    )
    (net (code "454") (name "unconnected-(51-P$16-Pad16)") (class "Default")
      (node (ref "51") (pin "16") (pinfunction "P$16_16") (pintype "no_connect"))
    )
    (net (code "455") (name "unconnected-(51-PadINT)") (class "Default")
      (node (ref "51") (pin "INT") (pinfunction "INT_INT") (pintype "bidirectional"))
    )
    (net (code "456") (name "unconnected-(51-PadINT{slash}TRIG)") (class "Default")
      (node (ref "51") (pin "INT/TRIG") (pinfunction "INT/TRIG_INT/TRIG") (pintype "bidirectional"))
    )
    (net (code "457") (name "unconnected-(51-PadMISO)") (class "Default")
      (node (ref "51") (pin "MISO") (pinfunction "MISO_MISO") (pintype "bidirectional"))
    )
    (net (code "458") (name "unconnected-(52-P$4-Pad4)") (class "Default")
      (node (ref "52") (pin "4") (pinfunction "P$4_4") (pintype "no_connect"))
    )
    (net (code "459") (name "unconnected-(52-P$9-Pad9)") (class "Default")
      (node (ref "52") (pin "9") (pinfunction "P$9_9") (pintype "no_connect"))
    )
    (net (code "460") (name "unconnected-(52-P$10-Pad10)") (class "Default")
      (node (ref "52") (pin "10") (pinfunction "P$10_10") (pintype "no_connect"))
    )
    (net (code "461") (name "unconnected-(52-P$14-Pad14)") (class "Default")
      (node (ref "52") (pin "14") (pinfunction "P$14_14") (pintype "no_connect"))
    )
    (net (code "462") (name "unconnected-(52-P$16-Pad16)") (class "Default")
      (node (ref "52") (pin "16") (pinfunction "P$16_16") (pintype "no_connect"))
    )
    (net (code "463") (name "unconnected-(52-PadINT)") (class "Default")
      (node (ref "52") (pin "INT") (pinfunction "INT_INT") (pintype "bidirectional"))
    )
    (net (code "464") (name "unconnected-(52-PadINT{slash}TRIG)") (class "Default")
      (node (ref "52") (pin "INT/TRIG") (pinfunction "INT/TRIG_INT/TRIG") (pintype "bidirectional"))
    )
    (net (code "465") (name "unconnected-(52-PadMISO)") (class "Default")
      (node (ref "52") (pin "MISO") (pinfunction "MISO_MISO") (pintype "bidirectional"))
    )
    (net (code "466") (name "unconnected-(53-P$4-Pad4)") (class "Default")
      (node (ref "53") (pin "4") (pinfunction "P$4_4") (pintype "no_connect"))
    )
    (net (code "467") (name "unconnected-(53-P$9-Pad9)") (class "Default")
      (node (ref "53") (pin "9") (pinfunction "P$9_9") (pintype "no_connect"))
    )
    (net (code "468") (name "unconnected-(53-P$10-Pad10)") (class "Default")
      (node (ref "53") (pin "10") (pinfunction "P$10_10") (pintype "no_connect"))
    )
    (net (code "469") (name "unconnected-(53-P$14-Pad14)") (class "Default")
      (node (ref "53") (pin "14") (pinfunction "P$14_14") (pintype "no_connect"))
    )
    (net (code "470") (name "unconnected-(53-P$16-Pad16)") (class "Default")
      (node (ref "53") (pin "16") (pinfunction "P$16_16") (pintype "no_connect"))
    )
    (net (code "471") (name "unconnected-(53-PadINT)") (class "Default")
      (node (ref "53") (pin "INT") (pinfunction "INT_INT") (pintype "bidirectional"))
    )
    (net (code "472") (name "unconnected-(53-PadINT{slash}TRIG)") (class "Default")
      (node (ref "53") (pin "INT/TRIG") (pinfunction "INT/TRIG_INT/TRIG") (pintype "bidirectional"))
    )
    (net (code "473") (name "unconnected-(53-PadMISO)") (class "Default")
      (node (ref "53") (pin "MISO") (pinfunction "MISO_MISO") (pintype "bidirectional"))
    )
    (net (code "474") (name "unconnected-(54-P$4-Pad4)") (class "Default")
      (node (ref "54") (pin "4") (pinfunction "P$4_4") (pintype "no_connect"))
    )
    (net (code "475") (name "unconnected-(54-P$9-Pad9)") (class "Default")
      (node (ref "54") (pin "9") (pinfunction "P$9_9") (pintype "no_connect"))
    )
    (net (code "476") (name "unconnected-(54-P$10-Pad10)") (class "Default")
      (node (ref "54") (pin "10") (pinfunction "P$10_10") (pintype "no_connect"))
    )
    (net (code "477") (name "unconnected-(54-P$14-Pad14)") (class "Default")
      (node (ref "54") (pin "14") (pinfunction "P$14_14") (pintype "no_connect"))
    )
    (net (code "478") (name "unconnected-(54-P$16-Pad16)") (class "Default")
      (node (ref "54") (pin "16") (pinfunction "P$16_16") (pintype "no_connect"))
    )
    (net (code "479") (name "unconnected-(54-PadINT)") (class "Default")
      (node (ref "54") (pin "INT") (pinfunction "INT_INT") (pintype "bidirectional"))
    )
    (net (code "480") (name "unconnected-(54-PadINT{slash}TRIG)") (class "Default")
      (node (ref "54") (pin "INT/TRIG") (pinfunction "INT/TRIG_INT/TRIG") (pintype "bidirectional"))
    )
    (net (code "481") (name "unconnected-(54-PadMISO)") (class "Default")
      (node (ref "54") (pin "MISO") (pinfunction "MISO_MISO") (pintype "bidirectional"))
    )
    (net (code "482") (name "unconnected-(55-P$4-Pad4)") (class "Default")
      (node (ref "55") (pin "4") (pinfunction "P$4_4") (pintype "no_connect"))
    )
    (net (code "483") (name "unconnected-(55-P$9-Pad9)") (class "Default")
      (node (ref "55") (pin "9") (pinfunction "P$9_9") (pintype "no_connect"))
    )
    (net (code "484") (name "unconnected-(55-P$10-Pad10)") (class "Default")
      (node (ref "55") (pin "10") (pinfunction "P$10_10") (pintype "no_connect"))
    )
    (net (code "485") (name "unconnected-(55-P$14-Pad14)") (class "Default")
      (node (ref "55") (pin "14") (pinfunction "P$14_14") (pintype "no_connect"))
    )
    (net (code "486") (name "unconnected-(55-P$16-Pad16)") (class "Default")
      (node (ref "55") (pin "16") (pinfunction "P$16_16") (pintype "no_connect"))
    )
    (net (code "487") (name "unconnected-(55-PadINT)") (class "Default")
      (node (ref "55") (pin "INT") (pinfunction "INT_INT") (pintype "bidirectional"))
    )
    (net (code "488") (name "unconnected-(55-PadINT{slash}TRIG)") (class "Default")
      (node (ref "55") (pin "INT/TRIG") (pinfunction "INT/TRIG_INT/TRIG") (pintype "bidirectional"))
    )
    (net (code "489") (name "unconnected-(55-PadMISO)") (class "Default")
      (node (ref "55") (pin "MISO") (pinfunction "MISO_MISO") (pintype "bidirectional"))
    )
    (net (code "490") (name "unconnected-(56-P$4-Pad4)") (class "Default")
      (node (ref "56") (pin "4") (pinfunction "P$4_4") (pintype "no_connect"))
    )
    (net (code "491") (name "unconnected-(56-P$9-Pad9)") (class "Default")
      (node (ref "56") (pin "9") (pinfunction "P$9_9") (pintype "no_connect"))
    )
    (net (code "492") (name "unconnected-(56-P$10-Pad10)") (class "Default")
      (node (ref "56") (pin "10") (pinfunction "P$10_10") (pintype "no_connect"))
    )
    (net (code "493") (name "unconnected-(56-P$14-Pad14)") (class "Default")
      (node (ref "56") (pin "14") (pinfunction "P$14_14") (pintype "no_connect"))
    )
    (net (code "494") (name "unconnected-(56-P$16-Pad16)") (class "Default")
      (node (ref "56") (pin "16") (pinfunction "P$16_16") (pintype "no_connect"))
    )
    (net (code "495") (name "unconnected-(56-PadINT)") (class "Default")
      (node (ref "56") (pin "INT") (pinfunction "INT_INT") (pintype "bidirectional"))
    )
    (net (code "496") (name "unconnected-(56-PadINT{slash}TRIG)") (class "Default")
      (node (ref "56") (pin "INT/TRIG") (pinfunction "INT/TRIG_INT/TRIG") (pintype "bidirectional"))
    )
    (net (code "497") (name "unconnected-(56-PadMISO)") (class "Default")
      (node (ref "56") (pin "MISO") (pinfunction "MISO_MISO") (pintype "bidirectional"))
    )
    (net (code "498") (name "unconnected-(57-P$4-Pad4)") (class "Default")
      (node (ref "57") (pin "4") (pinfunction "P$4_4") (pintype "no_connect"))
    )
    (net (code "499") (name "unconnected-(57-P$9-Pad9)") (class "Default")
      (node (ref "57") (pin "9") (pinfunction "P$9_9") (pintype "no_connect"))
    )
    (net (code "500") (name "unconnected-(57-P$10-Pad10)") (class "Default")
      (node (ref "57") (pin "10") (pinfunction "P$10_10") (pintype "no_connect"))
    )
    (net (code "501") (name "unconnected-(57-P$14-Pad14)") (class "Default")
      (node (ref "57") (pin "14") (pinfunction "P$14_14") (pintype "no_connect"))
    )
    (net (code "502") (name "unconnected-(57-P$16-Pad16)") (class "Default")
      (node (ref "57") (pin "16") (pinfunction "P$16_16") (pintype "no_connect"))
    )
    (net (code "503") (name "unconnected-(57-PadINT)") (class "Default")
      (node (ref "57") (pin "INT") (pinfunction "INT_INT") (pintype "bidirectional"))
    )
    (net (code "504") (name "unconnected-(57-PadINT{slash}TRIG)") (class "Default")
      (node (ref "57") (pin "INT/TRIG") (pinfunction "INT/TRIG_INT/TRIG") (pintype "bidirectional"))
    )
    (net (code "505") (name "unconnected-(57-PadMISO)") (class "Default")
      (node (ref "57") (pin "MISO") (pinfunction "MISO_MISO") (pintype "bidirectional"))
    )
    (net (code "506") (name "unconnected-(58-P$4-Pad4)") (class "Default")
      (node (ref "58") (pin "4") (pinfunction "P$4_4") (pintype "no_connect"))
    )
    (net (code "507") (name "unconnected-(58-P$9-Pad9)") (class "Default")
      (node (ref "58") (pin "9") (pinfunction "P$9_9") (pintype "no_connect"))
    )
    (net (code "508") (name "unconnected-(58-P$10-Pad10)") (class "Default")
      (node (ref "58") (pin "10") (pinfunction "P$10_10") (pintype "no_connect"))
    )
    (net (code "509") (name "unconnected-(58-P$14-Pad14)") (class "Default")
      (node (ref "58") (pin "14") (pinfunction "P$14_14") (pintype "no_connect"))
    )
    (net (code "510") (name "unconnected-(58-P$16-Pad16)") (class "Default")
      (node (ref "58") (pin "16") (pinfunction "P$16_16") (pintype "no_connect"))
    )
    (net (code "511") (name "unconnected-(58-PadINT)") (class "Default")
      (node (ref "58") (pin "INT") (pinfunction "INT_INT") (pintype "bidirectional"))
    )
    (net (code "512") (name "unconnected-(58-PadINT{slash}TRIG)") (class "Default")
      (node (ref "58") (pin "INT/TRIG") (pinfunction "INT/TRIG_INT/TRIG") (pintype "bidirectional"))
    )
    (net (code "513") (name "unconnected-(58-PadMISO)") (class "Default")
      (node (ref "58") (pin "MISO") (pinfunction "MISO_MISO") (pintype "bidirectional"))
    )
    (net (code "514") (name "unconnected-(59-P$4-Pad4)") (class "Default")
      (node (ref "59") (pin "4") (pinfunction "P$4_4") (pintype "no_connect"))
    )
    (net (code "515") (name "unconnected-(59-P$9-Pad9)") (class "Default")
      (node (ref "59") (pin "9") (pinfunction "P$9_9") (pintype "no_connect"))
    )
    (net (code "516") (name "unconnected-(59-P$10-Pad10)") (class "Default")
      (node (ref "59") (pin "10") (pinfunction "P$10_10") (pintype "no_connect"))
    )
    (net (code "517") (name "unconnected-(59-P$14-Pad14)") (class "Default")
      (node (ref "59") (pin "14") (pinfunction "P$14_14") (pintype "no_connect"))
    )
    (net (code "518") (name "unconnected-(59-P$16-Pad16)") (class "Default")
      (node (ref "59") (pin "16") (pinfunction "P$16_16") (pintype "no_connect"))
    )
    (net (code "519") (name "unconnected-(59-PadINT)") (class "Default")
      (node (ref "59") (pin "INT") (pinfunction "INT_INT") (pintype "bidirectional"))
    )
    (net (code "520") (name "unconnected-(59-PadINT{slash}TRIG)") (class "Default")
      (node (ref "59") (pin "INT/TRIG") (pinfunction "INT/TRIG_INT/TRIG") (pintype "bidirectional"))
    )
    (net (code "521") (name "unconnected-(59-PadMISO)") (class "Default")
      (node (ref "59") (pin "MISO") (pinfunction "MISO_MISO") (pintype "bidirectional"))
    )
    (net (code "522") (name "unconnected-(60-P$4-Pad4)") (class "Default")
      (node (ref "60") (pin "4") (pinfunction "P$4_4") (pintype "no_connect"))
    )
    (net (code "523") (name "unconnected-(60-P$9-Pad9)") (class "Default")
      (node (ref "60") (pin "9") (pinfunction "P$9_9") (pintype "no_connect"))
    )
    (net (code "524") (name "unconnected-(60-P$10-Pad10)") (class "Default")
      (node (ref "60") (pin "10") (pinfunction "P$10_10") (pintype "no_connect"))
    )
    (net (code "525") (name "unconnected-(60-P$14-Pad14)") (class "Default")
      (node (ref "60") (pin "14") (pinfunction "P$14_14") (pintype "no_connect"))
    )
    (net (code "526") (name "unconnected-(60-P$16-Pad16)") (class "Default")
      (node (ref "60") (pin "16") (pinfunction "P$16_16") (pintype "no_connect"))
    )
    (net (code "527") (name "unconnected-(60-PadINT)") (class "Default")
      (node (ref "60") (pin "INT") (pinfunction "INT_INT") (pintype "bidirectional"))
    )
    (net (code "528") (name "unconnected-(60-PadINT{slash}TRIG)") (class "Default")
      (node (ref "60") (pin "INT/TRIG") (pinfunction "INT/TRIG_INT/TRIG") (pintype "bidirectional"))
    )
    (net (code "529") (name "unconnected-(60-PadMISO)") (class "Default")
      (node (ref "60") (pin "MISO") (pinfunction "MISO_MISO") (pintype "bidirectional"))
    )
    (net (code "530") (name "unconnected-(61-P$4-Pad4)") (class "Default")
      (node (ref "61") (pin "4") (pinfunction "P$4_4") (pintype "no_connect"))
    )
    (net (code "531") (name "unconnected-(61-P$9-Pad9)") (class "Default")
      (node (ref "61") (pin "9") (pinfunction "P$9_9") (pintype "no_connect"))
    )
    (net (code "532") (name "unconnected-(61-P$10-Pad10)") (class "Default")
      (node (ref "61") (pin "10") (pinfunction "P$10_10") (pintype "no_connect"))
    )
    (net (code "533") (name "unconnected-(61-P$14-Pad14)") (class "Default")
      (node (ref "61") (pin "14") (pinfunction "P$14_14") (pintype "no_connect"))
    )
    (net (code "534") (name "unconnected-(61-P$16-Pad16)") (class "Default")
      (node (ref "61") (pin "16") (pinfunction "P$16_16") (pintype "no_connect"))
    )
    (net (code "535") (name "unconnected-(61-PadINT)") (class "Default")
      (node (ref "61") (pin "INT") (pinfunction "INT_INT") (pintype "bidirectional"))
    )
    (net (code "536") (name "unconnected-(61-PadINT{slash}TRIG)") (class "Default")
      (node (ref "61") (pin "INT/TRIG") (pinfunction "INT/TRIG_INT/TRIG") (pintype "bidirectional"))
    )
    (net (code "537") (name "unconnected-(61-PadMISO)") (class "Default")
      (node (ref "61") (pin "MISO") (pinfunction "MISO_MISO") (pintype "bidirectional"))
    )
    (net (code "538") (name "unconnected-(62-P$4-Pad4)") (class "Default")
      (node (ref "62") (pin "4") (pinfunction "P$4_4") (pintype "no_connect"))
    )
    (net (code "539") (name "unconnected-(62-P$9-Pad9)") (class "Default")
      (node (ref "62") (pin "9") (pinfunction "P$9_9") (pintype "no_connect"))
    )
    (net (code "540") (name "unconnected-(62-P$10-Pad10)") (class "Default")
      (node (ref "62") (pin "10") (pinfunction "P$10_10") (pintype "no_connect"))
    )
    (net (code "541") (name "unconnected-(62-P$14-Pad14)") (class "Default")
      (node (ref "62") (pin "14") (pinfunction "P$14_14") (pintype "no_connect"))
    )
    (net (code "542") (name "unconnected-(62-P$16-Pad16)") (class "Default")
      (node (ref "62") (pin "16") (pinfunction "P$16_16") (pintype "no_connect"))
    )
    (net (code "543") (name "unconnected-(62-PadINT)") (class "Default")
      (node (ref "62") (pin "INT") (pinfunction "INT_INT") (pintype "bidirectional"))
    )
    (net (code "544") (name "unconnected-(62-PadINT{slash}TRIG)") (class "Default")
      (node (ref "62") (pin "INT/TRIG") (pinfunction "INT/TRIG_INT/TRIG") (pintype "bidirectional"))
    )
    (net (code "545") (name "unconnected-(62-PadMISO)") (class "Default")
      (node (ref "62") (pin "MISO") (pinfunction "MISO_MISO") (pintype "bidirectional"))
    )
    (net (code "546") (name "unconnected-(63-P$4-Pad4)") (class "Default")
      (node (ref "63") (pin "4") (pinfunction "P$4_4") (pintype "no_connect"))
    )
    (net (code "547") (name "unconnected-(63-P$9-Pad9)") (class "Default")
      (node (ref "63") (pin "9") (pinfunction "P$9_9") (pintype "no_connect"))
    )
    (net (code "548") (name "unconnected-(63-P$10-Pad10)") (class "Default")
      (node (ref "63") (pin "10") (pinfunction "P$10_10") (pintype "no_connect"))
    )
    (net (code "549") (name "unconnected-(63-P$14-Pad14)") (class "Default")
      (node (ref "63") (pin "14") (pinfunction "P$14_14") (pintype "no_connect"))
    )
    (net (code "550") (name "unconnected-(63-P$16-Pad16)") (class "Default")
      (node (ref "63") (pin "16") (pinfunction "P$16_16") (pintype "no_connect"))
    )
    (net (code "551") (name "unconnected-(63-PadINT)") (class "Default")
      (node (ref "63") (pin "INT") (pinfunction "INT_INT") (pintype "bidirectional"))
    )
    (net (code "552") (name "unconnected-(63-PadINT{slash}TRIG)") (class "Default")
      (node (ref "63") (pin "INT/TRIG") (pinfunction "INT/TRIG_INT/TRIG") (pintype "bidirectional"))
    )
    (net (code "553") (name "unconnected-(63-PadMISO)") (class "Default")
      (node (ref "63") (pin "MISO") (pinfunction "MISO_MISO") (pintype "bidirectional"))
    )
    (net (code "554") (name "unconnected-(64-P$4-Pad4)") (class "Default")
      (node (ref "64") (pin "4") (pinfunction "P$4_4") (pintype "no_connect"))
    )
    (net (code "555") (name "unconnected-(64-P$9-Pad9)") (class "Default")
      (node (ref "64") (pin "9") (pinfunction "P$9_9") (pintype "no_connect"))
    )
    (net (code "556") (name "unconnected-(64-P$10-Pad10)") (class "Default")
      (node (ref "64") (pin "10") (pinfunction "P$10_10") (pintype "no_connect"))
    )
    (net (code "557") (name "unconnected-(64-P$14-Pad14)") (class "Default")
      (node (ref "64") (pin "14") (pinfunction "P$14_14") (pintype "no_connect"))
    )
    (net (code "558") (name "unconnected-(64-P$16-Pad16)") (class "Default")
      (node (ref "64") (pin "16") (pinfunction "P$16_16") (pintype "no_connect"))
    )
    (net (code "559") (name "unconnected-(64-PadINT)") (class "Default")
      (node (ref "64") (pin "INT") (pinfunction "INT_INT") (pintype "bidirectional"))
    )
    (net (code "560") (name "unconnected-(64-PadINT{slash}TRIG)") (class "Default")
      (node (ref "64") (pin "INT/TRIG") (pinfunction "INT/TRIG_INT/TRIG") (pintype "bidirectional"))
    )
    (net (code "561") (name "unconnected-(64-PadMISO)") (class "Default")
      (node (ref "64") (pin "MISO") (pinfunction "MISO_MISO") (pintype "bidirectional"))
    )
    (net (code "562") (name "unconnected-(SV1-Pad4)") (class "Default")
      (node (ref "SV1") (pin "4") (pinfunction "4_4") (pintype "passive"))
    )
    (net (code "563") (name "unconnected-(SV1-Pad11)") (class "Default")
      (node (ref "SV1") (pin "11") (pinfunction "11_11") (pintype "passive"))
    )
    (net (code "564") (name "unconnected-(SV2-Pad2)") (class "Default")
      (node (ref "SV2") (pin "2") (pinfunction "2_2") (pintype "passive"))
    )
    (net (code "565") (name "unconnected-(SV2-Pad3)") (class "Default")
      (node (ref "SV2") (pin "3") (pinfunction "3_3") (pintype "passive"))
    )
    (net (code "566") (name "unconnected-(SV2-Pad4)") (class "Default")
      (node (ref "SV2") (pin "4") (pinfunction "4_4") (pintype "passive"))
    )
    (net (code "567") (name "unconnected-(SV2-Pad5)") (class "Default")
      (node (ref "SV2") (pin "5") (pinfunction "5_5") (pintype "passive"))
    )
    (net (code "568") (name "unconnected-(SV2-Pad6)") (class "Default")
      (node (ref "SV2") (pin "6") (pinfunction "6_6") (pintype "passive"))
    )
    (net (code "569") (name "unconnected-(SV2-Pad7)") (class "Default")
      (node (ref "SV2") (pin "7") (pinfunction "7_7") (pintype "passive"))
    )
    (net (code "570") (name "unconnected-(SV2-Pad8)") (class "Default")
      (node (ref "SV2") (pin "8") (pinfunction "8_8") (pintype "passive"))
    )
    (net (code "571") (name "unconnected-(SV2-Pad9)") (class "Default")
      (node (ref "SV2") (pin "9") (pinfunction "9_9") (pintype "passive"))
    )
    (net (code "572") (name "unconnected-(SV2-Pad10)") (class "Default")
      (node (ref "SV2") (pin "10") (pinfunction "10_10") (pintype "passive"))
    )
    (net (code "573") (name "unconnected-(SV3-Pad1)") (class "Default")
      (node (ref "SV3") (pin "1") (pinfunction "1_1") (pintype "passive"))
    )
    (net (code "574") (name "unconnected-(SV3-Pad2)") (class "Default")
      (node (ref "SV3") (pin "2") (pinfunction "2_2") (pintype "passive"))
    )
    (net (code "575") (name "unconnected-(SV3-Pad3)") (class "Default")
      (node (ref "SV3") (pin "3") (pinfunction "3_3") (pintype "passive"))
    )
    (net (code "576") (name "unconnected-(SV3-Pad4)") (class "Default")
      (node (ref "SV3") (pin "4") (pinfunction "4_4") (pintype "passive"))
    )
    (net (code "577") (name "unconnected-(SV3-Pad7)") (class "Default")
      (node (ref "SV3") (pin "7") (pinfunction "7_7") (pintype "passive"))
    )
    (net (code "578") (name "unconnected-(SV3-Pad8)") (class "Default")
      (node (ref "SV3") (pin "8") (pinfunction "8_8") (pintype "passive"))
    )
    (net (code "579") (name "unconnected-(SV3-Pad9)") (class "Default")
      (node (ref "SV3") (pin "9") (pinfunction "9_9") (pintype "passive"))
    )
    (net (code "580") (name "unconnected-(SV3-Pad11)") (class "Default")
      (node (ref "SV3") (pin "11") (pinfunction "11_11") (pintype "passive"))
    )
    (net (code "581") (name "unconnected-(SV3-Pad12)") (class "Default")
      (node (ref "SV3") (pin "12") (pinfunction "12_12") (pintype "passive"))
    )
    (net (code "582") (name "unconnected-(SV3-Pad13)") (class "Default")
      (node (ref "SV3") (pin "13") (pinfunction "13_13") (pintype "passive"))
    )
    (net (code "583") (name "unconnected-(SV4-Pad1)") (class "Default")
      (node (ref "SV4") (pin "1") (pinfunction "1_1") (pintype "passive"))
    )
    (net (code "584") (name "unconnected-(SV4-Pad4)") (class "Default")
      (node (ref "SV4") (pin "4") (pinfunction "4_4") (pintype "passive"))
    )
    (net (code "585") (name "unconnected-(SV4-Pad5)") (class "Default")
      (node (ref "SV4") (pin "5") (pinfunction "5_5") (pintype "passive"))
    )
    (net (code "586") (name "unconnected-(SV4-Pad6)") (class "Default")
      (node (ref "SV4") (pin "6") (pinfunction "6_6") (pintype "passive"))
    )
    (net (code "587") (name "unconnected-(SV4-Pad7)") (class "Default")
      (node (ref "SV4") (pin "7") (pinfunction "7_7") (pintype "passive"))
    )
    (net (code "588") (name "unconnected-(SV4-Pad8)") (class "Default")
      (node (ref "SV4") (pin "8") (pinfunction "8_8") (pintype "passive"))
    )
    (net (code "589") (name "unconnected-(SV5-Pad2)") (class "Default")
      (node (ref "SV5") (pin "2") (pinfunction "2_2") (pintype "passive"))
    )
    (net (code "590") (name "unconnected-(SV5-Pad4)") (class "Default")
      (node (ref "SV5") (pin "4") (pinfunction "4_4") (pintype "passive"))
    )
    (net (code "591") (name "unconnected-(SV5-Pad5)") (class "Default")
      (node (ref "SV5") (pin "5") (pinfunction "5_5") (pintype "passive"))
    )
    (net (code "592") (name "unconnected-(SV5-Pad6)") (class "Default")
      (node (ref "SV5") (pin "6") (pinfunction "6_6") (pintype "passive"))
    )
    (net (code "593") (name "unconnected-(SV5-Pad7)") (class "Default")
      (node (ref "SV5") (pin "7") (pinfunction "7_7") (pintype "passive"))
    )
    (net (code "594") (name "unconnected-(SV5-Pad8)") (class "Default")
      (node (ref "SV5") (pin "8") (pinfunction "8_8") (pintype "passive"))
    )
    (net (code "595") (name "unconnected-(SV5-Pad9)") (class "Default")
      (node (ref "SV5") (pin "9") (pinfunction "9_9") (pintype "passive"))
    )
    (net (code "596") (name "unconnected-(SV5-Pad10)") (class "Default")
      (node (ref "SV5") (pin "10") (pinfunction "10_10") (pintype "passive"))
    )
    (net (code "597") (name "unconnected-(SV6-Pad1)") (class "Default")
      (node (ref "SV6") (pin "1") (pinfunction "1_1") (pintype "passive"))
    )
    (net (code "598") (name "unconnected-(SV6-Pad6)") (class "Default")
      (node (ref "SV6") (pin "6") (pinfunction "6_6") (pintype "passive"))
    )
    (net (code "599") (name "~{OE0}") (class "Default")
      (node (ref "MUX_I2C0") (pin "!1OE") (pinfunction "~{1OE}_!1OE") (pintype "bidirectional"))
      (node (ref "MUX_I2C0") (pin "!2OE") (pinfunction "~{20E}_!2OE") (pintype "bidirectional"))
      (node (ref "SV1") (pin "7") (pinfunction "7_7") (pintype "passive"))
    )
    (net (code "600") (name "~{OE1}") (class "Default")
      (node (ref "MUX_I2C1") (pin "!1OE") (pinfunction "~{1OE}_!1OE") (pintype "bidirectional"))
      (node (ref "MUX_I2C1") (pin "!2OE") (pinfunction "~{20E}_!2OE") (pintype "bidirectional"))
      (node (ref "SV1") (pin "8") (pinfunction "8_8") (pintype "passive"))
    )
    (net (code "601") (name "~{OE2}") (class "Default")
      (node (ref "MUX_I2C2") (pin "!1OE") (pinfunction "~{1OE}_!1OE") (pintype "bidirectional"))
      (node (ref "MUX_I2C2") (pin "!2OE") (pinfunction "~{20E}_!2OE") (pintype "bidirectional"))
      (node (ref "SV1") (pin "9") (pinfunction "9_9") (pintype "passive"))
    )
    (net (code "602") (name "~{OE3}") (class "Default")
      (node (ref "MUX_I2C3") (pin "!1OE") (pinfunction "~{1OE}_!1OE") (pintype "bidirectional"))
      (node (ref "MUX_I2C3") (pin "!2OE") (pinfunction "~{20E}_!2OE") (pintype "bidirectional"))
      (node (ref "SV1") (pin "10") (pinfunction "10_10") (pintype "passive"))
    )
  )
)
